# ARE_adaptadores_v101.net
KiCad netlist of a schematic drawn in EAGLE
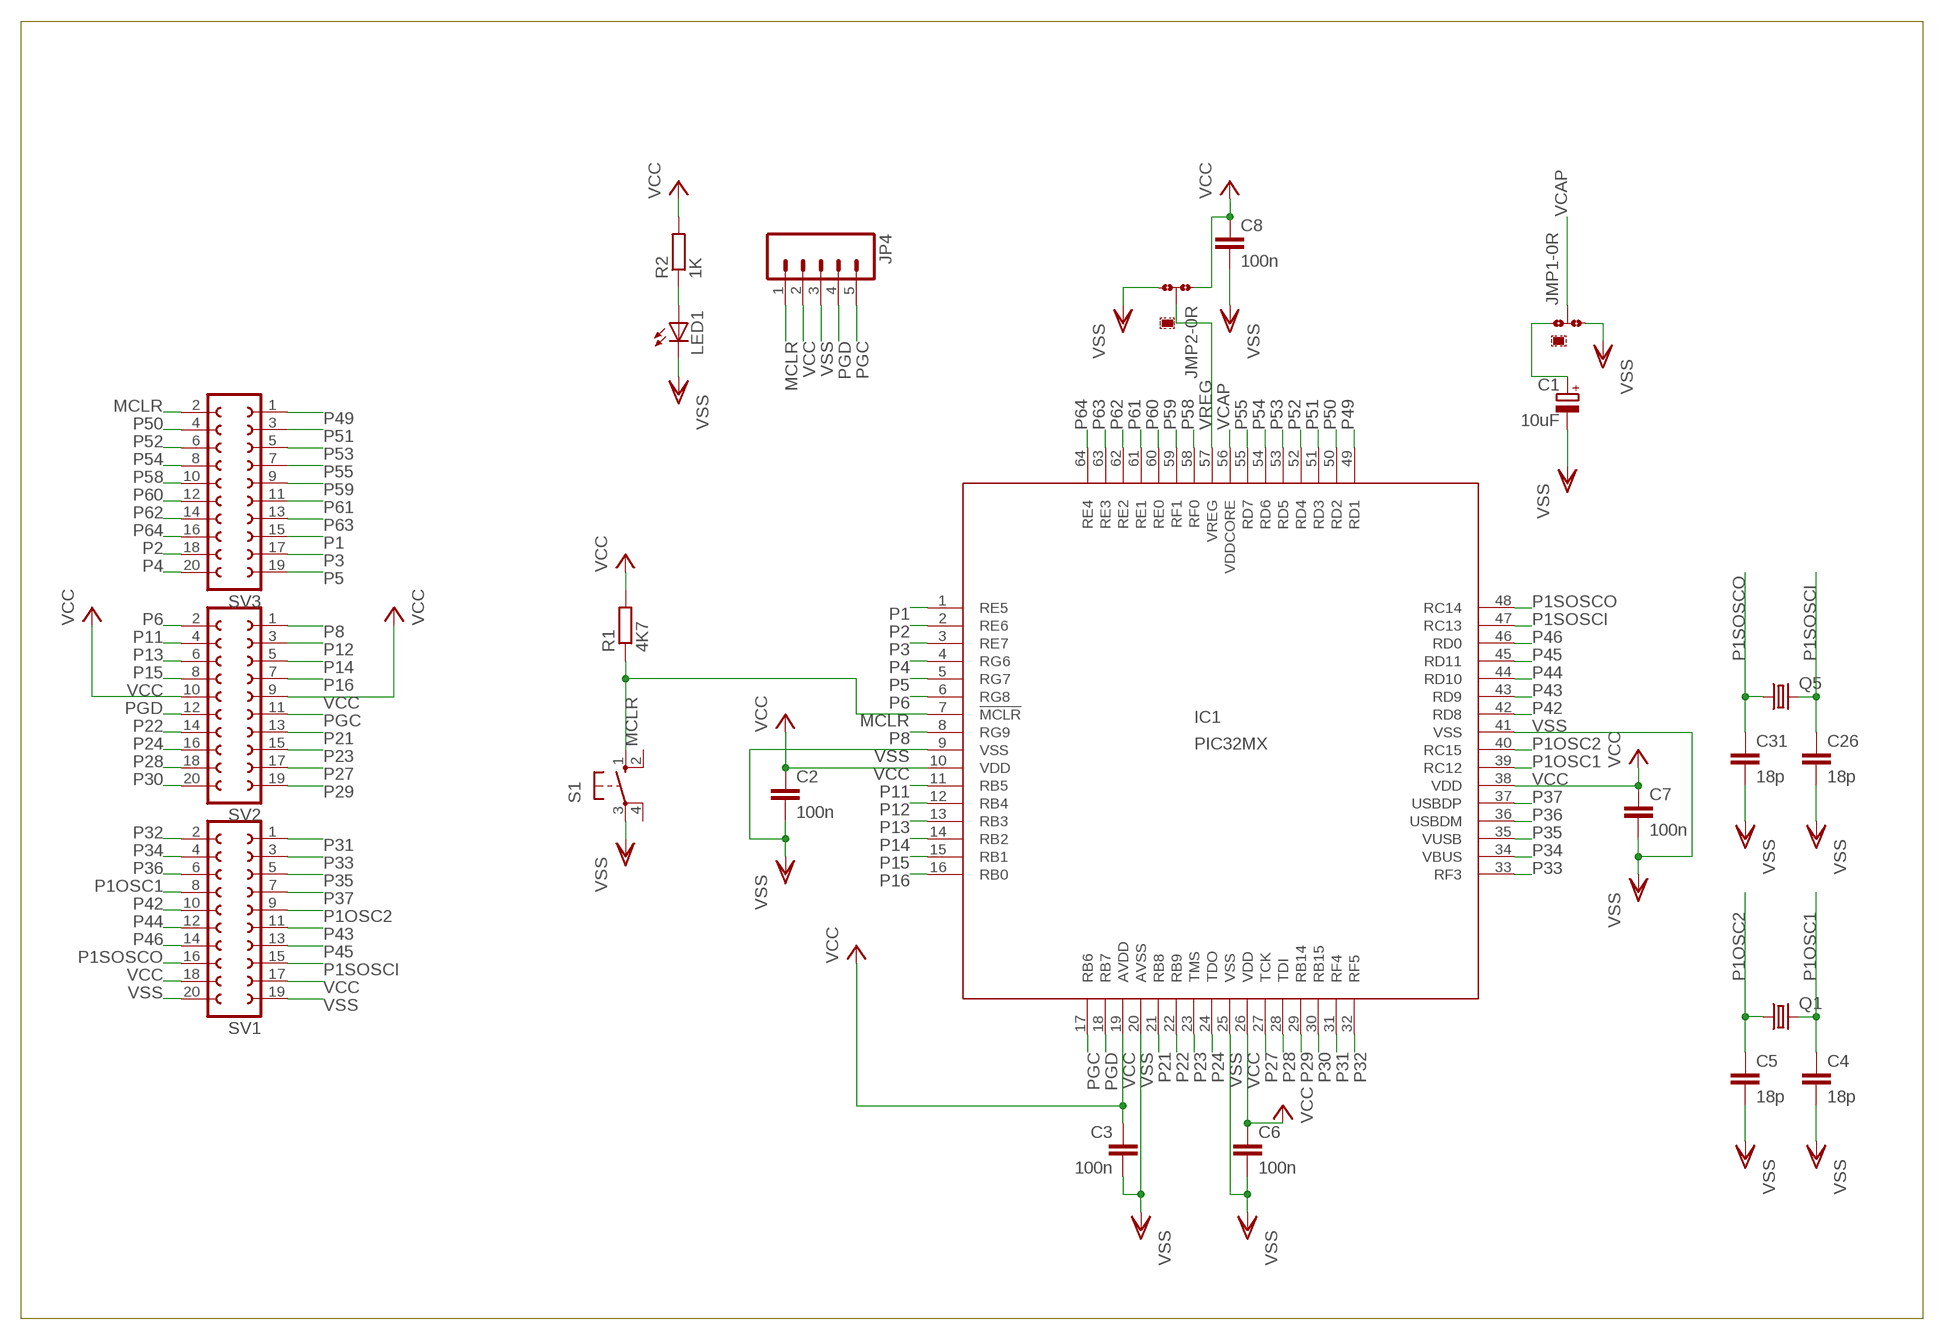
[diagram p0: schematic, sheet 1]
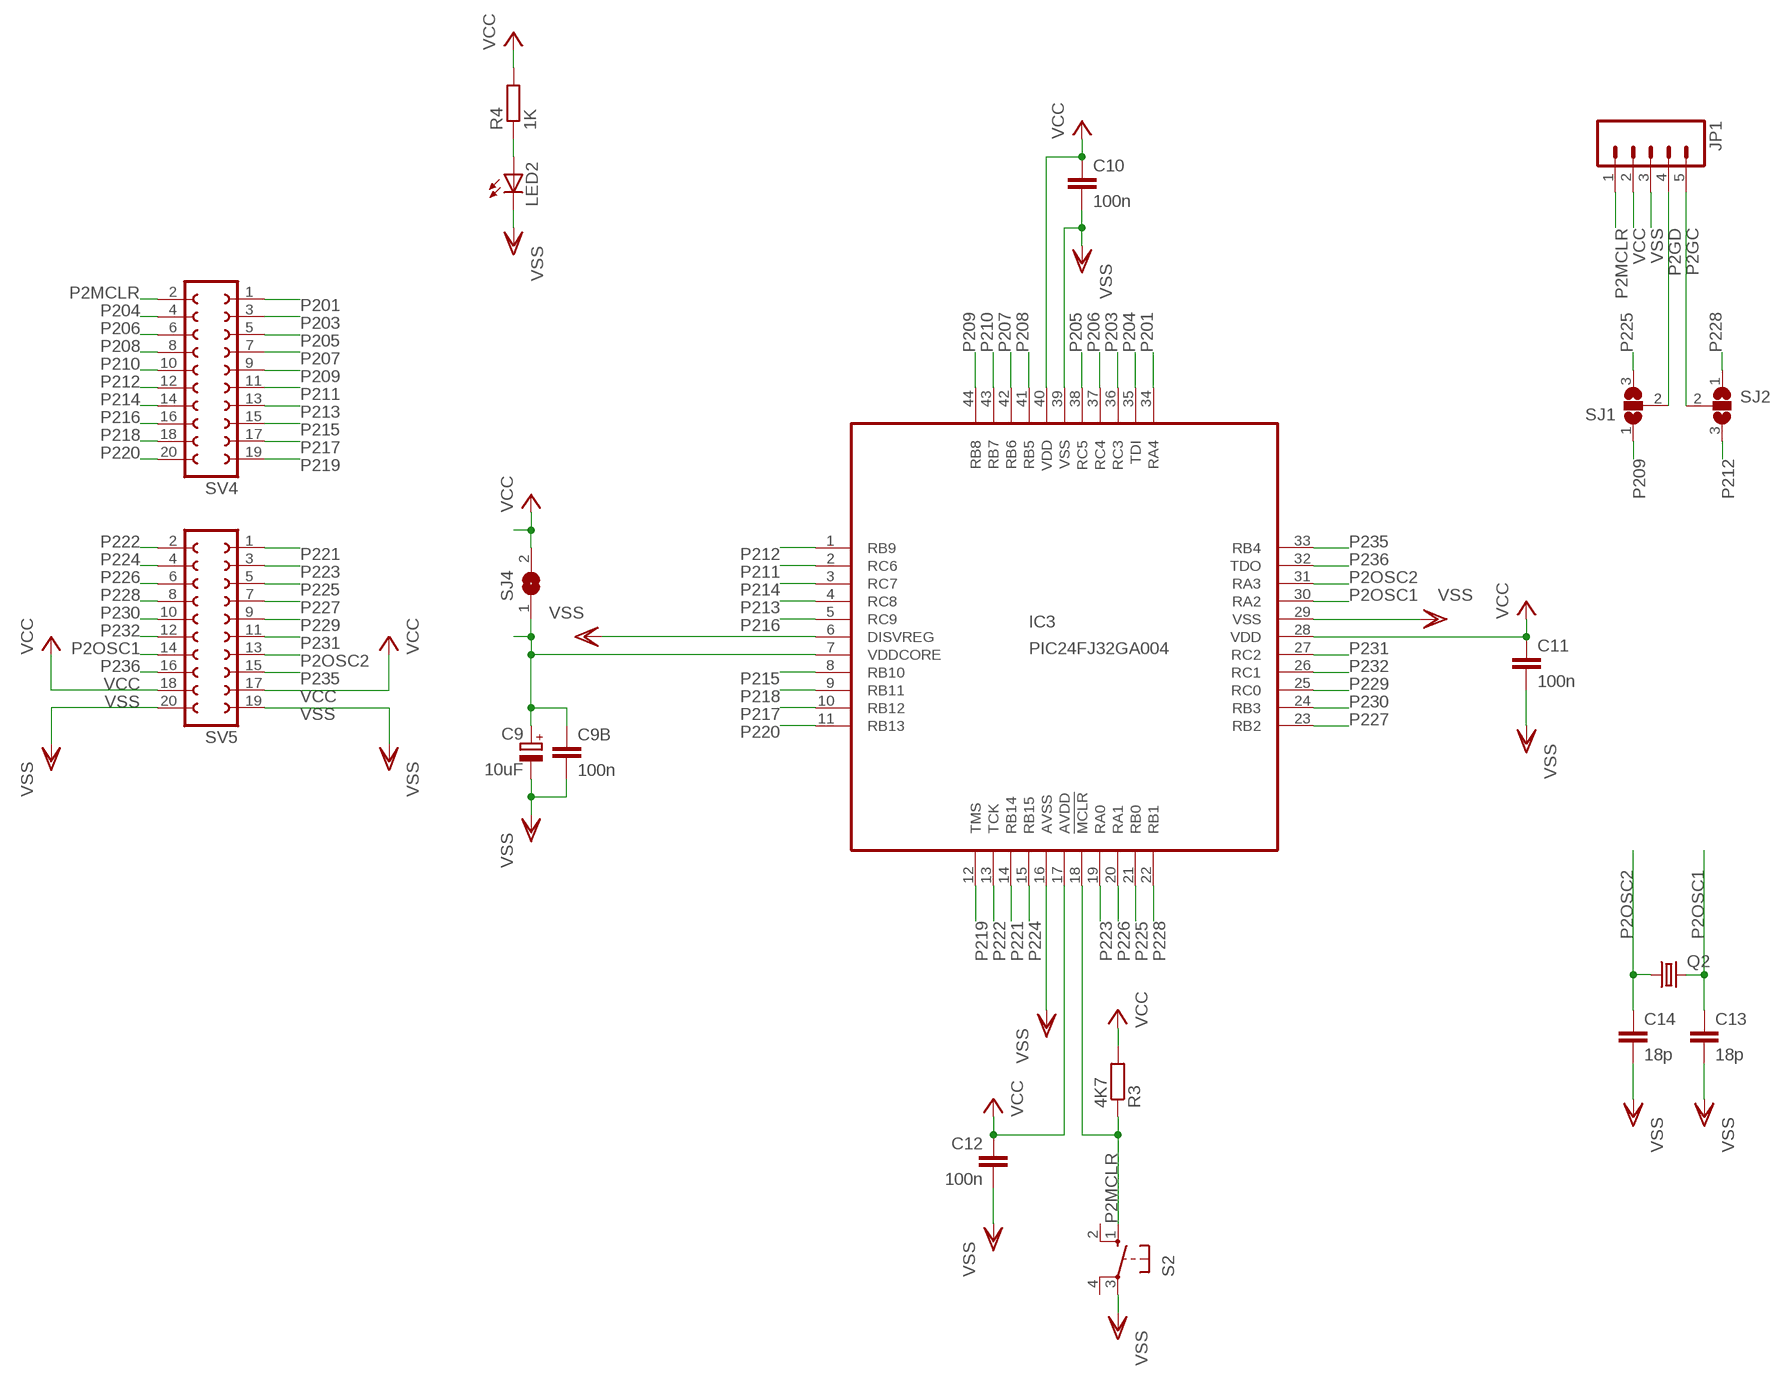
[diagram p1: schematic, sheet 2]
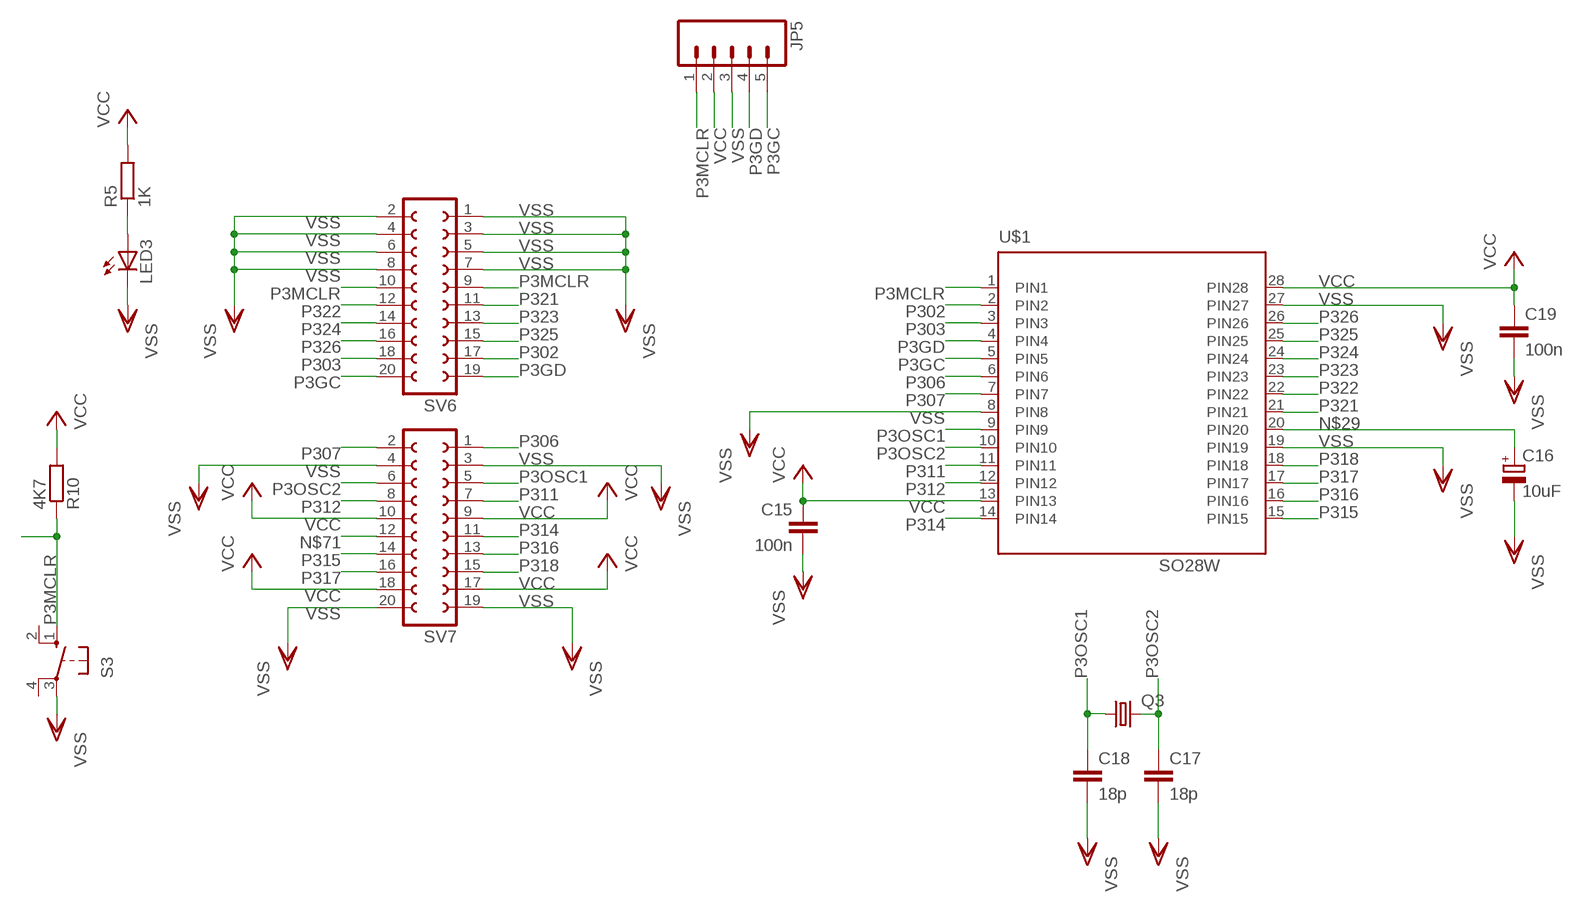
[diagram p2: schematic, sheet 3]
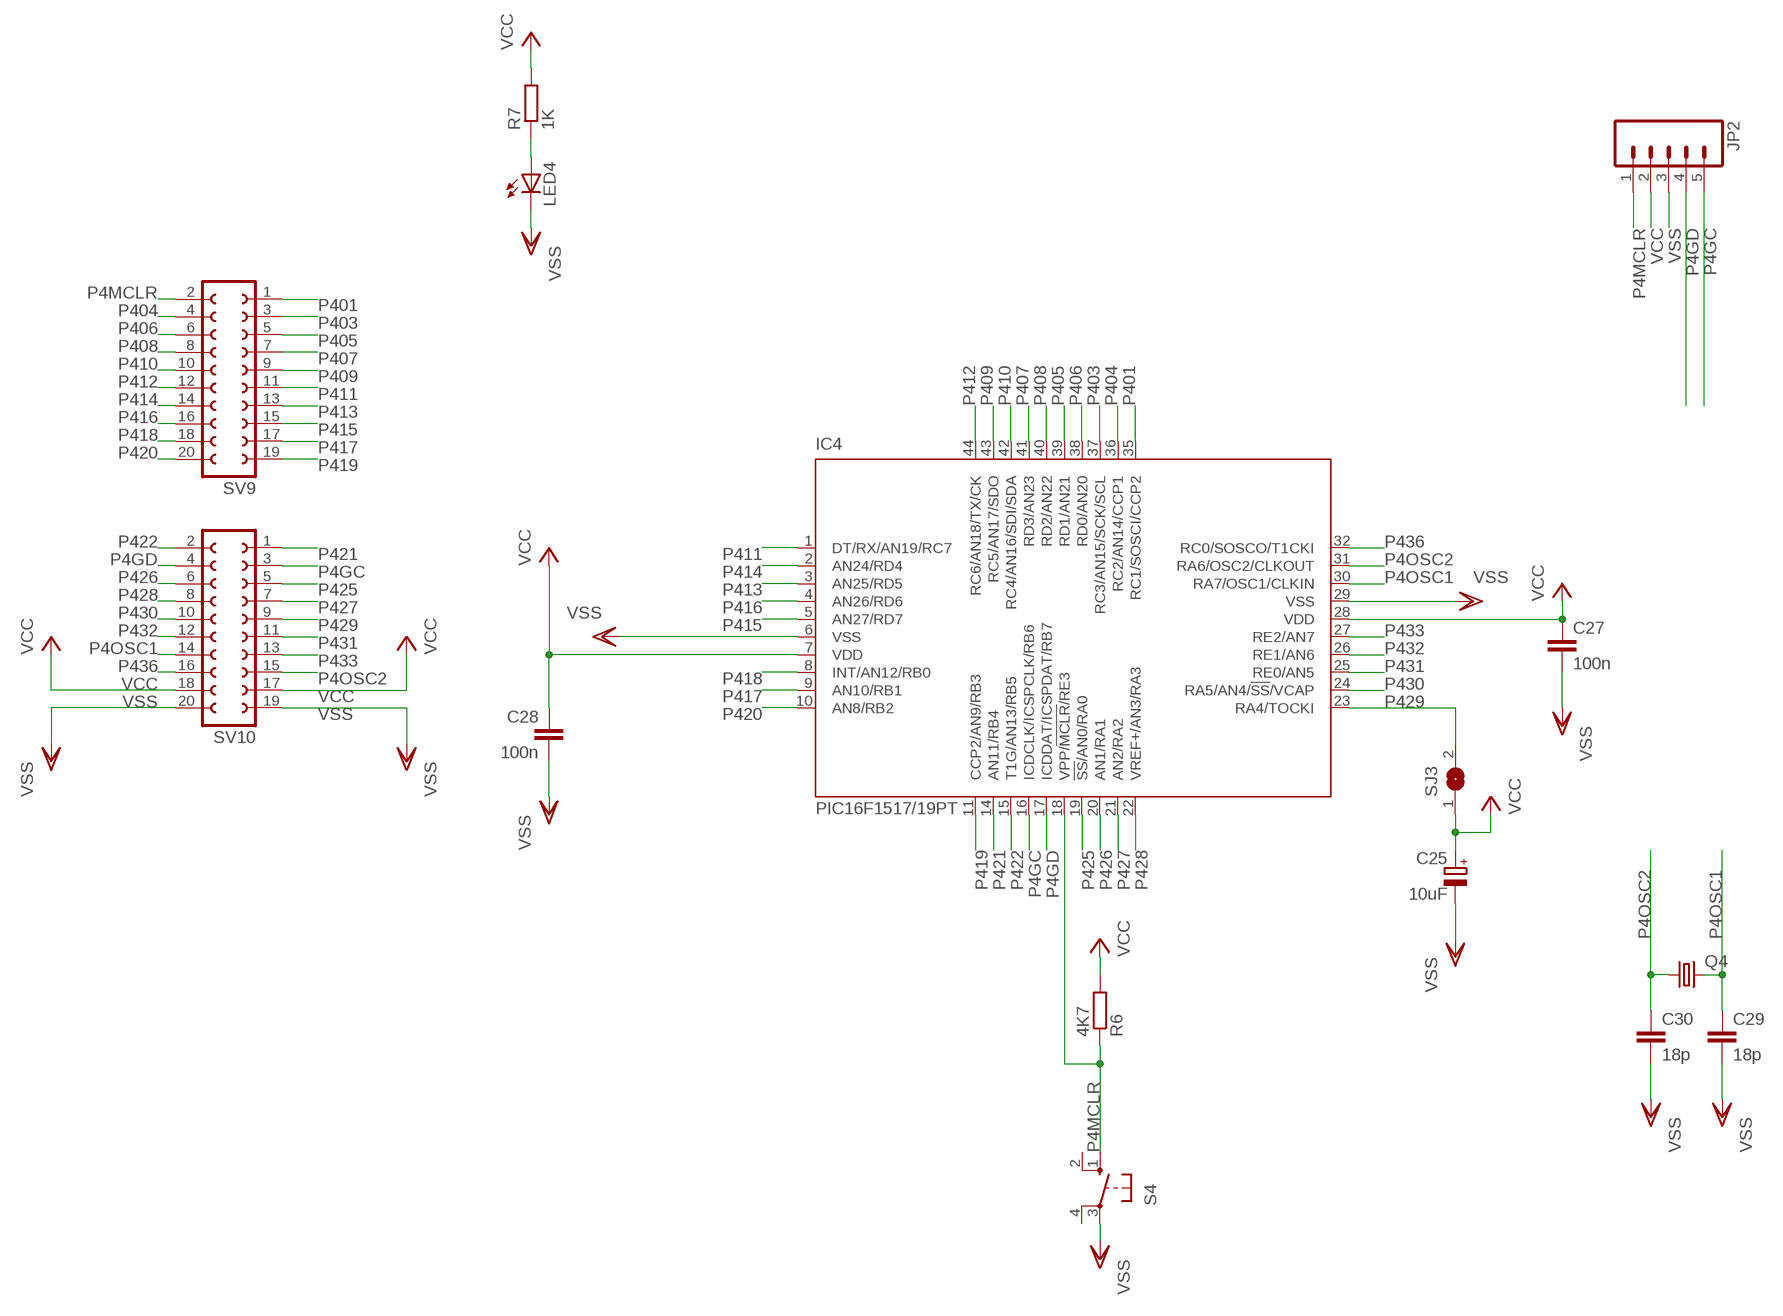
[diagram p3: schematic, sheet 4]
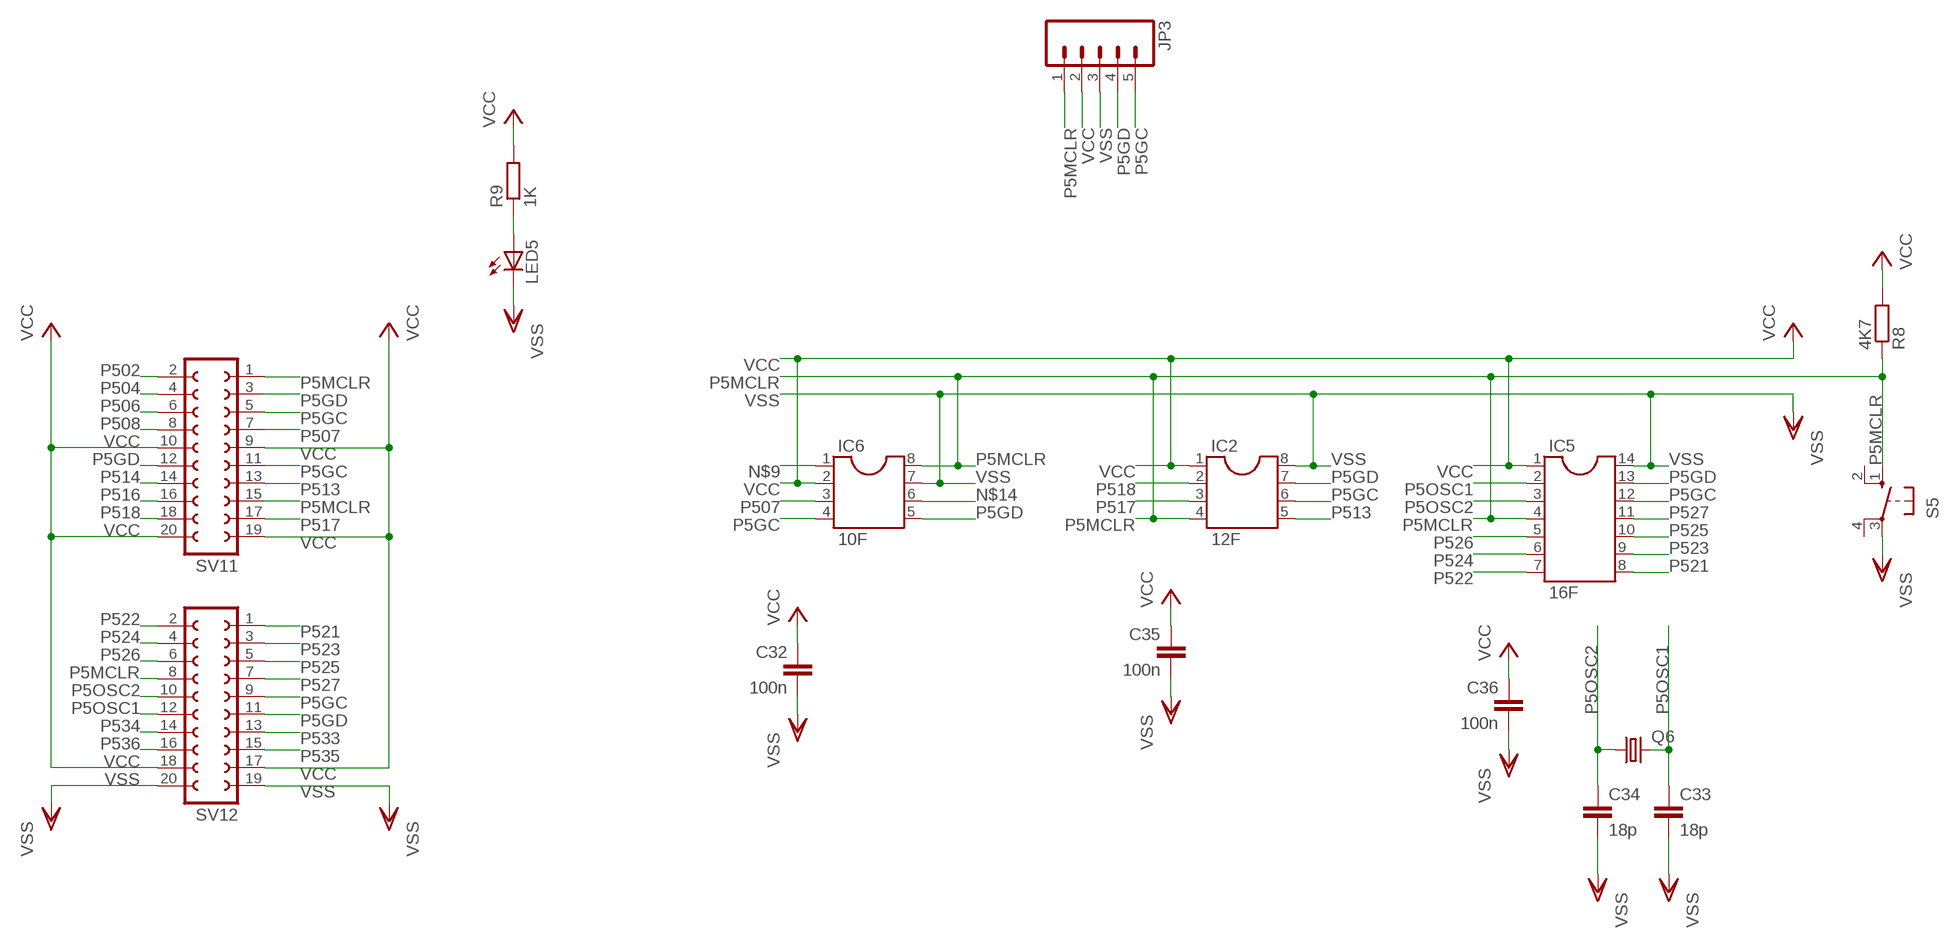
[diagram p4: schematic, sheet 5]
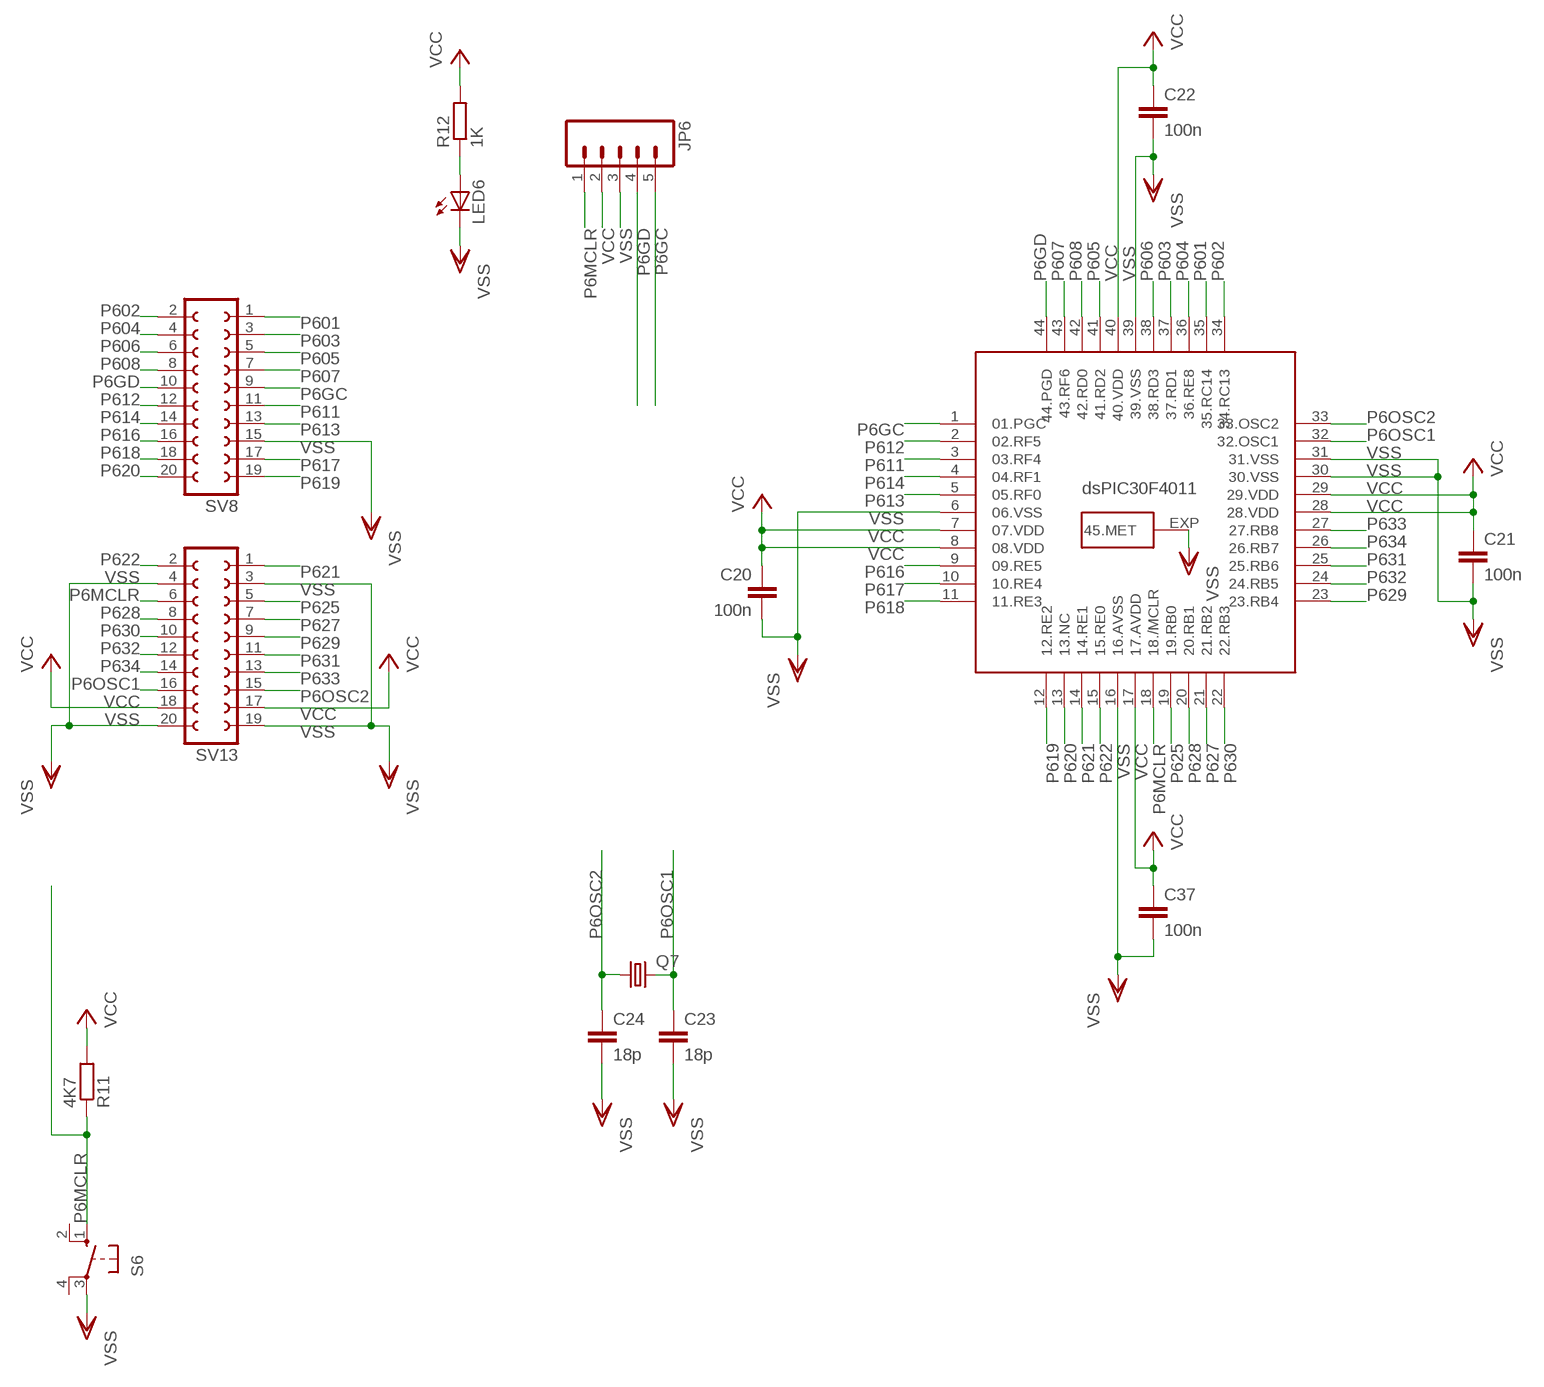
[diagram p5: schematic, sheet 6]
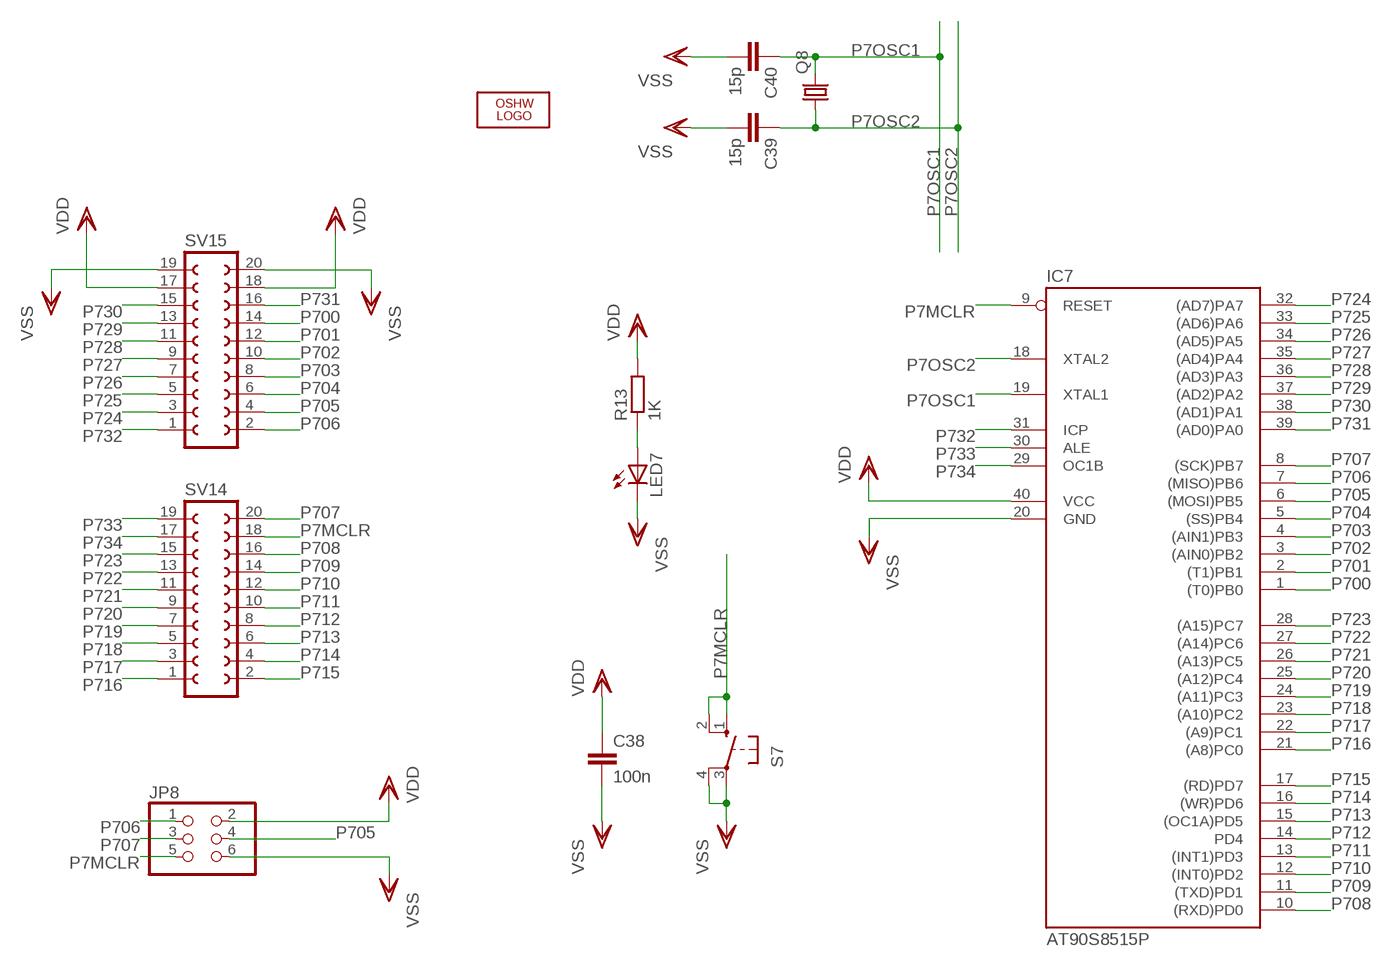
[diagram p6: schematic, sheet 7]
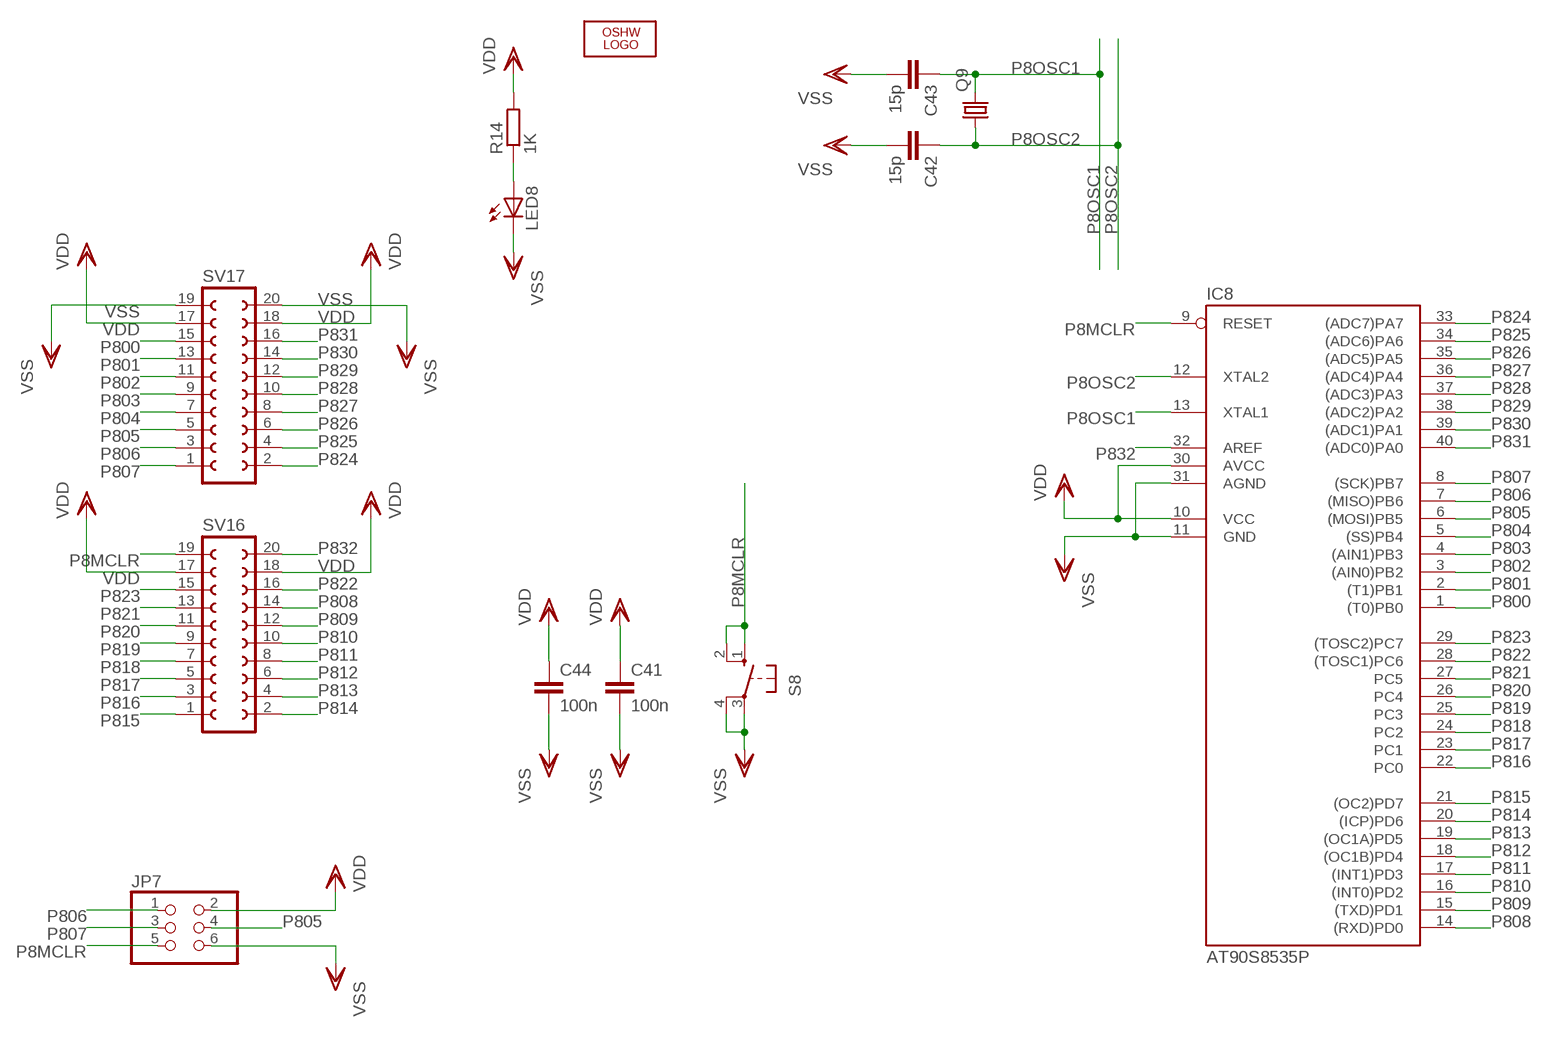
[diagram p7: schematic, sheet 8]
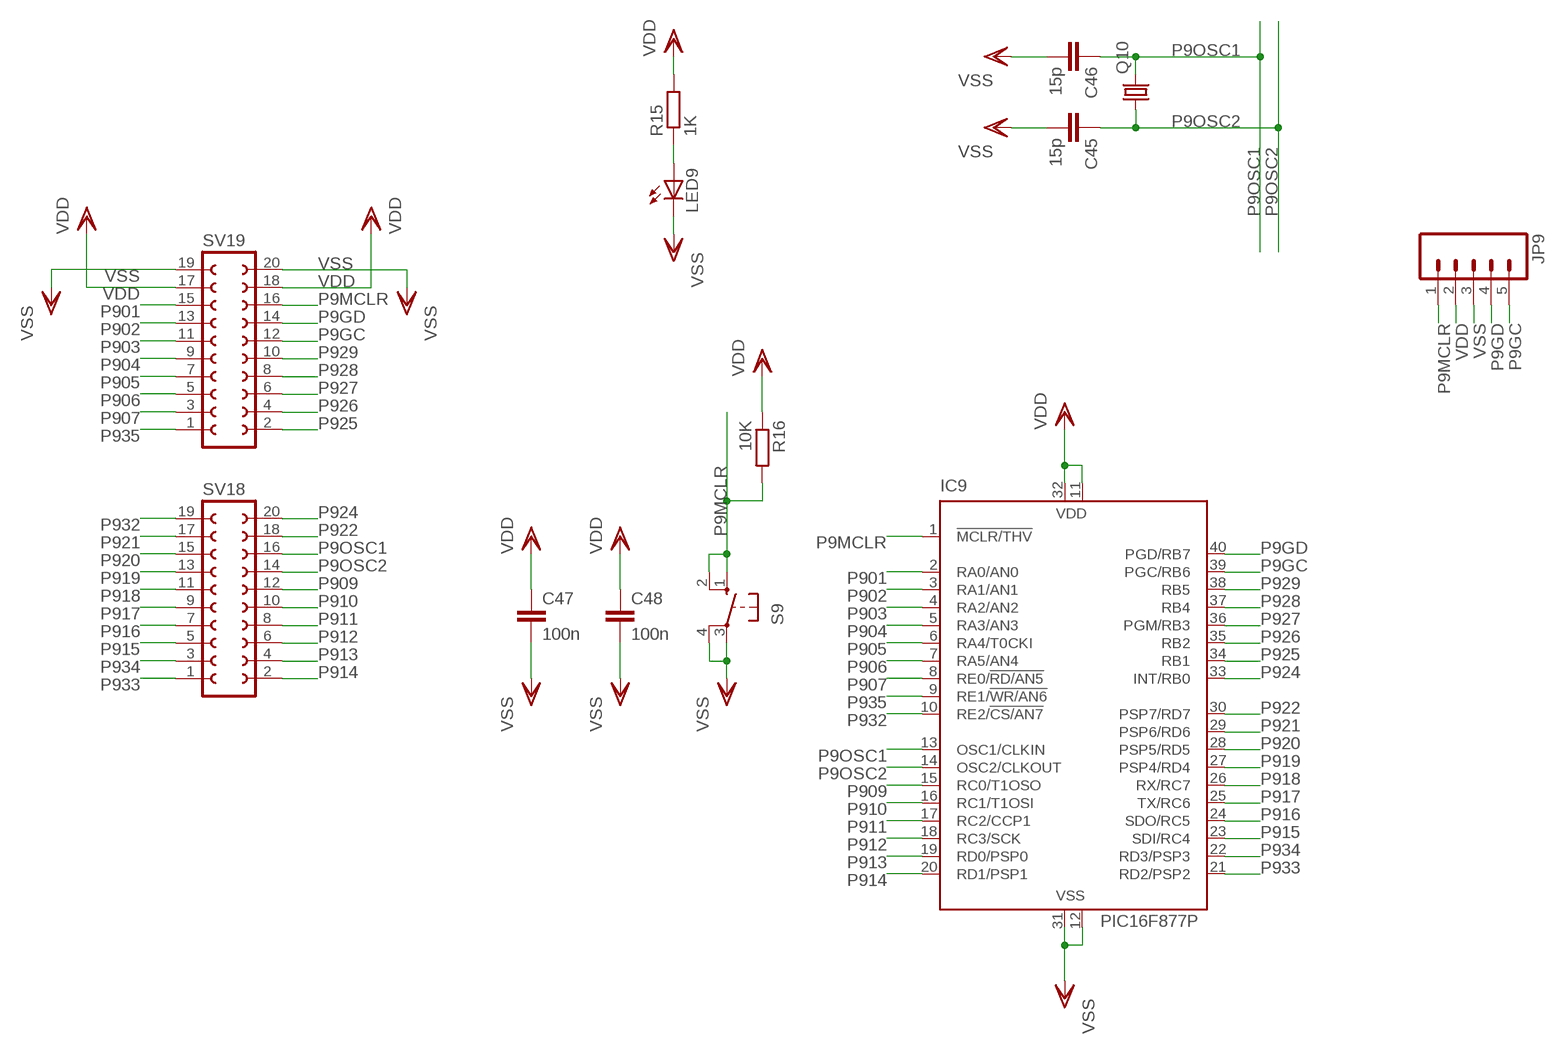
[diagram p8: schematic, sheet 9]
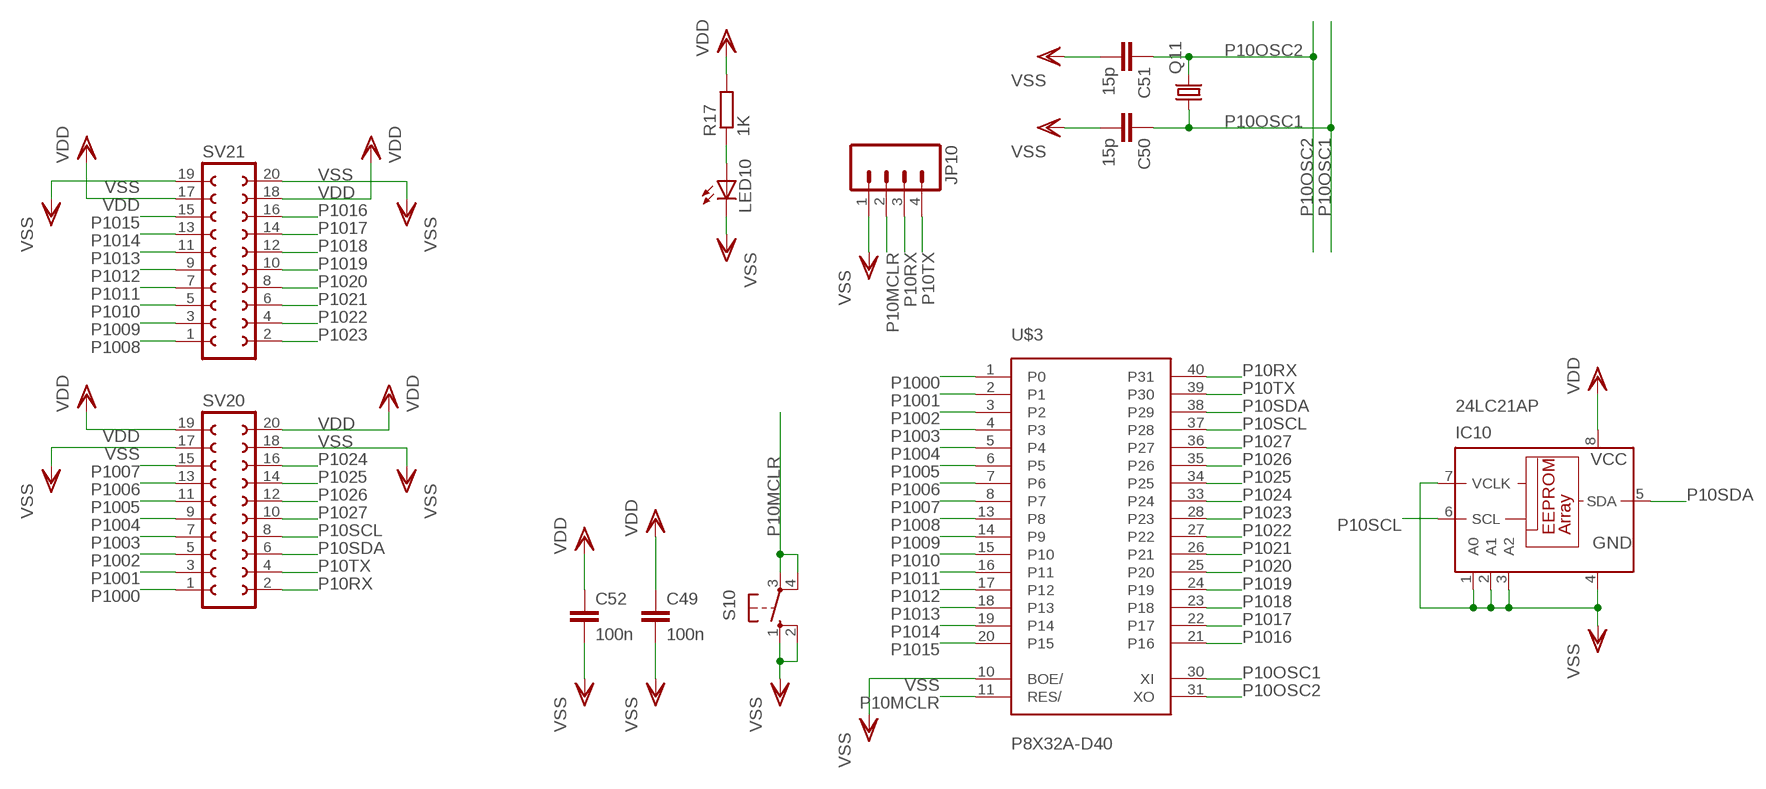
[diagram p9: schematic, sheet 10]
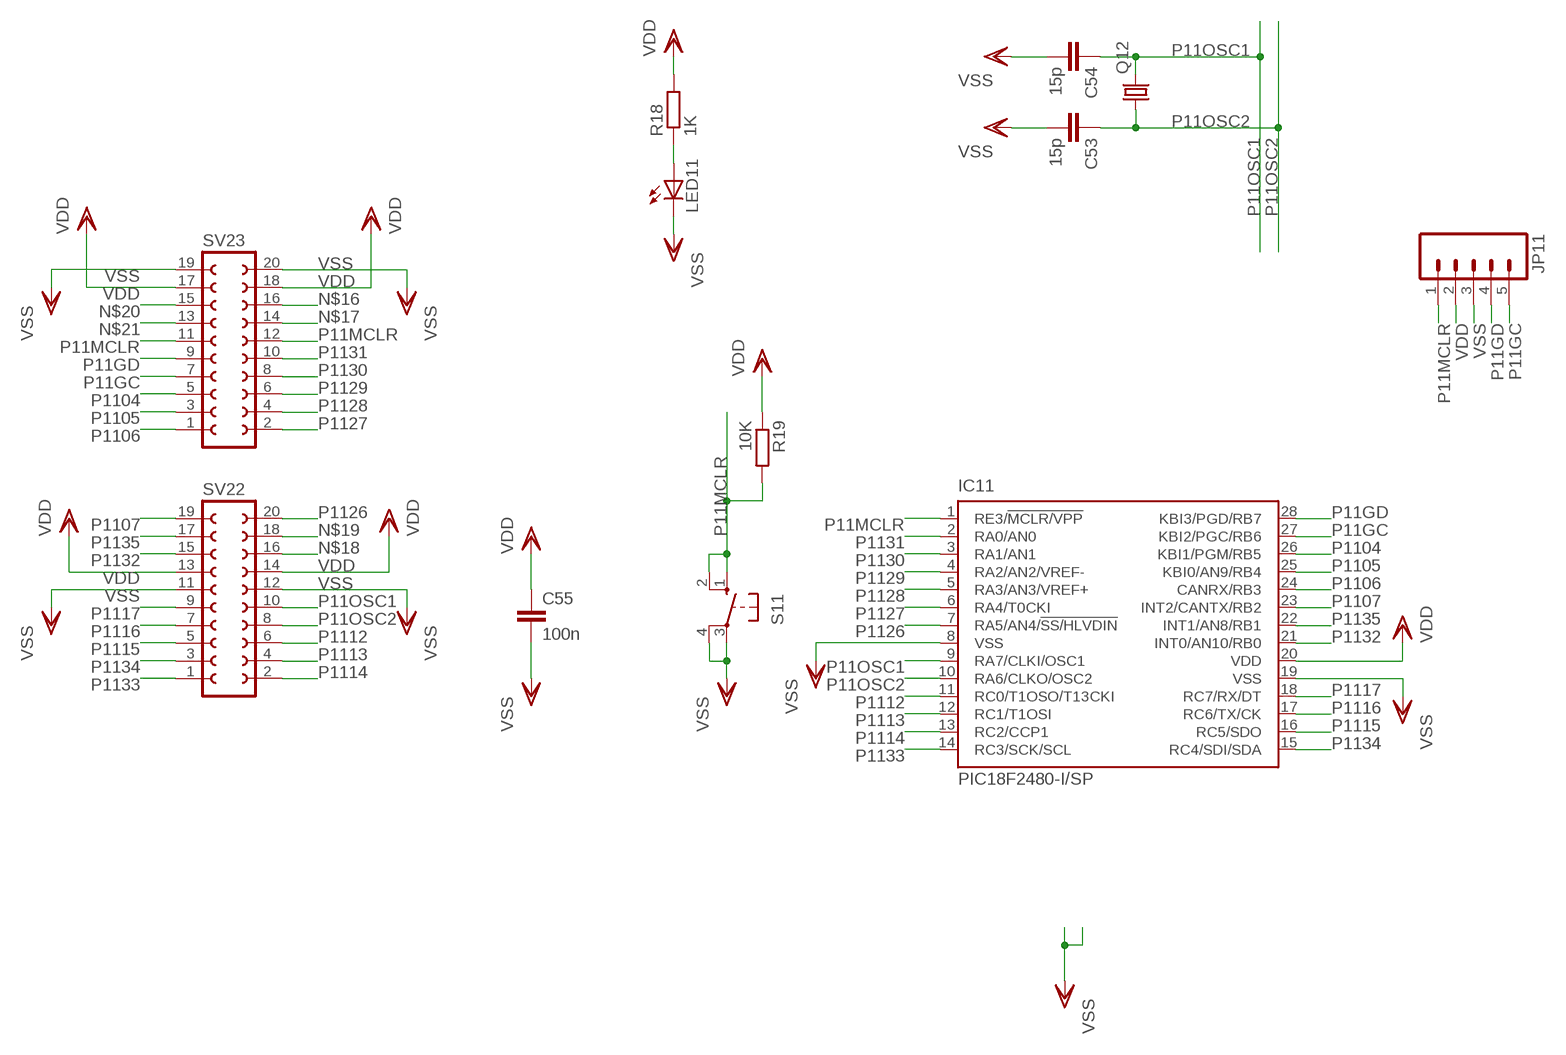
[diagram p10: schematic, sheet 11]

(export (version "E")
  (design (tool "Eeschema 10.0.6"))
  (components
    (comp (ref "C25")
      (value "10uF")
      (footprint "eagle-import:SMC_C")
      (libsource (lib "eagle-import") (part "CPOL-EUSMCC"))
    )
    (comp (ref "C27")
      (value "100n")
      (footprint "eagle-import:C0805")
      (libsource (lib "eagle-import") (part "C-EUC0805"))
    )
    (comp (ref "C28")
      (value "100n")
      (footprint "eagle-import:C0805")
      (libsource (lib "eagle-import") (part "C-EUC0805"))
    )
    (comp (ref "C29")
      (value "18p")
      (footprint "eagle-import:C0805")
      (libsource (lib "eagle-import") (part "C-EUC0805"))
    )
    (comp (ref "C30")
      (value "18p")
      (footprint "eagle-import:C0805")
      (libsource (lib "eagle-import") (part "C-EUC0805"))
    )
    (comp (ref "IC4")
      (value "PIC16F1517/19PT")
      (footprint "eagle-import:TQFP44")
      (libsource (lib "eagle-import") (part "PIC16F1517/19PT"))
    )
    (comp (ref "JP2")
      (value "M05PTH")
      (footprint "eagle-import:1X05")
      (libsource (lib "eagle-import") (part "M05PTH"))
    )
    (comp (ref "LED4")
      (value "LEDCHIPLED_0805")
      (footprint "eagle-import:CHIPLED_0805")
      (libsource (lib "eagle-import") (part "LEDCHIPLED_0805"))
    )
    (comp (ref "Q4")
      (value "CRYSTALHC18U-V")
      (footprint "eagle-import:HC18U-V")
      (libsource (lib "eagle-import") (part "CRYSTALHC18U-V"))
    )
    (comp (ref "R6")
      (value "4K7")
      (footprint "eagle-import:R0805")
      (libsource (lib "eagle-import") (part "R-EU_R0805"))
    )
    (comp (ref "R7")
      (value "1K")
      (footprint "eagle-import:R0805")
      (libsource (lib "eagle-import") (part "R-EU_R0805"))
    )
    (comp (ref "S4")
      (value "10-XX")
      (footprint "eagle-import:B3F-10XX")
      (fields
        (field (name "MPN") "B3F-1000")
        (field (name "MPN_1") "B3F-1000")
        (field (name "OC_FARNELL") "176432")
        (field (name "OC_NEWARK") "36M3542")
      )
      (libsource (lib "eagle-import") (part "10-XX"))
    )
    (comp (ref "SJ3") (value "SJ") (footprint "eagle-import:SJ") (libsource (lib "eagle-import") (part "SJ")))
    (comp (ref "SV9")
      (value "FE10-2W")
      (footprint "eagle-import:FE10-2W")
      (libsource (lib "eagle-import") (part "FE10-2W"))
    )
    (comp (ref "SV10")
      (value "FE10-2W")
      (footprint "eagle-import:FE10-2W")
      (libsource (lib "eagle-import") (part "FE10-2W"))
    )
    (comp (ref "C38")
      (value "100n")
      (footprint "eagle-import:C0805")
      (libsource (lib "eagle-import") (part "C-EUC0805"))
    )
    (comp (ref "C39")
      (value "15p")
      (footprint "eagle-import:C0805")
      (libsource (lib "eagle-import") (part "C-EUC0805"))
    )
    (comp (ref "C40")
      (value "15p")
      (footprint "eagle-import:C0805")
      (libsource (lib "eagle-import") (part "C-EUC0805"))
    )
    (comp (ref "IC7")
      (value "AT90S8515P")
      (footprint "eagle-import:DIL40")
      (libsource (lib "eagle-import") (part "AT90S8515P"))
    )
    (comp (ref "JP8")
      (value "PINHD-2X3")
      (footprint "eagle-import:2X03")
      (libsource (lib "eagle-import") (part "PINHD-2X3"))
    )
    (comp (ref "LED7")
      (value "LED3MM")
      (footprint "eagle-import:LED3MM")
      (libsource (lib "eagle-import") (part "LED3MM"))
    )
    (comp (ref "LOGO2")
      (value "OSHW_LOGO_8MILX0150-NT")
      (footprint "eagle-import:OSHW_8X150_NOTEXT")
      (libsource (lib "eagle-import") (part "OSHW_LOGO_8MILX0150-NT"))
    )
    (comp (ref "Q8")
      (value "CRYSTALHC18U-V")
      (footprint "eagle-import:HC18U-V")
      (libsource (lib "eagle-import") (part "CRYSTALHC18U-V"))
    )
    (comp (ref "R13")
      (value "1K")
      (footprint "eagle-import:R0805")
      (libsource (lib "eagle-import") (part "R-EU_R0805"))
    )
    (comp (ref "S7")
      (value "10-XX")
      (footprint "eagle-import:B3F-10XX")
      (fields
        (field (name "MPN") "B3F-1000")
        (field (name "MPN_1") "B3F-1000")
        (field (name "OC_FARNELL") "176432")
        (field (name "OC_NEWARK") "36M3542")
      )
      (libsource (lib "eagle-import") (part "10-XX"))
    )
    (comp (ref "SV14")
      (value "FE10-2W")
      (footprint "eagle-import:FE10-2W")
      (libsource (lib "eagle-import") (part "FE10-2W"))
    )
    (comp (ref "SV15")
      (value "FE10-2W")
      (footprint "eagle-import:FE10-2W")
      (libsource (lib "eagle-import") (part "FE10-2W"))
    )
    (comp (ref "C15")
      (value "100n")
      (footprint "eagle-import:C0805")
      (libsource (lib "eagle-import") (part "C-EUC0805"))
    )
    (comp (ref "C16")
      (value "10uF")
      (footprint "eagle-import:SMC_C")
      (libsource (lib "eagle-import") (part "CPOL-EUSMCC"))
    )
    (comp (ref "C17")
      (value "18p")
      (footprint "eagle-import:C0805")
      (libsource (lib "eagle-import") (part "C-EUC0805"))
    )
    (comp (ref "C18")
      (value "18p")
      (footprint "eagle-import:C0805")
      (libsource (lib "eagle-import") (part "C-EUC0805"))
    )
    (comp (ref "C19")
      (value "100n")
      (footprint "eagle-import:C0805")
      (libsource (lib "eagle-import") (part "C-EUC0805"))
    )
    (comp (ref "JP5")
      (value "M05PTH")
      (footprint "eagle-import:1X05")
      (libsource (lib "eagle-import") (part "M05PTH"))
    )
    (comp (ref "LED3")
      (value "LEDCHIPLED_0805")
      (footprint "eagle-import:CHIPLED_0805")
      (libsource (lib "eagle-import") (part "LEDCHIPLED_0805"))
    )
    (comp (ref "Q3")
      (value "CRYSTALHC18U-V")
      (footprint "eagle-import:HC18U-V")
      (libsource (lib "eagle-import") (part "CRYSTALHC18U-V"))
    )
    (comp (ref "R5")
      (value "1K")
      (footprint "eagle-import:R0805")
      (libsource (lib "eagle-import") (part "R-EU_R0805"))
    )
    (comp (ref "R10")
      (value "4K7")
      (footprint "eagle-import:R0805")
      (libsource (lib "eagle-import") (part "R-EU_R0805"))
    )
    (comp (ref "S3")
      (value "10-XX")
      (footprint "eagle-import:B3F-10XX")
      (fields
        (field (name "MPN") "B3F-1000")
        (field (name "MPN_1") "B3F-1000")
        (field (name "OC_FARNELL") "176432")
        (field (name "OC_NEWARK") "36M3542")
      )
      (libsource (lib "eagle-import") (part "10-XX"))
    )
    (comp (ref "SV6")
      (value "FE10-2W")
      (footprint "eagle-import:FE10-2W")
      (libsource (lib "eagle-import") (part "FE10-2W"))
    )
    (comp (ref "SV7")
      (value "FE10-2W")
      (footprint "eagle-import:FE10-2W")
      (libsource (lib "eagle-import") (part "FE10-2W"))
    )
    (comp (ref "U$1")
      (value "SO28W")
      (footprint "eagle-import:SO28W")
      (libsource (lib "eagle-import") (part "SO28W"))
    )
    (comp (ref "C32")
      (value "100n")
      (footprint "eagle-import:C0805")
      (libsource (lib "eagle-import") (part "C-EUC0805"))
    )
    (comp (ref "C33")
      (value "18p")
      (footprint "eagle-import:C0805")
      (libsource (lib "eagle-import") (part "C-EUC0805"))
    )
    (comp (ref "C34")
      (value "18p")
      (footprint "eagle-import:C0805")
      (libsource (lib "eagle-import") (part "C-EUC0805"))
    )
    (comp (ref "C35")
      (value "100n")
      (footprint "eagle-import:C0805")
      (libsource (lib "eagle-import") (part "C-EUC0805"))
    )
    (comp (ref "C36")
      (value "100n")
      (footprint "eagle-import:C0805")
      (libsource (lib "eagle-import") (part "C-EUC0805"))
    )
    (comp (ref "IC2")
      (value "12F")
      (footprint "eagle-import:SOCKET-08")
      (libsource (lib "eagle-import") (part "DIL8S"))
    )
    (comp (ref "IC5")
      (value "16F")
      (footprint "eagle-import:SOCKET-14")
      (libsource (lib "eagle-import") (part "DIL14S"))
    )
    (comp (ref "IC6")
      (value "10F")
      (footprint "eagle-import:SOCKET-08")
      (libsource (lib "eagle-import") (part "DIL8S"))
    )
    (comp (ref "JP3")
      (value "M05PTH")
      (footprint "eagle-import:1X05")
      (libsource (lib "eagle-import") (part "M05PTH"))
    )
    (comp (ref "LED5")
      (value "LEDCHIPLED_0805")
      (footprint "eagle-import:CHIPLED_0805")
      (libsource (lib "eagle-import") (part "LEDCHIPLED_0805"))
    )
    (comp (ref "Q6")
      (value "CRYSTALHC18U-V")
      (footprint "eagle-import:HC18U-V")
      (libsource (lib "eagle-import") (part "CRYSTALHC18U-V"))
    )
    (comp (ref "R8")
      (value "4K7")
      (footprint "eagle-import:R0805")
      (libsource (lib "eagle-import") (part "R-EU_R0805"))
    )
    (comp (ref "R9")
      (value "1K")
      (footprint "eagle-import:R0805")
      (libsource (lib "eagle-import") (part "R-EU_R0805"))
    )
    (comp (ref "S5")
      (value "10-XX")
      (footprint "eagle-import:B3F-10XX")
      (fields
        (field (name "MPN") "B3F-1000")
        (field (name "MPN_1") "B3F-1000")
        (field (name "OC_FARNELL") "176432")
        (field (name "OC_NEWARK") "36M3542")
      )
      (libsource (lib "eagle-import") (part "10-XX"))
    )
    (comp (ref "SV11")
      (value "FE10-2W")
      (footprint "eagle-import:FE10-2W")
      (libsource (lib "eagle-import") (part "FE10-2W"))
    )
    (comp (ref "SV12")
      (value "FE10-2W")
      (footprint "eagle-import:FE10-2W")
      (libsource (lib "eagle-import") (part "FE10-2W"))
    )
    (comp (ref "C41")
      (value "100n")
      (footprint "eagle-import:C0805")
      (libsource (lib "eagle-import") (part "C-EUC0805"))
    )
    (comp (ref "C42")
      (value "15p")
      (footprint "eagle-import:C0805")
      (libsource (lib "eagle-import") (part "C-EUC0805"))
    )
    (comp (ref "C43")
      (value "15p")
      (footprint "eagle-import:C0805")
      (libsource (lib "eagle-import") (part "C-EUC0805"))
    )
    (comp (ref "C44")
      (value "100n")
      (footprint "eagle-import:C0805")
      (libsource (lib "eagle-import") (part "C-EUC0805"))
    )
    (comp (ref "IC8")
      (value "AT90S8535P")
      (footprint "eagle-import:DIL40")
      (libsource (lib "eagle-import") (part "AT908535PS"))
    )
    (comp (ref "JP7")
      (value "PINHD-2X3")
      (footprint "eagle-import:2X03")
      (libsource (lib "eagle-import") (part "PINHD-2X3"))
    )
    (comp (ref "LED8")
      (value "LED3MM")
      (footprint "eagle-import:LED3MM")
      (libsource (lib "eagle-import") (part "LED3MM"))
    )
    (comp (ref "LOGO4")
      (value "OSHW_LOGO_8MILX0150-NT")
      (footprint "eagle-import:OSHW_8X150_NOTEXT")
      (libsource (lib "eagle-import") (part "OSHW_LOGO_8MILX0150-NT"))
    )
    (comp (ref "Q9")
      (value "CRYSTALHC18U-V")
      (footprint "eagle-import:HC18U-V")
      (libsource (lib "eagle-import") (part "CRYSTALHC18U-V"))
    )
    (comp (ref "R14")
      (value "1K")
      (footprint "eagle-import:R0805")
      (libsource (lib "eagle-import") (part "R-EU_R0805"))
    )
    (comp (ref "S8")
      (value "10-XX")
      (footprint "eagle-import:B3F-10XX")
      (fields
        (field (name "MPN") "B3F-1000")
        (field (name "MPN_1") "B3F-1000")
        (field (name "OC_FARNELL") "176432")
        (field (name "OC_NEWARK") "36M3542")
      )
      (libsource (lib "eagle-import") (part "10-XX"))
    )
    (comp (ref "SV16")
      (value "FE10-2W")
      (footprint "eagle-import:FE10-2W")
      (libsource (lib "eagle-import") (part "FE10-2W"))
    )
    (comp (ref "SV17")
      (value "FE10-2W")
      (footprint "eagle-import:FE10-2W")
      (libsource (lib "eagle-import") (part "FE10-2W"))
    )
    (comp (ref "C49")
      (value "100n")
      (footprint "eagle-import:C0805")
      (libsource (lib "eagle-import") (part "C-EUC0805"))
    )
    (comp (ref "C50")
      (value "15p")
      (footprint "eagle-import:C0805")
      (libsource (lib "eagle-import") (part "C-EUC0805"))
    )
    (comp (ref "C51")
      (value "15p")
      (footprint "eagle-import:C0805")
      (libsource (lib "eagle-import") (part "C-EUC0805"))
    )
    (comp (ref "C52")
      (value "100n")
      (footprint "eagle-import:C0805")
      (libsource (lib "eagle-import") (part "C-EUC0805"))
    )
    (comp (ref "IC10")
      (value "24LC21AP")
      (footprint "eagle-import:DIL8")
      (libsource (lib "eagle-import") (part "24LPC21A"))
    )
    (comp (ref "JP10")
      (value "M04PTH")
      (footprint "eagle-import:1X04")
      (libsource (lib "eagle-import") (part "M04PTH"))
    )
    (comp (ref "LED10")
      (value "LED3MM")
      (footprint "eagle-import:LED3MM")
      (libsource (lib "eagle-import") (part "LED3MM"))
    )
    (comp (ref "Q11")
      (value "CRYSTALHC18U-V")
      (footprint "eagle-import:HC18U-V")
      (libsource (lib "eagle-import") (part "CRYSTALHC18U-V"))
    )
    (comp (ref "R17")
      (value "1K")
      (footprint "eagle-import:R0805")
      (libsource (lib "eagle-import") (part "R-EU_R0805"))
    )
    (comp (ref "S10")
      (value "10-XX")
      (footprint "eagle-import:B3F-10XX")
      (fields
        (field (name "MPN") "B3F-1000")
        (field (name "MPN_1") "B3F-1000")
        (field (name "OC_FARNELL") "176432")
        (field (name "OC_NEWARK") "36M3542")
      )
      (libsource (lib "eagle-import") (part "10-XX"))
    )
    (comp (ref "SV20")
      (value "FE10-2W")
      (footprint "eagle-import:FE10-2W")
      (libsource (lib "eagle-import") (part "FE10-2W"))
    )
    (comp (ref "SV21")
      (value "FE10-2W")
      (footprint "eagle-import:FE10-2W")
      (fields (field (name "OC_FARNELL") "unknown") (field (name "OC_NEWARK") "unknown"))
      (libsource (lib "eagle-import") (part "FE10-2W"))
    )
    (comp (ref "U$3")
      (value "P8X32A-D40")
      (footprint "eagle-import:P8X32A-D40")
      (libsource (lib "eagle-import") (part "P8X32A-D40"))
    )
    (comp (ref "C9")
      (value "10uF")
      (footprint "eagle-import:SMC_C")
      (libsource (lib "eagle-import") (part "CPOL-EUSMCC"))
    )
    (comp (ref "C9B")
      (value "100n")
      (footprint "eagle-import:C0805")
      (libsource (lib "eagle-import") (part "C-EUC0805"))
    )
    (comp (ref "C10")
      (value "100n")
      (footprint "eagle-import:C0805")
      (libsource (lib "eagle-import") (part "C-EUC0805"))
    )
    (comp (ref "C11")
      (value "100n")
      (footprint "eagle-import:C0805")
      (libsource (lib "eagle-import") (part "C-EUC0805"))
    )
    (comp (ref "C12")
      (value "100n")
      (footprint "eagle-import:C0805")
      (libsource (lib "eagle-import") (part "C-EUC0805"))
    )
    (comp (ref "C13")
      (value "18p")
      (footprint "eagle-import:C0805")
      (libsource (lib "eagle-import") (part "C-EUC0805"))
    )
    (comp (ref "C14")
      (value "18p")
      (footprint "eagle-import:C0805")
      (libsource (lib "eagle-import") (part "C-EUC0805"))
    )
    (comp (ref "IC3")
      (value "PIC24FJ32GA004")
      (footprint "eagle-import:TQFP44")
      (fields (field (name "MPN") "PIC24FJ32GA004-E/PT"))
      (libsource (lib "eagle-import") (part "PIC24FJ32GA004"))
    )
    (comp (ref "JP1")
      (value "M05PTH")
      (footprint "eagle-import:1X05")
      (libsource (lib "eagle-import") (part "M05PTH"))
    )
    (comp (ref "LED2")
      (value "LEDCHIPLED_0805")
      (footprint "eagle-import:CHIPLED_0805")
      (libsource (lib "eagle-import") (part "LEDCHIPLED_0805"))
    )
    (comp (ref "Q2")
      (value "CRYSTALHC18U-V")
      (footprint "eagle-import:HC18U-V")
      (libsource (lib "eagle-import") (part "CRYSTALHC18U-V"))
    )
    (comp (ref "R3")
      (value "4K7")
      (footprint "eagle-import:R0805")
      (libsource (lib "eagle-import") (part "R-EU_R0805"))
    )
    (comp (ref "R4")
      (value "1K")
      (footprint "eagle-import:R0805")
      (libsource (lib "eagle-import") (part "R-EU_R0805"))
    )
    (comp (ref "S2")
      (value "10-XX")
      (footprint "eagle-import:B3F-10XX")
      (fields
        (field (name "MPN") "B3F-1000")
        (field (name "MPN_1") "B3F-1000")
        (field (name "OC_FARNELL") "176432")
        (field (name "OC_NEWARK") "36M3542")
      )
      (libsource (lib "eagle-import") (part "10-XX"))
    )
    (comp (ref "SJ1")
      (value "SJ2W")
      (footprint "eagle-import:SJ_2")
      (libsource (lib "eagle-import") (part "SJ2W"))
    )
    (comp (ref "SJ2")
      (value "SJ2W")
      (footprint "eagle-import:SJ_2")
      (libsource (lib "eagle-import") (part "SJ2W"))
    )
    (comp (ref "SJ4") (value "SJ") (footprint "eagle-import:SJ") (libsource (lib "eagle-import") (part "SJ")))
    (comp (ref "SV4")
      (value "FE10-2W")
      (footprint "eagle-import:FE10-2W")
      (libsource (lib "eagle-import") (part "FE10-2W"))
    )
    (comp (ref "SV5")
      (value "FE10-2W")
      (footprint "eagle-import:FE10-2W")
      (libsource (lib "eagle-import") (part "FE10-2W"))
    )
    (comp (ref "C45")
      (value "15p")
      (footprint "eagle-import:C0805")
      (libsource (lib "eagle-import") (part "C-EUC0805"))
    )
    (comp (ref "C46")
      (value "15p")
      (footprint "eagle-import:C0805")
      (libsource (lib "eagle-import") (part "C-EUC0805"))
    )
    (comp (ref "C47")
      (value "100n")
      (footprint "eagle-import:C0805")
      (libsource (lib "eagle-import") (part "C-EUC0805"))
    )
    (comp (ref "C48")
      (value "100n")
      (footprint "eagle-import:C0805")
      (libsource (lib "eagle-import") (part "C-EUC0805"))
    )
    (comp (ref "IC9")
      (value "PIC16F877P")
      (footprint "eagle-import:DIL40")
      (libsource (lib "eagle-import") (part "PIC16F87P7"))
    )
    (comp (ref "JP9")
      (value "M05PTH")
      (footprint "eagle-import:1X05")
      (libsource (lib "eagle-import") (part "M05PTH"))
    )
    (comp (ref "LED9")
      (value "LED3MM")
      (footprint "eagle-import:LED3MM")
      (libsource (lib "eagle-import") (part "LED3MM"))
    )
    (comp (ref "Q10")
      (value "CRYSTALHC18U-V")
      (footprint "eagle-import:HC18U-V")
      (libsource (lib "eagle-import") (part "CRYSTALHC18U-V"))
    )
    (comp (ref "R15")
      (value "1K")
      (footprint "eagle-import:R0805")
      (libsource (lib "eagle-import") (part "R-EU_R0805"))
    )
    (comp (ref "R16")
      (value "10K")
      (footprint "eagle-import:R0805")
      (libsource (lib "eagle-import") (part "R-EU_R0805"))
    )
    (comp (ref "S9")
      (value "10-XX")
      (footprint "eagle-import:B3F-10XX")
      (fields
        (field (name "MPN") "B3F-1000")
        (field (name "MPN_1") "B3F-1000")
        (field (name "OC_FARNELL") "176432")
        (field (name "OC_NEWARK") "36M3542")
      )
      (libsource (lib "eagle-import") (part "10-XX"))
    )
    (comp (ref "SV18")
      (value "FE10-2W")
      (footprint "eagle-import:FE10-2W")
      (libsource (lib "eagle-import") (part "FE10-2W"))
    )
    (comp (ref "SV19")
      (value "FE10-2W")
      (footprint "eagle-import:FE10-2W")
      (fields (field (name "OC_FARNELL") "unknown") (field (name "OC_NEWARK") "unknown"))
      (libsource (lib "eagle-import") (part "FE10-2W"))
    )
    (comp (ref "C53")
      (value "15p")
      (footprint "eagle-import:C0805")
      (libsource (lib "eagle-import") (part "C-EUC0805"))
    )
    (comp (ref "C54")
      (value "15p")
      (footprint "eagle-import:C0805")
      (libsource (lib "eagle-import") (part "C-EUC0805"))
    )
    (comp (ref "C55")
      (value "100n")
      (footprint "eagle-import:C0805")
      (libsource (lib "eagle-import") (part "C-EUC0805"))
    )
    (comp (ref "IC11")
      (value "PIC18F2480-I/SP")
      (footprint "eagle-import:DIL28-3")
      (fields (field (name "MF") "MICROCHIP"))
      (libsource (lib "eagle-import") (part "PIC18F280-I/SP4"))
    )
    (comp (ref "JP11")
      (value "M05PTH")
      (footprint "eagle-import:1X05")
      (libsource (lib "eagle-import") (part "M05PTH"))
    )
    (comp (ref "LED11")
      (value "LED3MM")
      (footprint "eagle-import:LED3MM")
      (libsource (lib "eagle-import") (part "LED3MM"))
    )
    (comp (ref "Q12")
      (value "CRYSTALHC18U-V")
      (footprint "eagle-import:HC18U-V")
      (libsource (lib "eagle-import") (part "CRYSTALHC18U-V"))
    )
    (comp (ref "R18")
      (value "1K")
      (footprint "eagle-import:R0805")
      (libsource (lib "eagle-import") (part "R-EU_R0805"))
    )
    (comp (ref "R19")
      (value "10K")
      (footprint "eagle-import:R0805")
      (libsource (lib "eagle-import") (part "R-EU_R0805"))
    )
    (comp (ref "S11")
      (value "10-XX")
      (footprint "eagle-import:B3F-10XX")
      (fields
        (field (name "MPN") "B3F-1000")
        (field (name "MPN_1") "B3F-1000")
        (field (name "OC_FARNELL") "176432")
        (field (name "OC_NEWARK") "36M3542")
      )
      (libsource (lib "eagle-import") (part "10-XX"))
    )
    (comp (ref "SV22")
      (value "FE10-2W")
      (footprint "eagle-import:FE10-2W")
      (libsource (lib "eagle-import") (part "FE10-2W"))
    )
    (comp (ref "SV23")
      (value "FE10-2W")
      (footprint "eagle-import:FE10-2W")
      (fields (field (name "OC_FARNELL") "unknown") (field (name "OC_NEWARK") "unknown"))
      (libsource (lib "eagle-import") (part "FE10-2W"))
    )
    (comp (ref "C20")
      (value "100n")
      (footprint "eagle-import:C0805")
      (libsource (lib "eagle-import") (part "C-EUC0805"))
    )
    (comp (ref "C21")
      (value "100n")
      (footprint "eagle-import:C0805")
      (libsource (lib "eagle-import") (part "C-EUC0805"))
    )
    (comp (ref "C22")
      (value "100n")
      (footprint "eagle-import:C0805")
      (libsource (lib "eagle-import") (part "C-EUC0805"))
    )
    (comp (ref "C23")
      (value "18p")
      (footprint "eagle-import:C0805")
      (libsource (lib "eagle-import") (part "C-EUC0805"))
    )
    (comp (ref "C24")
      (value "18p")
      (footprint "eagle-import:C0805")
      (libsource (lib "eagle-import") (part "C-EUC0805"))
    )
    (comp (ref "C37")
      (value "100n")
      (footprint "eagle-import:C0805")
      (libsource (lib "eagle-import") (part "C-EUC0805"))
    )
    (comp (ref "JP6")
      (value "M05PTH")
      (footprint "eagle-import:1X05")
      (libsource (lib "eagle-import") (part "M05PTH"))
    )
    (comp (ref "LED6")
      (value "LEDCHIPLED_0805")
      (footprint "eagle-import:CHIPLED_0805")
      (libsource (lib "eagle-import") (part "LEDCHIPLED_0805"))
    )
    (comp (ref "Q7")
      (value "CRYSTALHC18U-V")
      (footprint "eagle-import:HC18U-V")
      (libsource (lib "eagle-import") (part "CRYSTALHC18U-V"))
    )
    (comp (ref "R11")
      (value "4K7")
      (footprint "eagle-import:R0805")
      (libsource (lib "eagle-import") (part "R-EU_R0805"))
    )
    (comp (ref "R12")
      (value "1K")
      (footprint "eagle-import:R0805")
      (libsource (lib "eagle-import") (part "R-EU_R0805"))
    )
    (comp (ref "S6")
      (value "10-XX")
      (footprint "eagle-import:B3F-10XX")
      (fields
        (field (name "MPN") "B3F-1000")
        (field (name "MPN_1") "B3F-1000")
        (field (name "OC_FARNELL") "176432")
        (field (name "OC_NEWARK") "36M3542")
      )
      (libsource (lib "eagle-import") (part "10-XX"))
    )
    (comp (ref "SV8")
      (value "FE10-2W")
      (footprint "eagle-import:FE10-2W")
      (libsource (lib "eagle-import") (part "FE10-2W"))
    )
    (comp (ref "SV13")
      (value "FE10-2W")
      (footprint "eagle-import:FE10-2W")
      (libsource (lib "eagle-import") (part "FE10-2W"))
    )
    (comp (ref "U$2")
      (value "DSPIC30F4011")
      (footprint "eagle-import:QFN44ML8X8")
      (libsource (lib "eagle-import") (part "DSPIC30F4011"))
    )
    (comp (ref "C1")
      (value "10uF")
      (footprint "eagle-import:SMC_C")
      (libsource (lib "eagle-import") (part "CPOL-EUSMCC"))
    )
    (comp (ref "C2")
      (value "100n")
      (footprint "eagle-import:C0805")
      (libsource (lib "eagle-import") (part "C-EUC0805"))
    )
    (comp (ref "C3")
      (value "100n")
      (footprint "eagle-import:C0805")
      (libsource (lib "eagle-import") (part "C-EUC0805"))
    )
    (comp (ref "C4")
      (value "18p")
      (footprint "eagle-import:C0805")
      (libsource (lib "eagle-import") (part "C-EUC0805"))
    )
    (comp (ref "C5")
      (value "18p")
      (footprint "eagle-import:C0805")
      (libsource (lib "eagle-import") (part "C-EUC0805"))
    )
    (comp (ref "C6")
      (value "100n")
      (footprint "eagle-import:C0805")
      (libsource (lib "eagle-import") (part "C-EUC0805"))
    )
    (comp (ref "C7")
      (value "100n")
      (footprint "eagle-import:C0805")
      (libsource (lib "eagle-import") (part "C-EUC0805"))
    )
    (comp (ref "C8")
      (value "100n")
      (footprint "eagle-import:C0805")
      (libsource (lib "eagle-import") (part "C-EUC0805"))
    )
    (comp (ref "C26")
      (value "18p")
      (footprint "eagle-import:C0805")
      (libsource (lib "eagle-import") (part "C-EUC0805"))
    )
    (comp (ref "C31")
      (value "18p")
      (footprint "eagle-import:C0805")
      (libsource (lib "eagle-import") (part "C-EUC0805"))
    )
    (comp (ref "IC1")
      (value "PIC32MX")
      (footprint "eagle-import:TQFP64-10X10")
      (libsource (lib "eagle-import") (part "PIC32MX440F256H"))
    )
    (comp (ref "JMP1")
      (value "0R-JUMPA")
      (footprint "eagle-import:A0R-JMP")
      (libsource (lib "eagle-import") (part "0R-JUMPA"))
    )
    (comp (ref "JMP2")
      (value "0R-JUMPA")
      (footprint "eagle-import:A0R-JMP")
      (libsource (lib "eagle-import") (part "0R-JUMPA"))
    )
    (comp (ref "JP4")
      (value "M05PTH")
      (footprint "eagle-import:1X05")
      (libsource (lib "eagle-import") (part "M05PTH"))
    )
    (comp (ref "LED1")
      (value "LEDCHIPLED_0805")
      (footprint "eagle-import:CHIPLED_0805")
      (libsource (lib "eagle-import") (part "LEDCHIPLED_0805"))
    )
    (comp (ref "Q1")
      (value "CRYSTALHC18U-V")
      (footprint "eagle-import:HC18U-V")
      (libsource (lib "eagle-import") (part "CRYSTALHC18U-V"))
    )
    (comp (ref "Q5")
      (value "CRYSTALHC18U-V")
      (footprint "eagle-import:HC18U-V")
      (libsource (lib "eagle-import") (part "CRYSTALHC18U-V"))
    )
    (comp (ref "R1")
      (value "4K7")
      (footprint "eagle-import:R0805")
      (libsource (lib "eagle-import") (part "R-EU_R0805"))
    )
    (comp (ref "R2")
      (value "1K")
      (footprint "eagle-import:R0805")
      (libsource (lib "eagle-import") (part "R-EU_R0805"))
    )
    (comp (ref "S1")
      (value "10-XX")
      (footprint "eagle-import:B3F-10XX")
      (fields
        (field (name "MPN") "B3F-1000")
        (field (name "MPN_1") "B3F-1000")
        (field (name "OC_FARNELL") "176432")
        (field (name "OC_NEWARK") "36M3542")
      )
      (libsource (lib "eagle-import") (part "10-XX"))
    )
    (comp (ref "SV1")
      (value "FE10-2W")
      (footprint "eagle-import:FE10-2W")
      (libsource (lib "eagle-import") (part "FE10-2W"))
    )
    (comp (ref "SV2")
      (value "FE10-2W")
      (footprint "eagle-import:FE10-2W")
      (libsource (lib "eagle-import") (part "FE10-2W"))
    )
    (comp (ref "SV3")
      (value "FE10-2W")
      (footprint "eagle-import:FE10-2W")
      (libsource (lib "eagle-import") (part "FE10-2W"))
    )
  )
  (nets
    (net (code "1") (name "MCLR") (class "Default")
      (node (ref "IC1") (pin "7") (pinfunction "~{MCLR}_7") (pintype "input"))
      (node (ref "JP4") (pin "1") (pinfunction "1_1") (pintype "passive"))
      (node (ref "R1") (pin "1") (pinfunction "1_1") (pintype "passive"))
      (node (ref "S1") (pin "1") (pinfunction "S_1") (pintype "passive"))
      (node (ref "SV3") (pin "2") (pinfunction "2_2") (pintype "passive"))
    )
    (net (code "2") (name "N$9") (class "Default")
      (node (ref "IC6") (pin "1") (pinfunction "1_1") (pintype "passive"))
    )
    (net (code "3") (name "N$14") (class "Default")
      (node (ref "IC6") (pin "6") (pinfunction "6_6") (pintype "passive"))
    )
    (net (code "4") (name "N$16") (class "Default")
      (node (ref "SV23") (pin "16") (pinfunction "16_16") (pintype "passive"))
    )
    (net (code "5") (name "N$17") (class "Default")
      (node (ref "SV23") (pin "14") (pinfunction "14_14") (pintype "passive"))
    )
    (net (code "6") (name "N$18") (class "Default")
      (node (ref "SV22") (pin "16") (pinfunction "16_16") (pintype "passive"))
    )
    (net (code "7") (name "N$19") (class "Default")
      (node (ref "SV22") (pin "18") (pinfunction "18_18") (pintype "passive"))
    )
    (net (code "8") (name "N$20") (class "Default")
      (node (ref "SV23") (pin "15") (pinfunction "15_15") (pintype "passive"))
    )
    (net (code "9") (name "N$21") (class "Default")
      (node (ref "SV23") (pin "13") (pinfunction "13_13") (pintype "passive"))
    )
    (net (code "10") (name "N$29") (class "Default")
      (node (ref "C16") (pin "+") (pinfunction "+_+") (pintype "passive"))
      (node (ref "U$1") (pin "20") (pinfunction "PIN20_20") (pintype "input"))
    )
    (net (code "11") (name "N$71") (class "Default")
      (node (ref "SV7") (pin "12") (pinfunction "12_12") (pintype "passive"))
    )
    (net (code "12") (name "Net-(C1-Pad+)") (class "Default")
      (node (ref "C1") (pin "+") (pinfunction "+_+") (pintype "passive"))
      (node (ref "JMP1") (pin "1") (pinfunction "1_1") (pintype "passive"))
    )
    (net (code "13") (name "Net-(IC3-VDDCORE)") (class "Default")
      (node (ref "C9") (pin "+") (pinfunction "+_+") (pintype "passive"))
      (node (ref "C9B") (pin "1") (pinfunction "1_1") (pintype "passive"))
      (node (ref "IC3") (pin "7") (pinfunction "VDDCORE_7") (pintype "power_in"))
      (node (ref "SJ4") (pin "1") (pinfunction "1_1") (pintype "passive"))
    )
    (net (code "14") (name "Net-(LED1-PadA)") (class "Default")
      (node (ref "LED1") (pin "A") (pinfunction "A_A") (pintype "passive"))
      (node (ref "R2") (pin "1") (pinfunction "1_1") (pintype "passive"))
    )
    (net (code "15") (name "Net-(LED2-PadA)") (class "Default")
      (node (ref "LED2") (pin "A") (pinfunction "A_A") (pintype "passive"))
      (node (ref "R4") (pin "1") (pinfunction "1_1") (pintype "passive"))
    )
    (net (code "16") (name "Net-(LED3-PadA)") (class "Default")
      (node (ref "LED3") (pin "A") (pinfunction "A_A") (pintype "passive"))
      (node (ref "R5") (pin "1") (pinfunction "1_1") (pintype "passive"))
    )
    (net (code "17") (name "Net-(LED4-PadA)") (class "Default")
      (node (ref "LED4") (pin "A") (pinfunction "A_A") (pintype "passive"))
      (node (ref "R7") (pin "1") (pinfunction "1_1") (pintype "passive"))
    )
    (net (code "18") (name "Net-(LED5-PadA)") (class "Default")
      (node (ref "LED5") (pin "A") (pinfunction "A_A") (pintype "passive"))
      (node (ref "R9") (pin "1") (pinfunction "1_1") (pintype "passive"))
    )
    (net (code "19") (name "Net-(LED6-PadA)") (class "Default")
      (node (ref "LED6") (pin "A") (pinfunction "A_A") (pintype "passive"))
      (node (ref "R12") (pin "1") (pinfunction "1_1") (pintype "passive"))
    )
    (net (code "20") (name "Net-(LED7-PadA)") (class "Default")
      (node (ref "LED7") (pin "A") (pinfunction "A_A") (pintype "passive"))
      (node (ref "R13") (pin "1") (pinfunction "1_1") (pintype "passive"))
    )
    (net (code "21") (name "Net-(LED8-PadA)") (class "Default")
      (node (ref "LED8") (pin "A") (pinfunction "A_A") (pintype "passive"))
      (node (ref "R14") (pin "1") (pinfunction "1_1") (pintype "passive"))
    )
    (net (code "22") (name "Net-(LED9-PadA)") (class "Default")
      (node (ref "LED9") (pin "A") (pinfunction "A_A") (pintype "passive"))
      (node (ref "R15") (pin "1") (pinfunction "1_1") (pintype "passive"))
    )
    (net (code "23") (name "Net-(LED10-PadA)") (class "Default")
      (node (ref "LED10") (pin "A") (pinfunction "A_A") (pintype "passive"))
      (node (ref "R17") (pin "1") (pinfunction "1_1") (pintype "passive"))
    )
    (net (code "24") (name "Net-(LED11-PadA)") (class "Default")
      (node (ref "LED11") (pin "A") (pinfunction "A_A") (pintype "passive"))
      (node (ref "R18") (pin "1") (pinfunction "1_1") (pintype "passive"))
    )
    (net (code "25") (name "P1") (class "Default")
      (node (ref "IC1") (pin "1") (pinfunction "RE5_1") (pintype "bidirectional"))
      (node (ref "SV3") (pin "15") (pinfunction "15_15") (pintype "passive"))
    )
    (net (code "26") (name "P1OSC1") (class "Default")
      (node (ref "C4") (pin "1") (pinfunction "1_1") (pintype "passive"))
      (node (ref "IC1") (pin "39") (pinfunction "RC12_39") (pintype "bidirectional"))
      (node (ref "Q1") (pin "2") (pinfunction "2_2") (pintype "passive"))
      (node (ref "SV1") (pin "8") (pinfunction "8_8") (pintype "passive"))
    )
    (net (code "27") (name "P1OSC2") (class "Default")
      (node (ref "C5") (pin "1") (pinfunction "1_1") (pintype "passive"))
      (node (ref "IC1") (pin "40") (pinfunction "RC15_40") (pintype "bidirectional"))
      (node (ref "Q1") (pin "1") (pinfunction "1_1") (pintype "passive"))
      (node (ref "SV1") (pin "9") (pinfunction "9_9") (pintype "passive"))
    )
    (net (code "28") (name "P1SOSCI") (class "Default")
      (node (ref "C26") (pin "1") (pinfunction "1_1") (pintype "passive"))
      (node (ref "IC1") (pin "47") (pinfunction "RC13_47") (pintype "bidirectional"))
      (node (ref "Q5") (pin "2") (pinfunction "2_2") (pintype "passive"))
      (node (ref "SV1") (pin "15") (pinfunction "15_15") (pintype "passive"))
    )
    (net (code "29") (name "P1SOSCO") (class "Default")
      (node (ref "C31") (pin "1") (pinfunction "1_1") (pintype "passive"))
      (node (ref "IC1") (pin "48") (pinfunction "RC14_48") (pintype "bidirectional"))
      (node (ref "Q5") (pin "1") (pinfunction "1_1") (pintype "passive"))
      (node (ref "SV1") (pin "16") (pinfunction "16_16") (pintype "passive"))
    )
    (net (code "30") (name "P2") (class "Default")
      (node (ref "IC1") (pin "2") (pinfunction "RE6_2") (pintype "bidirectional"))
      (node (ref "SV3") (pin "18") (pinfunction "18_18") (pintype "passive"))
    )
    (net (code "31") (name "P2GC") (class "Default")
      (node (ref "JP1") (pin "5") (pinfunction "5_5") (pintype "passive"))
      (node (ref "SJ2") (pin "2") (pinfunction "2_2") (pintype "passive"))
    )
    (net (code "32") (name "P2GD") (class "Default")
      (node (ref "JP1") (pin "4") (pinfunction "4_4") (pintype "passive"))
      (node (ref "SJ1") (pin "2") (pinfunction "2_2") (pintype "passive"))
    )
    (net (code "33") (name "P2MCLR") (class "Default")
      (node (ref "IC3") (pin "18") (pinfunction "~{MCLR}_18") (pintype "bidirectional"))
      (node (ref "JP1") (pin "1") (pinfunction "1_1") (pintype "passive"))
      (node (ref "R3") (pin "1") (pinfunction "1_1") (pintype "passive"))
      (node (ref "S2") (pin "1") (pinfunction "S_1") (pintype "passive"))
      (node (ref "SV4") (pin "2") (pinfunction "2_2") (pintype "passive"))
    )
    (net (code "34") (name "P2OSC1") (class "Default")
      (node (ref "C13") (pin "1") (pinfunction "1_1") (pintype "passive"))
      (node (ref "IC3") (pin "30") (pinfunction "RA2_30") (pintype "bidirectional"))
      (node (ref "Q2") (pin "2") (pinfunction "2_2") (pintype "passive"))
      (node (ref "SV5") (pin "14") (pinfunction "14_14") (pintype "passive"))
    )
    (net (code "35") (name "P2OSC2") (class "Default")
      (node (ref "C14") (pin "1") (pinfunction "1_1") (pintype "passive"))
      (node (ref "IC3") (pin "31") (pinfunction "RA3_31") (pintype "bidirectional"))
      (node (ref "Q2") (pin "1") (pinfunction "1_1") (pintype "passive"))
      (node (ref "SV5") (pin "13") (pinfunction "13_13") (pintype "passive"))
    )
    (net (code "36") (name "P3") (class "Default")
      (node (ref "IC1") (pin "3") (pinfunction "RE7_3") (pintype "bidirectional"))
      (node (ref "SV3") (pin "17") (pinfunction "17_17") (pintype "passive"))
    )
    (net (code "37") (name "P3GC") (class "Default")
      (node (ref "JP5") (pin "5") (pinfunction "5_5") (pintype "passive"))
      (node (ref "SV6") (pin "20") (pinfunction "20_20") (pintype "passive"))
      (node (ref "U$1") (pin "5") (pinfunction "PIN5_5") (pintype "input"))
    )
    (net (code "38") (name "P3GD") (class "Default")
      (node (ref "JP5") (pin "4") (pinfunction "4_4") (pintype "passive"))
      (node (ref "SV6") (pin "19") (pinfunction "19_19") (pintype "passive"))
      (node (ref "U$1") (pin "4") (pinfunction "PIN4_4") (pintype "input"))
    )
    (net (code "39") (name "P3MCLR") (class "Default")
      (node (ref "JP5") (pin "1") (pinfunction "1_1") (pintype "passive"))
      (node (ref "R10") (pin "1") (pinfunction "1_1") (pintype "passive"))
      (node (ref "S3") (pin "1") (pinfunction "S_1") (pintype "passive"))
      (node (ref "SV6") (pin "10") (pinfunction "10_10") (pintype "passive"))
      (node (ref "SV6") (pin "9") (pinfunction "9_9") (pintype "passive"))
      (node (ref "U$1") (pin "1") (pinfunction "PIN1_1") (pintype "input"))
    )
    (net (code "40") (name "P3OSC1") (class "Default")
      (node (ref "C18") (pin "1") (pinfunction "1_1") (pintype "passive"))
      (node (ref "Q3") (pin "1") (pinfunction "1_1") (pintype "passive"))
      (node (ref "SV7") (pin "5") (pinfunction "5_5") (pintype "passive"))
      (node (ref "U$1") (pin "9") (pinfunction "PIN9_9") (pintype "input"))
    )
    (net (code "41") (name "P3OSC2") (class "Default")
      (node (ref "C17") (pin "1") (pinfunction "1_1") (pintype "passive"))
      (node (ref "Q3") (pin "2") (pinfunction "2_2") (pintype "passive"))
      (node (ref "SV7") (pin "6") (pinfunction "6_6") (pintype "passive"))
      (node (ref "U$1") (pin "10") (pinfunction "PIN10_10") (pintype "input"))
    )
    (net (code "42") (name "P4") (class "Default")
      (node (ref "IC1") (pin "4") (pinfunction "RG6_4") (pintype "bidirectional"))
      (node (ref "SV3") (pin "20") (pinfunction "20_20") (pintype "passive"))
    )
    (net (code "43") (name "P4GC") (class "Default")
      (node (ref "IC4") (pin "16") (pinfunction "ICDCLK/ICSPCLK/RB6_16") (pintype "bidirectional"))
      (node (ref "JP2") (pin "5") (pinfunction "5_5") (pintype "passive"))
      (node (ref "SV10") (pin "3") (pinfunction "3_3") (pintype "passive"))
    )
    (net (code "44") (name "P4GD") (class "Default")
      (node (ref "IC4") (pin "17") (pinfunction "ICDDAT/ICSPDAT/RB7_17") (pintype "bidirectional"))
      (node (ref "JP2") (pin "4") (pinfunction "4_4") (pintype "passive"))
      (node (ref "SV10") (pin "4") (pinfunction "4_4") (pintype "passive"))
    )
    (net (code "45") (name "P4MCLR") (class "Default")
      (node (ref "IC4") (pin "18") (pinfunction "VPP/~{MCLR}/RE3_18") (pintype "input"))
      (node (ref "JP2") (pin "1") (pinfunction "1_1") (pintype "passive"))
      (node (ref "R6") (pin "1") (pinfunction "1_1") (pintype "passive"))
      (node (ref "S4") (pin "1") (pinfunction "S_1") (pintype "passive"))
      (node (ref "SV9") (pin "2") (pinfunction "2_2") (pintype "passive"))
    )
    (net (code "46") (name "P4OSC1") (class "Default")
      (node (ref "C29") (pin "1") (pinfunction "1_1") (pintype "passive"))
      (node (ref "IC4") (pin "30") (pinfunction "RA7/OSC1/CLKIN_30") (pintype "bidirectional"))
      (node (ref "Q4") (pin "2") (pinfunction "2_2") (pintype "passive"))
      (node (ref "SV10") (pin "14") (pinfunction "14_14") (pintype "passive"))
    )
    (net (code "47") (name "P4OSC2") (class "Default")
      (node (ref "C30") (pin "1") (pinfunction "1_1") (pintype "passive"))
      (node (ref "IC4") (pin "31") (pinfunction "RA6/OSC2/CLKOUT_31") (pintype "bidirectional"))
      (node (ref "Q4") (pin "1") (pinfunction "1_1") (pintype "passive"))
      (node (ref "SV10") (pin "15") (pinfunction "15_15") (pintype "passive"))
    )
    (net (code "48") (name "P5") (class "Default")
      (node (ref "IC1") (pin "5") (pinfunction "RG7_5") (pintype "bidirectional"))
      (node (ref "SV3") (pin "19") (pinfunction "19_19") (pintype "passive"))
    )
    (net (code "49") (name "P5GC") (class "Default")
      (node (ref "IC2") (pin "6") (pinfunction "6_6") (pintype "passive"))
      (node (ref "IC5") (pin "12") (pinfunction "12_12") (pintype "passive"))
      (node (ref "IC6") (pin "4") (pinfunction "4_4") (pintype "passive"))
      (node (ref "JP3") (pin "5") (pinfunction "5_5") (pintype "passive"))
      (node (ref "SV11") (pin "11") (pinfunction "11_11") (pintype "passive"))
      (node (ref "SV11") (pin "5") (pinfunction "5_5") (pintype "passive"))
      (node (ref "SV12") (pin "9") (pinfunction "9_9") (pintype "passive"))
    )
    (net (code "50") (name "P5GD") (class "Default")
      (node (ref "IC2") (pin "7") (pinfunction "7_7") (pintype "passive"))
      (node (ref "IC5") (pin "13") (pinfunction "13_13") (pintype "passive"))
      (node (ref "IC6") (pin "5") (pinfunction "5_5") (pintype "passive"))
      (node (ref "JP3") (pin "4") (pinfunction "4_4") (pintype "passive"))
      (node (ref "SV11") (pin "12") (pinfunction "12_12") (pintype "passive"))
      (node (ref "SV11") (pin "3") (pinfunction "3_3") (pintype "passive"))
      (node (ref "SV12") (pin "11") (pinfunction "11_11") (pintype "passive"))
    )
    (net (code "51") (name "P5MCLR") (class "Default")
      (node (ref "IC2") (pin "4") (pinfunction "4_4") (pintype "passive"))
      (node (ref "IC5") (pin "4") (pinfunction "4_4") (pintype "passive"))
      (node (ref "IC6") (pin "8") (pinfunction "8_8") (pintype "passive"))
      (node (ref "JP3") (pin "1") (pinfunction "1_1") (pintype "passive"))
      (node (ref "R8") (pin "1") (pinfunction "1_1") (pintype "passive"))
      (node (ref "S5") (pin "1") (pinfunction "S_1") (pintype "passive"))
      (node (ref "SV11") (pin "1") (pinfunction "1_1") (pintype "passive"))
      (node (ref "SV11") (pin "15") (pinfunction "15_15") (pintype "passive"))
      (node (ref "SV12") (pin "8") (pinfunction "8_8") (pintype "passive"))
    )
    (net (code "52") (name "P5OSC1") (class "Default")
      (node (ref "C33") (pin "1") (pinfunction "1_1") (pintype "passive"))
      (node (ref "IC5") (pin "2") (pinfunction "2_2") (pintype "passive"))
      (node (ref "Q6") (pin "2") (pinfunction "2_2") (pintype "passive"))
      (node (ref "SV12") (pin "12") (pinfunction "12_12") (pintype "passive"))
    )
    (net (code "53") (name "P5OSC2") (class "Default")
      (node (ref "C34") (pin "1") (pinfunction "1_1") (pintype "passive"))
      (node (ref "IC5") (pin "3") (pinfunction "3_3") (pintype "passive"))
      (node (ref "Q6") (pin "1") (pinfunction "1_1") (pintype "passive"))
      (node (ref "SV12") (pin "10") (pinfunction "10_10") (pintype "passive"))
    )
    (net (code "54") (name "P6") (class "Default")
      (node (ref "IC1") (pin "6") (pinfunction "RG8_6") (pintype "bidirectional"))
      (node (ref "SV2") (pin "2") (pinfunction "2_2") (pintype "passive"))
    )
    (net (code "55") (name "P6GC") (class "Default")
      (node (ref "JP6") (pin "5") (pinfunction "5_5") (pintype "passive"))
      (node (ref "SV8") (pin "9") (pinfunction "9_9") (pintype "passive"))
      (node (ref "U$2") (pin "1") (pinfunction "01.PGC_1") (pintype "bidirectional"))
    )
    (net (code "56") (name "P6GD") (class "Default")
      (node (ref "JP6") (pin "4") (pinfunction "4_4") (pintype "passive"))
      (node (ref "SV8") (pin "10") (pinfunction "10_10") (pintype "passive"))
      (node (ref "U$2") (pin "44") (pinfunction "44.PGD_44") (pintype "bidirectional"))
    )
    (net (code "57") (name "P6MCLR") (class "Default")
      (node (ref "JP6") (pin "1") (pinfunction "1_1") (pintype "passive"))
      (node (ref "R11") (pin "1") (pinfunction "1_1") (pintype "passive"))
      (node (ref "S6") (pin "1") (pinfunction "S_1") (pintype "passive"))
      (node (ref "SV13") (pin "6") (pinfunction "6_6") (pintype "passive"))
      (node (ref "U$2") (pin "18") (pinfunction "18./MCLR_18") (pintype "bidirectional"))
    )
    (net (code "58") (name "P6OSC1") (class "Default")
      (node (ref "C23") (pin "1") (pinfunction "1_1") (pintype "passive"))
      (node (ref "Q7") (pin "2") (pinfunction "2_2") (pintype "passive"))
      (node (ref "SV13") (pin "16") (pinfunction "16_16") (pintype "passive"))
      (node (ref "U$2") (pin "32") (pinfunction "32.OSC1_32") (pintype "bidirectional"))
    )
    (net (code "59") (name "P6OSC2") (class "Default")
      (node (ref "C24") (pin "1") (pinfunction "1_1") (pintype "passive"))
      (node (ref "Q7") (pin "1") (pinfunction "1_1") (pintype "passive"))
      (node (ref "SV13") (pin "15") (pinfunction "15_15") (pintype "passive"))
      (node (ref "U$2") (pin "33") (pinfunction "33.OSC2_33") (pintype "bidirectional"))
    )
    (net (code "60") (name "P7MCLR") (class "Default")
      (node (ref "IC7") (pin "9") (pinfunction "RESET_9") (pintype "input"))
      (node (ref "JP8") (pin "5") (pinfunction "5_5") (pintype "passive"))
      (node (ref "S7") (pin "1") (pinfunction "S_1") (pintype "passive"))
      (node (ref "S7") (pin "2") (pinfunction "S1_2") (pintype "passive"))
      (node (ref "SV14") (pin "18") (pinfunction "18_18") (pintype "passive"))
    )
    (net (code "61") (name "P7OSC1") (class "Default")
      (node (ref "C40") (pin "1") (pinfunction "1_1") (pintype "passive"))
      (node (ref "IC7") (pin "19") (pinfunction "XTAL1_19") (pintype "bidirectional"))
      (node (ref "Q8") (pin "2") (pinfunction "2_2") (pintype "passive"))
    )
    (net (code "62") (name "P7OSC2") (class "Default")
      (node (ref "C39") (pin "1") (pinfunction "1_1") (pintype "passive"))
      (node (ref "IC7") (pin "18") (pinfunction "XTAL2_18") (pintype "bidirectional"))
      (node (ref "Q8") (pin "1") (pinfunction "1_1") (pintype "passive"))
    )
    (net (code "63") (name "P8") (class "Default")
      (node (ref "IC1") (pin "8") (pinfunction "RG9_8") (pintype "bidirectional"))
      (node (ref "SV2") (pin "1") (pinfunction "1_1") (pintype "passive"))
    )
    (net (code "64") (name "P8MCLR") (class "Default")
      (node (ref "IC8") (pin "9") (pinfunction "RESET_9") (pintype "input"))
      (node (ref "JP7") (pin "5") (pinfunction "5_5") (pintype "passive"))
      (node (ref "S8") (pin "1") (pinfunction "S_1") (pintype "passive"))
      (node (ref "S8") (pin "2") (pinfunction "S1_2") (pintype "passive"))
      (node (ref "SV16") (pin "19") (pinfunction "19_19") (pintype "passive"))
    )
    (net (code "65") (name "P8OSC1") (class "Default")
      (node (ref "C43") (pin "1") (pinfunction "1_1") (pintype "passive"))
      (node (ref "IC8") (pin "13") (pinfunction "XTAL1_13") (pintype "bidirectional"))
      (node (ref "Q9") (pin "2") (pinfunction "2_2") (pintype "passive"))
    )
    (net (code "66") (name "P8OSC2") (class "Default")
      (node (ref "C42") (pin "1") (pinfunction "1_1") (pintype "passive"))
      (node (ref "IC8") (pin "12") (pinfunction "XTAL2_12") (pintype "bidirectional"))
      (node (ref "Q9") (pin "1") (pinfunction "1_1") (pintype "passive"))
    )
    (net (code "67") (name "P9GC") (class "Default")
      (node (ref "IC9") (pin "39") (pinfunction "PGC/RB6_39") (pintype "bidirectional"))
      (node (ref "JP9") (pin "5") (pinfunction "5_5") (pintype "passive"))
      (node (ref "SV19") (pin "12") (pinfunction "12_12") (pintype "passive"))
    )
    (net (code "68") (name "P9GD") (class "Default")
      (node (ref "IC9") (pin "40") (pinfunction "PGD/RB7_40") (pintype "bidirectional"))
      (node (ref "JP9") (pin "4") (pinfunction "4_4") (pintype "passive"))
      (node (ref "SV19") (pin "14") (pinfunction "14_14") (pintype "passive"))
    )
    (net (code "69") (name "P9MCLR") (class "Default")
      (node (ref "IC9") (pin "1") (pinfunction "~{MCLR/THV}_1") (pintype "input"))
      (node (ref "JP9") (pin "1") (pinfunction "1_1") (pintype "passive"))
      (node (ref "R16") (pin "2") (pinfunction "2_2") (pintype "passive"))
      (node (ref "S9") (pin "1") (pinfunction "S_1") (pintype "passive"))
      (node (ref "S9") (pin "2") (pinfunction "S1_2") (pintype "passive"))
      (node (ref "SV19") (pin "16") (pinfunction "16_16") (pintype "passive"))
    )
    (net (code "70") (name "P9OSC1") (class "Default")
      (node (ref "C46") (pin "1") (pinfunction "1_1") (pintype "passive"))
      (node (ref "IC9") (pin "13") (pinfunction "OSC1/CLKIN_13") (pintype "input"))
      (node (ref "Q10") (pin "2") (pinfunction "2_2") (pintype "passive"))
      (node (ref "SV18") (pin "16") (pinfunction "16_16") (pintype "passive"))
    )
    (net (code "71") (name "P9OSC2") (class "Default")
      (node (ref "C45") (pin "1") (pinfunction "1_1") (pintype "passive"))
      (node (ref "IC9") (pin "14") (pinfunction "OSC2/CLKOUT_14") (pintype "output"))
      (node (ref "Q10") (pin "1") (pinfunction "1_1") (pintype "passive"))
      (node (ref "SV18") (pin "14") (pinfunction "14_14") (pintype "passive"))
    )
    (net (code "72") (name "P10MCLR") (class "Default")
      (node (ref "JP10") (pin "2") (pinfunction "2_2") (pintype "passive"))
      (node (ref "S10") (pin "3") (pinfunction "P_3") (pintype "passive"))
      (node (ref "S10") (pin "4") (pinfunction "P1_4") (pintype "passive"))
      (node (ref "U$3") (pin "11") (pinfunction "RES/_11") (pintype "bidirectional"))
    )
    (net (code "73") (name "P10OSC1") (class "Default")
      (node (ref "C50") (pin "1") (pinfunction "1_1") (pintype "passive"))
      (node (ref "Q11") (pin "1") (pinfunction "1_1") (pintype "passive"))
      (node (ref "U$3") (pin "30") (pinfunction "XI_30") (pintype "input"))
    )
    (net (code "74") (name "P10OSC2") (class "Default")
      (node (ref "C51") (pin "1") (pinfunction "1_1") (pintype "passive"))
      (node (ref "Q11") (pin "2") (pinfunction "2_2") (pintype "passive"))
      (node (ref "U$3") (pin "31") (pinfunction "XO_31") (pintype "output"))
    )
    (net (code "75") (name "P10RX") (class "Default")
      (node (ref "JP10") (pin "3") (pinfunction "3_3") (pintype "passive"))
      (node (ref "SV20") (pin "2") (pinfunction "2_2") (pintype "passive"))
      (node (ref "U$3") (pin "40") (pinfunction "P31_40") (pintype "bidirectional"))
    )
    (net (code "76") (name "P10SCL") (class "Default")
      (node (ref "IC10") (pin "6") (pinfunction "SCL_6") (pintype "input"))
      (node (ref "SV20") (pin "8") (pinfunction "8_8") (pintype "passive"))
      (node (ref "U$3") (pin "37") (pinfunction "P28_37") (pintype "bidirectional"))
    )
    (net (code "77") (name "P10SDA") (class "Default")
      (node (ref "IC10") (pin "5") (pinfunction "SDA_5") (pintype "bidirectional"))
      (node (ref "SV20") (pin "6") (pinfunction "6_6") (pintype "passive"))
      (node (ref "U$3") (pin "38") (pinfunction "P29_38") (pintype "bidirectional"))
    )
    (net (code "78") (name "P10TX") (class "Default")
      (node (ref "JP10") (pin "4") (pinfunction "4_4") (pintype "passive"))
      (node (ref "SV20") (pin "4") (pinfunction "4_4") (pintype "passive"))
      (node (ref "U$3") (pin "39") (pinfunction "P30_39") (pintype "bidirectional"))
    )
    (net (code "79") (name "P11") (class "Default")
      (node (ref "IC1") (pin "11") (pinfunction "RB5_11") (pintype "bidirectional"))
      (node (ref "SV2") (pin "4") (pinfunction "4_4") (pintype "passive"))
    )
    (net (code "80") (name "P11GC") (class "Default")
      (node (ref "IC11") (pin "27") (pinfunction "KBI2/PGC/RB6_27") (pintype "bidirectional"))
      (node (ref "JP11") (pin "5") (pinfunction "5_5") (pintype "passive"))
      (node (ref "SV23") (pin "7") (pinfunction "7_7") (pintype "passive"))
    )
    (net (code "81") (name "P11GD") (class "Default")
      (node (ref "IC11") (pin "28") (pinfunction "KBI3/PGD/RB7_28") (pintype "bidirectional"))
      (node (ref "JP11") (pin "4") (pinfunction "4_4") (pintype "passive"))
      (node (ref "SV23") (pin "9") (pinfunction "9_9") (pintype "passive"))
    )
    (net (code "82") (name "P11MCLR") (class "Default")
      (node (ref "IC11") (pin "1") (pinfunction "RE3/~{MCLR/VPP}_1") (pintype "input"))
      (node (ref "JP11") (pin "1") (pinfunction "1_1") (pintype "passive"))
      (node (ref "R19") (pin "2") (pinfunction "2_2") (pintype "passive"))
      (node (ref "S11") (pin "1") (pinfunction "S_1") (pintype "passive"))
      (node (ref "S11") (pin "2") (pinfunction "S1_2") (pintype "passive"))
      (node (ref "SV23") (pin "11") (pinfunction "11_11") (pintype "passive"))
      (node (ref "SV23") (pin "12") (pinfunction "12_12") (pintype "passive"))
    )
    (net (code "83") (name "P11OSC1") (class "Default")
      (node (ref "C54") (pin "1") (pinfunction "1_1") (pintype "passive"))
      (node (ref "IC11") (pin "9") (pinfunction "RA7/CLKI/OSC1_9") (pintype "input"))
      (node (ref "Q12") (pin "2") (pinfunction "2_2") (pintype "passive"))
      (node (ref "SV22") (pin "10") (pinfunction "10_10") (pintype "passive"))
    )
    (net (code "84") (name "P11OSC2") (class "Default")
      (node (ref "C53") (pin "1") (pinfunction "1_1") (pintype "passive"))
      (node (ref "IC11") (pin "10") (pinfunction "RA6/CLKO/OSC2_10") (pintype "output"))
      (node (ref "Q12") (pin "1") (pinfunction "1_1") (pintype "passive"))
      (node (ref "SV22") (pin "8") (pinfunction "8_8") (pintype "passive"))
    )
    (net (code "85") (name "P12") (class "Default")
      (node (ref "IC1") (pin "12") (pinfunction "RB4_12") (pintype "bidirectional"))
      (node (ref "SV2") (pin "3") (pinfunction "3_3") (pintype "passive"))
    )
    (net (code "86") (name "P13") (class "Default")
      (node (ref "IC1") (pin "13") (pinfunction "RB3_13") (pintype "bidirectional"))
      (node (ref "SV2") (pin "6") (pinfunction "6_6") (pintype "passive"))
    )
    (net (code "87") (name "P14") (class "Default")
      (node (ref "IC1") (pin "14") (pinfunction "RB2_14") (pintype "bidirectional"))
      (node (ref "SV2") (pin "5") (pinfunction "5_5") (pintype "passive"))
    )
    (net (code "88") (name "P15") (class "Default")
      (node (ref "IC1") (pin "15") (pinfunction "RB1_15") (pintype "bidirectional"))
      (node (ref "SV2") (pin "8") (pinfunction "8_8") (pintype "passive"))
    )
    (net (code "89") (name "P16") (class "Default")
      (node (ref "IC1") (pin "16") (pinfunction "RB0_16") (pintype "bidirectional"))
      (node (ref "SV2") (pin "7") (pinfunction "7_7") (pintype "passive"))
    )
    (net (code "90") (name "P21") (class "Default")
      (node (ref "IC1") (pin "21") (pinfunction "RB8_21") (pintype "bidirectional"))
      (node (ref "SV2") (pin "13") (pinfunction "13_13") (pintype "passive"))
    )
    (net (code "91") (name "P22") (class "Default")
      (node (ref "IC1") (pin "22") (pinfunction "RB9_22") (pintype "bidirectional"))
      (node (ref "SV2") (pin "14") (pinfunction "14_14") (pintype "passive"))
    )
    (net (code "92") (name "P23") (class "Default")
      (node (ref "IC1") (pin "23") (pinfunction "TMS_23") (pintype "input"))
      (node (ref "SV2") (pin "15") (pinfunction "15_15") (pintype "passive"))
    )
    (net (code "93") (name "P24") (class "Default")
      (node (ref "IC1") (pin "24") (pinfunction "TDO_24") (pintype "output"))
      (node (ref "SV2") (pin "16") (pinfunction "16_16") (pintype "passive"))
    )
    (net (code "94") (name "P27") (class "Default")
      (node (ref "IC1") (pin "27") (pinfunction "TCK_27") (pintype "input"))
      (node (ref "SV2") (pin "17") (pinfunction "17_17") (pintype "passive"))
    )
    (net (code "95") (name "P28") (class "Default")
      (node (ref "IC1") (pin "28") (pinfunction "TDI_28") (pintype "input"))
      (node (ref "SV2") (pin "18") (pinfunction "18_18") (pintype "passive"))
    )
    (net (code "96") (name "P29") (class "Default")
      (node (ref "IC1") (pin "29") (pinfunction "RB14_29") (pintype "bidirectional"))
      (node (ref "SV2") (pin "19") (pinfunction "19_19") (pintype "passive"))
    )
    (net (code "97") (name "P30") (class "Default")
      (node (ref "IC1") (pin "30") (pinfunction "RB15_30") (pintype "bidirectional"))
      (node (ref "SV2") (pin "20") (pinfunction "20_20") (pintype "passive"))
    )
    (net (code "98") (name "P31") (class "Default")
      (node (ref "IC1") (pin "31") (pinfunction "RF4_31") (pintype "bidirectional"))
      (node (ref "SV1") (pin "1") (pinfunction "1_1") (pintype "passive"))
    )
    (net (code "99") (name "P32") (class "Default")
      (node (ref "IC1") (pin "32") (pinfunction "RF5_32") (pintype "bidirectional"))
      (node (ref "SV1") (pin "2") (pinfunction "2_2") (pintype "passive"))
    )
    (net (code "100") (name "P33") (class "Default")
      (node (ref "IC1") (pin "33") (pinfunction "RF3_33") (pintype "bidirectional"))
      (node (ref "SV1") (pin "3") (pinfunction "3_3") (pintype "passive"))
    )
    (net (code "101") (name "P34") (class "Default")
      (node (ref "IC1") (pin "34") (pinfunction "VBUS_34") (pintype "bidirectional"))
      (node (ref "SV1") (pin "4") (pinfunction "4_4") (pintype "passive"))
    )
    (net (code "102") (name "P35") (class "Default")
      (node (ref "IC1") (pin "35") (pinfunction "VUSB_35") (pintype "passive"))
      (node (ref "SV1") (pin "5") (pinfunction "5_5") (pintype "passive"))
    )
    (net (code "103") (name "P36") (class "Default")
      (node (ref "IC1") (pin "36") (pinfunction "USBDM_36") (pintype "bidirectional"))
      (node (ref "SV1") (pin "6") (pinfunction "6_6") (pintype "passive"))
    )
    (net (code "104") (name "P37") (class "Default")
      (node (ref "IC1") (pin "37") (pinfunction "USBDP_37") (pintype "bidirectional"))
      (node (ref "SV1") (pin "7") (pinfunction "7_7") (pintype "passive"))
    )
    (net (code "105") (name "P42") (class "Default")
      (node (ref "IC1") (pin "42") (pinfunction "RD8_42") (pintype "bidirectional"))
      (node (ref "SV1") (pin "10") (pinfunction "10_10") (pintype "passive"))
    )
    (net (code "106") (name "P43") (class "Default")
      (node (ref "IC1") (pin "43") (pinfunction "RD9_43") (pintype "bidirectional"))
      (node (ref "SV1") (pin "11") (pinfunction "11_11") (pintype "passive"))
    )
    (net (code "107") (name "P44") (class "Default")
      (node (ref "IC1") (pin "44") (pinfunction "RD10_44") (pintype "bidirectional"))
      (node (ref "SV1") (pin "12") (pinfunction "12_12") (pintype "passive"))
    )
    (net (code "108") (name "P45") (class "Default")
      (node (ref "IC1") (pin "45") (pinfunction "RD11_45") (pintype "bidirectional"))
      (node (ref "SV1") (pin "13") (pinfunction "13_13") (pintype "passive"))
    )
    (net (code "109") (name "P46") (class "Default")
      (node (ref "IC1") (pin "46") (pinfunction "RD0_46") (pintype "bidirectional"))
      (node (ref "SV1") (pin "14") (pinfunction "14_14") (pintype "passive"))
    )
    (net (code "110") (name "P49") (class "Default")
      (node (ref "IC1") (pin "49") (pinfunction "RD1_49") (pintype "bidirectional"))
      (node (ref "SV3") (pin "1") (pinfunction "1_1") (pintype "passive"))
    )
    (net (code "111") (name "P50") (class "Default")
      (node (ref "IC1") (pin "50") (pinfunction "RD2_50") (pintype "bidirectional"))
      (node (ref "SV3") (pin "4") (pinfunction "4_4") (pintype "passive"))
    )
    (net (code "112") (name "P51") (class "Default")
      (node (ref "IC1") (pin "51") (pinfunction "RD3_51") (pintype "bidirectional"))
      (node (ref "SV3") (pin "3") (pinfunction "3_3") (pintype "passive"))
    )
    (net (code "113") (name "P52") (class "Default")
      (node (ref "IC1") (pin "52") (pinfunction "RD4_52") (pintype "bidirectional"))
      (node (ref "SV3") (pin "6") (pinfunction "6_6") (pintype "passive"))
    )
    (net (code "114") (name "P53") (class "Default")
      (node (ref "IC1") (pin "53") (pinfunction "RD5_53") (pintype "bidirectional"))
      (node (ref "SV3") (pin "5") (pinfunction "5_5") (pintype "passive"))
    )
    (net (code "115") (name "P54") (class "Default")
      (node (ref "IC1") (pin "54") (pinfunction "RD6_54") (pintype "bidirectional"))
      (node (ref "SV3") (pin "8") (pinfunction "8_8") (pintype "passive"))
    )
    (net (code "116") (name "P55") (class "Default")
      (node (ref "IC1") (pin "55") (pinfunction "RD7_55") (pintype "bidirectional"))
      (node (ref "SV3") (pin "7") (pinfunction "7_7") (pintype "passive"))
    )
    (net (code "117") (name "P58") (class "Default")
      (node (ref "IC1") (pin "58") (pinfunction "RF0_58") (pintype "bidirectional"))
      (node (ref "SV3") (pin "10") (pinfunction "10_10") (pintype "passive"))
    )
    (net (code "118") (name "P59") (class "Default")
      (node (ref "IC1") (pin "59") (pinfunction "RF1_59") (pintype "bidirectional"))
      (node (ref "SV3") (pin "9") (pinfunction "9_9") (pintype "passive"))
    )
    (net (code "119") (name "P60") (class "Default")
      (node (ref "IC1") (pin "60") (pinfunction "RE0_60") (pintype "bidirectional"))
      (node (ref "SV3") (pin "12") (pinfunction "12_12") (pintype "passive"))
    )
    (net (code "120") (name "P61") (class "Default")
      (node (ref "IC1") (pin "61") (pinfunction "RE1_61") (pintype "bidirectional"))
      (node (ref "SV3") (pin "11") (pinfunction "11_11") (pintype "passive"))
    )
    (net (code "121") (name "P62") (class "Default")
      (node (ref "IC1") (pin "62") (pinfunction "RE2_62") (pintype "bidirectional"))
      (node (ref "SV3") (pin "14") (pinfunction "14_14") (pintype "passive"))
    )
    (net (code "122") (name "P63") (class "Default")
      (node (ref "IC1") (pin "63") (pinfunction "RE3_63") (pintype "bidirectional"))
      (node (ref "SV3") (pin "13") (pinfunction "13_13") (pintype "passive"))
    )
    (net (code "123") (name "P64") (class "Default")
      (node (ref "IC1") (pin "64") (pinfunction "RE4_64") (pintype "bidirectional"))
      (node (ref "SV3") (pin "16") (pinfunction "16_16") (pintype "passive"))
    )
    (net (code "124") (name "P201") (class "Default")
      (node (ref "IC3") (pin "34") (pinfunction "RA4_34") (pintype "bidirectional"))
      (node (ref "SV4") (pin "1") (pinfunction "1_1") (pintype "passive"))
    )
    (net (code "125") (name "P203") (class "Default")
      (node (ref "IC3") (pin "36") (pinfunction "RC3_36") (pintype "bidirectional"))
      (node (ref "SV4") (pin "3") (pinfunction "3_3") (pintype "passive"))
    )
    (net (code "126") (name "P204") (class "Default")
      (node (ref "IC3") (pin "35") (pinfunction "TDI_35") (pintype "input"))
      (node (ref "SV4") (pin "4") (pinfunction "4_4") (pintype "passive"))
    )
    (net (code "127") (name "P205") (class "Default")
      (node (ref "IC3") (pin "38") (pinfunction "RC5_38") (pintype "bidirectional"))
      (node (ref "SV4") (pin "5") (pinfunction "5_5") (pintype "passive"))
    )
    (net (code "128") (name "P206") (class "Default")
      (node (ref "IC3") (pin "37") (pinfunction "RC4_37") (pintype "bidirectional"))
      (node (ref "SV4") (pin "6") (pinfunction "6_6") (pintype "passive"))
    )
    (net (code "129") (name "P207") (class "Default")
      (node (ref "IC3") (pin "42") (pinfunction "RB6_42") (pintype "bidirectional"))
      (node (ref "SV4") (pin "7") (pinfunction "7_7") (pintype "passive"))
    )
    (net (code "130") (name "P208") (class "Default")
      (node (ref "IC3") (pin "41") (pinfunction "RB5_41") (pintype "bidirectional"))
      (node (ref "SV4") (pin "8") (pinfunction "8_8") (pintype "passive"))
    )
    (net (code "131") (name "P209") (class "Default")
      (node (ref "IC3") (pin "44") (pinfunction "RB8_44") (pintype "bidirectional"))
      (node (ref "SJ1") (pin "1") (pinfunction "1_1") (pintype "passive"))
      (node (ref "SV4") (pin "9") (pinfunction "9_9") (pintype "passive"))
    )
    (net (code "132") (name "P210") (class "Default")
      (node (ref "IC3") (pin "43") (pinfunction "RB7_43") (pintype "bidirectional"))
      (node (ref "SV4") (pin "10") (pinfunction "10_10") (pintype "passive"))
    )
    (net (code "133") (name "P211") (class "Default")
      (node (ref "IC3") (pin "2") (pinfunction "RC6_2") (pintype "bidirectional"))
      (node (ref "SV4") (pin "11") (pinfunction "11_11") (pintype "passive"))
    )
    (net (code "134") (name "P212") (class "Default")
      (node (ref "IC3") (pin "1") (pinfunction "RB9_1") (pintype "bidirectional"))
      (node (ref "SJ2") (pin "3") (pinfunction "3_3") (pintype "passive"))
      (node (ref "SV4") (pin "12") (pinfunction "12_12") (pintype "passive"))
    )
    (net (code "135") (name "P213") (class "Default")
      (node (ref "IC3") (pin "4") (pinfunction "RC8_4") (pintype "bidirectional"))
      (node (ref "SV4") (pin "13") (pinfunction "13_13") (pintype "passive"))
    )
    (net (code "136") (name "P214") (class "Default")
      (node (ref "IC3") (pin "3") (pinfunction "RC7_3") (pintype "bidirectional"))
      (node (ref "SV4") (pin "14") (pinfunction "14_14") (pintype "passive"))
    )
    (net (code "137") (name "P215") (class "Default")
      (node (ref "IC3") (pin "8") (pinfunction "RB10_8") (pintype "bidirectional"))
      (node (ref "SV4") (pin "15") (pinfunction "15_15") (pintype "passive"))
    )
    (net (code "138") (name "P216") (class "Default")
      (node (ref "IC3") (pin "5") (pinfunction "RC9_5") (pintype "bidirectional"))
      (node (ref "SV4") (pin "16") (pinfunction "16_16") (pintype "passive"))
    )
    (net (code "139") (name "P217") (class "Default")
      (node (ref "IC3") (pin "10") (pinfunction "RB12_10") (pintype "bidirectional"))
      (node (ref "SV4") (pin "17") (pinfunction "17_17") (pintype "passive"))
    )
    (net (code "140") (name "P218") (class "Default")
      (node (ref "IC3") (pin "9") (pinfunction "RB11_9") (pintype "bidirectional"))
      (node (ref "SV4") (pin "18") (pinfunction "18_18") (pintype "passive"))
    )
    (net (code "141") (name "P219") (class "Default")
      (node (ref "IC3") (pin "12") (pinfunction "TMS_12") (pintype "input"))
      (node (ref "SV4") (pin "19") (pinfunction "19_19") (pintype "passive"))
    )
    (net (code "142") (name "P220") (class "Default")
      (node (ref "IC3") (pin "11") (pinfunction "RB13_11") (pintype "bidirectional"))
      (node (ref "SV4") (pin "20") (pinfunction "20_20") (pintype "passive"))
    )
    (net (code "143") (name "P221") (class "Default")
      (node (ref "IC3") (pin "14") (pinfunction "RB14_14") (pintype "bidirectional"))
      (node (ref "SV5") (pin "1") (pinfunction "1_1") (pintype "passive"))
    )
    (net (code "144") (name "P222") (class "Default")
      (node (ref "IC3") (pin "13") (pinfunction "TCK_13") (pintype "input"))
      (node (ref "SV5") (pin "2") (pinfunction "2_2") (pintype "passive"))
    )
    (net (code "145") (name "P223") (class "Default")
      (node (ref "IC3") (pin "19") (pinfunction "RA0_19") (pintype "bidirectional"))
      (node (ref "SV5") (pin "3") (pinfunction "3_3") (pintype "passive"))
    )
    (net (code "146") (name "P224") (class "Default")
      (node (ref "IC3") (pin "15") (pinfunction "RB15_15") (pintype "bidirectional"))
      (node (ref "SV5") (pin "4") (pinfunction "4_4") (pintype "passive"))
    )
    (net (code "147") (name "P225") (class "Default")
      (node (ref "IC3") (pin "21") (pinfunction "RB0_21") (pintype "bidirectional"))
      (node (ref "SJ1") (pin "3") (pinfunction "3_3") (pintype "passive"))
      (node (ref "SV5") (pin "5") (pinfunction "5_5") (pintype "passive"))
    )
    (net (code "148") (name "P226") (class "Default")
      (node (ref "IC3") (pin "20") (pinfunction "RA1_20") (pintype "bidirectional"))
      (node (ref "SV5") (pin "6") (pinfunction "6_6") (pintype "passive"))
    )
    (net (code "149") (name "P227") (class "Default")
      (node (ref "IC3") (pin "23") (pinfunction "RB2_23") (pintype "bidirectional"))
      (node (ref "SV5") (pin "7") (pinfunction "7_7") (pintype "passive"))
    )
    (net (code "150") (name "P228") (class "Default")
      (node (ref "IC3") (pin "22") (pinfunction "RB1_22") (pintype "bidirectional"))
      (node (ref "SJ2") (pin "1") (pinfunction "1_1") (pintype "passive"))
      (node (ref "SV5") (pin "8") (pinfunction "8_8") (pintype "passive"))
    )
    (net (code "151") (name "P229") (class "Default")
      (node (ref "IC3") (pin "25") (pinfunction "RC0_25") (pintype "bidirectional"))
      (node (ref "SV5") (pin "9") (pinfunction "9_9") (pintype "passive"))
    )
    (net (code "152") (name "P230") (class "Default")
      (node (ref "IC3") (pin "24") (pinfunction "RB3_24") (pintype "bidirectional"))
      (node (ref "SV5") (pin "10") (pinfunction "10_10") (pintype "passive"))
    )
    (net (code "153") (name "P231") (class "Default")
      (node (ref "IC3") (pin "27") (pinfunction "RC2_27") (pintype "bidirectional"))
      (node (ref "SV5") (pin "11") (pinfunction "11_11") (pintype "passive"))
    )
    (net (code "154") (name "P232") (class "Default")
      (node (ref "IC3") (pin "26") (pinfunction "RC1_26") (pintype "bidirectional"))
      (node (ref "SV5") (pin "12") (pinfunction "12_12") (pintype "passive"))
    )
    (net (code "155") (name "P235") (class "Default")
      (node (ref "IC3") (pin "33") (pinfunction "RB4_33") (pintype "bidirectional"))
      (node (ref "SV5") (pin "15") (pinfunction "15_15") (pintype "passive"))
    )
    (net (code "156") (name "P236") (class "Default")
      (node (ref "IC3") (pin "32") (pinfunction "TDO_32") (pintype "output"))
      (node (ref "SV5") (pin "16") (pinfunction "16_16") (pintype "passive"))
    )
    (net (code "157") (name "P302") (class "Default")
      (node (ref "SV6") (pin "17") (pinfunction "17_17") (pintype "passive"))
      (node (ref "U$1") (pin "2") (pinfunction "PIN2_2") (pintype "input"))
    )
    (net (code "158") (name "P303") (class "Default")
      (node (ref "SV6") (pin "18") (pinfunction "18_18") (pintype "passive"))
      (node (ref "U$1") (pin "3") (pinfunction "PIN3_3") (pintype "input"))
    )
    (net (code "159") (name "P306") (class "Default")
      (node (ref "SV7") (pin "1") (pinfunction "1_1") (pintype "passive"))
      (node (ref "U$1") (pin "6") (pinfunction "PIN6_6") (pintype "input"))
    )
    (net (code "160") (name "P307") (class "Default")
      (node (ref "SV7") (pin "2") (pinfunction "2_2") (pintype "passive"))
      (node (ref "U$1") (pin "7") (pinfunction "PIN7_7") (pintype "input"))
    )
    (net (code "161") (name "P311") (class "Default")
      (node (ref "SV7") (pin "7") (pinfunction "7_7") (pintype "passive"))
      (node (ref "U$1") (pin "11") (pinfunction "PIN11_11") (pintype "input"))
    )
    (net (code "162") (name "P312") (class "Default")
      (node (ref "SV7") (pin "8") (pinfunction "8_8") (pintype "passive"))
      (node (ref "U$1") (pin "12") (pinfunction "PIN12_12") (pintype "input"))
    )
    (net (code "163") (name "P314") (class "Default")
      (node (ref "SV7") (pin "11") (pinfunction "11_11") (pintype "passive"))
      (node (ref "U$1") (pin "14") (pinfunction "PIN14_14") (pintype "input"))
    )
    (net (code "164") (name "P315") (class "Default")
      (node (ref "SV7") (pin "14") (pinfunction "14_14") (pintype "passive"))
      (node (ref "U$1") (pin "15") (pinfunction "PIN15_15") (pintype "input"))
    )
    (net (code "165") (name "P316") (class "Default")
      (node (ref "SV7") (pin "13") (pinfunction "13_13") (pintype "passive"))
      (node (ref "U$1") (pin "16") (pinfunction "PIN16_16") (pintype "input"))
    )
    (net (code "166") (name "P317") (class "Default")
      (node (ref "SV7") (pin "16") (pinfunction "16_16") (pintype "passive"))
      (node (ref "U$1") (pin "17") (pinfunction "PIN17_17") (pintype "input"))
    )
    (net (code "167") (name "P318") (class "Default")
      (node (ref "SV7") (pin "15") (pinfunction "15_15") (pintype "passive"))
      (node (ref "U$1") (pin "18") (pinfunction "PIN18_18") (pintype "input"))
    )
    (net (code "168") (name "P321") (class "Default")
      (node (ref "SV6") (pin "11") (pinfunction "11_11") (pintype "passive"))
      (node (ref "U$1") (pin "21") (pinfunction "PIN21_21") (pintype "input"))
    )
    (net (code "169") (name "P322") (class "Default")
      (node (ref "SV6") (pin "12") (pinfunction "12_12") (pintype "passive"))
      (node (ref "U$1") (pin "22") (pinfunction "PIN22_22") (pintype "input"))
    )
    (net (code "170") (name "P323") (class "Default")
      (node (ref "SV6") (pin "13") (pinfunction "13_13") (pintype "passive"))
      (node (ref "U$1") (pin "23") (pinfunction "PIN23_23") (pintype "input"))
    )
    (net (code "171") (name "P324") (class "Default")
      (node (ref "SV6") (pin "14") (pinfunction "14_14") (pintype "passive"))
      (node (ref "U$1") (pin "24") (pinfunction "PIN24_24") (pintype "input"))
    )
    (net (code "172") (name "P325") (class "Default")
      (node (ref "SV6") (pin "15") (pinfunction "15_15") (pintype "passive"))
      (node (ref "U$1") (pin "25") (pinfunction "PIN25_25") (pintype "input"))
    )
    (net (code "173") (name "P326") (class "Default")
      (node (ref "SV6") (pin "16") (pinfunction "16_16") (pintype "passive"))
      (node (ref "U$1") (pin "26") (pinfunction "PIN26_26") (pintype "input"))
    )
    (net (code "174") (name "P401") (class "Default")
      (node (ref "IC4") (pin "35") (pinfunction "RC1/SOSCI/CCP2_35") (pintype "bidirectional"))
      (node (ref "SV9") (pin "1") (pinfunction "1_1") (pintype "passive"))
    )
    (net (code "175") (name "P403") (class "Default")
      (node (ref "IC4") (pin "37") (pinfunction "RC3/AN15/SCK/SCL_37") (pintype "bidirectional"))
      (node (ref "SV9") (pin "3") (pinfunction "3_3") (pintype "passive"))
    )
    (net (code "176") (name "P404") (class "Default")
      (node (ref "IC4") (pin "36") (pinfunction "RC2/AN14/CCP1_36") (pintype "bidirectional"))
      (node (ref "SV9") (pin "4") (pinfunction "4_4") (pintype "passive"))
    )
    (net (code "177") (name "P405") (class "Default")
      (node (ref "IC4") (pin "39") (pinfunction "RD1/AN21_39") (pintype "bidirectional"))
      (node (ref "SV9") (pin "5") (pinfunction "5_5") (pintype "passive"))
    )
    (net (code "178") (name "P406") (class "Default")
      (node (ref "IC4") (pin "38") (pinfunction "RD0/AN20_38") (pintype "bidirectional"))
      (node (ref "SV9") (pin "6") (pinfunction "6_6") (pintype "passive"))
    )
    (net (code "179") (name "P407") (class "Default")
      (node (ref "IC4") (pin "41") (pinfunction "RD3/AN23_41") (pintype "bidirectional"))
      (node (ref "SV9") (pin "7") (pinfunction "7_7") (pintype "passive"))
    )
    (net (code "180") (name "P408") (class "Default")
      (node (ref "IC4") (pin "40") (pinfunction "RD2/AN22_40") (pintype "bidirectional"))
      (node (ref "SV9") (pin "8") (pinfunction "8_8") (pintype "passive"))
    )
    (net (code "181") (name "P409") (class "Default")
      (node (ref "IC4") (pin "43") (pinfunction "RC5/AN17/SDO_43") (pintype "bidirectional"))
      (node (ref "SV9") (pin "9") (pinfunction "9_9") (pintype "passive"))
    )
    (net (code "182") (name "P410") (class "Default")
      (node (ref "IC4") (pin "42") (pinfunction "RC4/AN16/SDI/SDA_42") (pintype "bidirectional"))
      (node (ref "SV9") (pin "10") (pinfunction "10_10") (pintype "passive"))
    )
    (net (code "183") (name "P411") (class "Default")
      (node (ref "IC4") (pin "1") (pinfunction "DT/RX/AN19/RC7_1") (pintype "bidirectional"))
      (node (ref "SV9") (pin "11") (pinfunction "11_11") (pintype "passive"))
    )
    (net (code "184") (name "P412") (class "Default")
      (node (ref "IC4") (pin "44") (pinfunction "RC6/AN18/TX/CK_44") (pintype "bidirectional"))
      (node (ref "SV9") (pin "12") (pinfunction "12_12") (pintype "passive"))
    )
    (net (code "185") (name "P413") (class "Default")
      (node (ref "IC4") (pin "3") (pinfunction "AN25/RD5_3") (pintype "bidirectional"))
      (node (ref "SV9") (pin "13") (pinfunction "13_13") (pintype "passive"))
    )
    (net (code "186") (name "P414") (class "Default")
      (node (ref "IC4") (pin "2") (pinfunction "AN24/RD4_2") (pintype "bidirectional"))
      (node (ref "SV9") (pin "14") (pinfunction "14_14") (pintype "passive"))
    )
    (net (code "187") (name "P415") (class "Default")
      (node (ref "IC4") (pin "5") (pinfunction "AN27/RD7_5") (pintype "bidirectional"))
      (node (ref "SV9") (pin "15") (pinfunction "15_15") (pintype "passive"))
    )
    (net (code "188") (name "P416") (class "Default")
      (node (ref "IC4") (pin "4") (pinfunction "AN26/RD6_4") (pintype "bidirectional"))
      (node (ref "SV9") (pin "16") (pinfunction "16_16") (pintype "passive"))
    )
    (net (code "189") (name "P417") (class "Default")
      (node (ref "IC4") (pin "9") (pinfunction "AN10/RB1_9") (pintype "bidirectional"))
      (node (ref "SV9") (pin "17") (pinfunction "17_17") (pintype "passive"))
    )
    (net (code "190") (name "P418") (class "Default")
      (node (ref "IC4") (pin "8") (pinfunction "INT/AN12/RB0_8") (pintype "bidirectional"))
      (node (ref "SV9") (pin "18") (pinfunction "18_18") (pintype "passive"))
    )
    (net (code "191") (name "P419") (class "Default")
      (node (ref "IC4") (pin "11") (pinfunction "CCP2/AN9/RB3_11") (pintype "bidirectional"))
      (node (ref "SV9") (pin "19") (pinfunction "19_19") (pintype "passive"))
    )
    (net (code "192") (name "P420") (class "Default")
      (node (ref "IC4") (pin "10") (pinfunction "AN8/RB2_10") (pintype "bidirectional"))
      (node (ref "SV9") (pin "20") (pinfunction "20_20") (pintype "passive"))
    )
    (net (code "193") (name "P421") (class "Default")
      (node (ref "IC4") (pin "14") (pinfunction "AN11/RB4_14") (pintype "bidirectional"))
      (node (ref "SV10") (pin "1") (pinfunction "1_1") (pintype "passive"))
    )
    (net (code "194") (name "P422") (class "Default")
      (node (ref "IC4") (pin "15") (pinfunction "T1G/AN13/RB5_15") (pintype "bidirectional"))
      (node (ref "SV10") (pin "2") (pinfunction "2_2") (pintype "passive"))
    )
    (net (code "195") (name "P425") (class "Default")
      (node (ref "IC4") (pin "19") (pinfunction "~{SS}/AN0/RA0_19") (pintype "bidirectional"))
      (node (ref "SV10") (pin "5") (pinfunction "5_5") (pintype "passive"))
    )
    (net (code "196") (name "P426") (class "Default")
      (node (ref "IC4") (pin "20") (pinfunction "AN1/RA1_20") (pintype "bidirectional"))
      (node (ref "SV10") (pin "6") (pinfunction "6_6") (pintype "passive"))
    )
    (net (code "197") (name "P427") (class "Default")
      (node (ref "IC4") (pin "21") (pinfunction "AN2/RA2_21") (pintype "bidirectional"))
      (node (ref "SV10") (pin "7") (pinfunction "7_7") (pintype "passive"))
    )
    (net (code "198") (name "P428") (class "Default")
      (node (ref "IC4") (pin "22") (pinfunction "VREF+/AN3/RA3_22") (pintype "bidirectional"))
      (node (ref "SV10") (pin "8") (pinfunction "8_8") (pintype "passive"))
    )
    (net (code "199") (name "P429") (class "Default")
      (node (ref "IC4") (pin "23") (pinfunction "RA4/TOCKI_23") (pintype "bidirectional"))
      (node (ref "SJ3") (pin "2") (pinfunction "2_2") (pintype "passive"))
      (node (ref "SV10") (pin "9") (pinfunction "9_9") (pintype "passive"))
    )
    (net (code "200") (name "P430") (class "Default")
      (node (ref "IC4") (pin "24") (pinfunction "RA5/AN4/~{SS}/VCAP_24") (pintype "bidirectional"))
      (node (ref "SV10") (pin "10") (pinfunction "10_10") (pintype "passive"))
    )
    (net (code "201") (name "P431") (class "Default")
      (node (ref "IC4") (pin "25") (pinfunction "RE0/AN5_25") (pintype "bidirectional"))
      (node (ref "SV10") (pin "11") (pinfunction "11_11") (pintype "passive"))
    )
    (net (code "202") (name "P432") (class "Default")
      (node (ref "IC4") (pin "26") (pinfunction "RE1/AN6_26") (pintype "bidirectional"))
      (node (ref "SV10") (pin "12") (pinfunction "12_12") (pintype "passive"))
    )
    (net (code "203") (name "P433") (class "Default")
      (node (ref "IC4") (pin "27") (pinfunction "RE2/AN7_27") (pintype "bidirectional"))
      (node (ref "SV10") (pin "13") (pinfunction "13_13") (pintype "passive"))
    )
    (net (code "204") (name "P436") (class "Default")
      (node (ref "IC4") (pin "32") (pinfunction "RC0/SOSCO/T1CKI_32") (pintype "bidirectional"))
      (node (ref "SV10") (pin "16") (pinfunction "16_16") (pintype "passive"))
    )
    (net (code "205") (name "P502") (class "Default")
      (node (ref "SV11") (pin "2") (pinfunction "2_2") (pintype "passive"))
    )
    (net (code "206") (name "P504") (class "Default")
      (node (ref "SV11") (pin "4") (pinfunction "4_4") (pintype "passive"))
    )
    (net (code "207") (name "P506") (class "Default")
      (node (ref "SV11") (pin "6") (pinfunction "6_6") (pintype "passive"))
    )
    (net (code "208") (name "P507") (class "Default")
      (node (ref "IC6") (pin "3") (pinfunction "3_3") (pintype "passive"))
      (node (ref "SV11") (pin "7") (pinfunction "7_7") (pintype "passive"))
    )
    (net (code "209") (name "P508") (class "Default")
      (node (ref "SV11") (pin "8") (pinfunction "8_8") (pintype "passive"))
    )
    (net (code "210") (name "P513") (class "Default")
      (node (ref "IC2") (pin "5") (pinfunction "5_5") (pintype "passive"))
      (node (ref "SV11") (pin "13") (pinfunction "13_13") (pintype "passive"))
    )
    (net (code "211") (name "P514") (class "Default")
      (node (ref "SV11") (pin "14") (pinfunction "14_14") (pintype "passive"))
    )
    (net (code "212") (name "P516") (class "Default")
      (node (ref "SV11") (pin "16") (pinfunction "16_16") (pintype "passive"))
    )
    (net (code "213") (name "P517") (class "Default")
      (node (ref "IC2") (pin "3") (pinfunction "3_3") (pintype "passive"))
      (node (ref "SV11") (pin "17") (pinfunction "17_17") (pintype "passive"))
    )
    (net (code "214") (name "P518") (class "Default")
      (node (ref "IC2") (pin "2") (pinfunction "2_2") (pintype "passive"))
      (node (ref "SV11") (pin "18") (pinfunction "18_18") (pintype "passive"))
    )
    (net (code "215") (name "P521") (class "Default")
      (node (ref "IC5") (pin "8") (pinfunction "8_8") (pintype "passive"))
      (node (ref "SV12") (pin "1") (pinfunction "1_1") (pintype "passive"))
    )
    (net (code "216") (name "P522") (class "Default")
      (node (ref "IC5") (pin "7") (pinfunction "7_7") (pintype "passive"))
      (node (ref "SV12") (pin "2") (pinfunction "2_2") (pintype "passive"))
    )
    (net (code "217") (name "P523") (class "Default")
      (node (ref "IC5") (pin "9") (pinfunction "9_9") (pintype "passive"))
      (node (ref "SV12") (pin "3") (pinfunction "3_3") (pintype "passive"))
    )
    (net (code "218") (name "P524") (class "Default")
      (node (ref "IC5") (pin "6") (pinfunction "6_6") (pintype "passive"))
      (node (ref "SV12") (pin "4") (pinfunction "4_4") (pintype "passive"))
    )
    (net (code "219") (name "P525") (class "Default")
      (node (ref "IC5") (pin "10") (pinfunction "10_10") (pintype "passive"))
      (node (ref "SV12") (pin "5") (pinfunction "5_5") (pintype "passive"))
    )
    (net (code "220") (name "P526") (class "Default")
      (node (ref "IC5") (pin "5") (pinfunction "5_5") (pintype "passive"))
      (node (ref "SV12") (pin "6") (pinfunction "6_6") (pintype "passive"))
    )
    (net (code "221") (name "P527") (class "Default")
      (node (ref "IC5") (pin "11") (pinfunction "11_11") (pintype "passive"))
      (node (ref "SV12") (pin "7") (pinfunction "7_7") (pintype "passive"))
    )
    (net (code "222") (name "P533") (class "Default")
      (node (ref "SV12") (pin "13") (pinfunction "13_13") (pintype "passive"))
    )
    (net (code "223") (name "P534") (class "Default")
      (node (ref "SV12") (pin "14") (pinfunction "14_14") (pintype "passive"))
    )
    (net (code "224") (name "P535") (class "Default")
      (node (ref "SV12") (pin "15") (pinfunction "15_15") (pintype "passive"))
    )
    (net (code "225") (name "P536") (class "Default")
      (node (ref "SV12") (pin "16") (pinfunction "16_16") (pintype "passive"))
    )
    (net (code "226") (name "P601") (class "Default")
      (node (ref "SV8") (pin "1") (pinfunction "1_1") (pintype "passive"))
      (node (ref "U$2") (pin "35") (pinfunction "35.RC14_35") (pintype "bidirectional"))
    )
    (net (code "227") (name "P602") (class "Default")
      (node (ref "SV8") (pin "2") (pinfunction "2_2") (pintype "passive"))
      (node (ref "U$2") (pin "34") (pinfunction "34.RC13_34") (pintype "bidirectional"))
    )
    (net (code "228") (name "P603") (class "Default")
      (node (ref "SV8") (pin "3") (pinfunction "3_3") (pintype "passive"))
      (node (ref "U$2") (pin "37") (pinfunction "37.RD1_37") (pintype "bidirectional"))
    )
    (net (code "229") (name "P604") (class "Default")
      (node (ref "SV8") (pin "4") (pinfunction "4_4") (pintype "passive"))
      (node (ref "U$2") (pin "36") (pinfunction "36.RE8_36") (pintype "bidirectional"))
    )
    (net (code "230") (name "P605") (class "Default")
      (node (ref "SV8") (pin "5") (pinfunction "5_5") (pintype "passive"))
      (node (ref "U$2") (pin "41") (pinfunction "41.RD2_41") (pintype "bidirectional"))
    )
    (net (code "231") (name "P606") (class "Default")
      (node (ref "SV8") (pin "6") (pinfunction "6_6") (pintype "passive"))
      (node (ref "U$2") (pin "38") (pinfunction "38.RD3_38") (pintype "bidirectional"))
    )
    (net (code "232") (name "P607") (class "Default")
      (node (ref "SV8") (pin "7") (pinfunction "7_7") (pintype "passive"))
      (node (ref "U$2") (pin "43") (pinfunction "43.RF6_43") (pintype "bidirectional"))
    )
    (net (code "233") (name "P608") (class "Default")
      (node (ref "SV8") (pin "8") (pinfunction "8_8") (pintype "passive"))
      (node (ref "U$2") (pin "42") (pinfunction "42.RD0_42") (pintype "bidirectional"))
    )
    (net (code "234") (name "P611") (class "Default")
      (node (ref "SV8") (pin "11") (pinfunction "11_11") (pintype "passive"))
      (node (ref "U$2") (pin "3") (pinfunction "03.RF4_3") (pintype "bidirectional"))
    )
    (net (code "235") (name "P612") (class "Default")
      (node (ref "SV8") (pin "12") (pinfunction "12_12") (pintype "passive"))
      (node (ref "U$2") (pin "2") (pinfunction "02.RF5_2") (pintype "bidirectional"))
    )
    (net (code "236") (name "P613") (class "Default")
      (node (ref "SV8") (pin "13") (pinfunction "13_13") (pintype "passive"))
      (node (ref "U$2") (pin "5") (pinfunction "05.RF0_5") (pintype "bidirectional"))
    )
    (net (code "237") (name "P614") (class "Default")
      (node (ref "SV8") (pin "14") (pinfunction "14_14") (pintype "passive"))
      (node (ref "U$2") (pin "4") (pinfunction "04.RF1_4") (pintype "bidirectional"))
    )
    (net (code "238") (name "P616") (class "Default")
      (node (ref "SV8") (pin "16") (pinfunction "16_16") (pintype "passive"))
      (node (ref "U$2") (pin "9") (pinfunction "09.RE5_9") (pintype "bidirectional"))
    )
    (net (code "239") (name "P617") (class "Default")
      (node (ref "SV8") (pin "17") (pinfunction "17_17") (pintype "passive"))
      (node (ref "U$2") (pin "10") (pinfunction "10.RE4_10") (pintype "bidirectional"))
    )
    (net (code "240") (name "P618") (class "Default")
      (node (ref "SV8") (pin "18") (pinfunction "18_18") (pintype "passive"))
      (node (ref "U$2") (pin "11") (pinfunction "11.RE3_11") (pintype "bidirectional"))
    )
    (net (code "241") (name "P619") (class "Default")
      (node (ref "SV8") (pin "19") (pinfunction "19_19") (pintype "passive"))
      (node (ref "U$2") (pin "12") (pinfunction "12.RE2_12") (pintype "bidirectional"))
    )
    (net (code "242") (name "P620") (class "Default")
      (node (ref "SV8") (pin "20") (pinfunction "20_20") (pintype "passive"))
      (node (ref "U$2") (pin "13") (pinfunction "13.NC_13") (pintype "bidirectional"))
    )
    (net (code "243") (name "P621") (class "Default")
      (node (ref "SV13") (pin "1") (pinfunction "1_1") (pintype "passive"))
      (node (ref "U$2") (pin "14") (pinfunction "14.RE1_14") (pintype "bidirectional"))
    )
    (net (code "244") (name "P622") (class "Default")
      (node (ref "SV13") (pin "2") (pinfunction "2_2") (pintype "passive"))
      (node (ref "U$2") (pin "15") (pinfunction "15.RE0_15") (pintype "bidirectional"))
    )
    (net (code "245") (name "P625") (class "Default")
      (node (ref "SV13") (pin "5") (pinfunction "5_5") (pintype "passive"))
      (node (ref "U$2") (pin "19") (pinfunction "19.RB0_19") (pintype "bidirectional"))
    )
    (net (code "246") (name "P627") (class "Default")
      (node (ref "SV13") (pin "7") (pinfunction "7_7") (pintype "passive"))
      (node (ref "U$2") (pin "21") (pinfunction "21.RB2_21") (pintype "bidirectional"))
    )
    (net (code "247") (name "P628") (class "Default")
      (node (ref "SV13") (pin "8") (pinfunction "8_8") (pintype "passive"))
      (node (ref "U$2") (pin "20") (pinfunction "20.RB1_20") (pintype "bidirectional"))
    )
    (net (code "248") (name "P629") (class "Default")
      (node (ref "SV13") (pin "9") (pinfunction "9_9") (pintype "passive"))
      (node (ref "U$2") (pin "23") (pinfunction "23.RB4_23") (pintype "bidirectional"))
    )
    (net (code "249") (name "P630") (class "Default")
      (node (ref "SV13") (pin "10") (pinfunction "10_10") (pintype "passive"))
      (node (ref "U$2") (pin "22") (pinfunction "22.RB3_22") (pintype "bidirectional"))
    )
    (net (code "250") (name "P631") (class "Default")
      (node (ref "SV13") (pin "11") (pinfunction "11_11") (pintype "passive"))
      (node (ref "U$2") (pin "25") (pinfunction "25.RB6_25") (pintype "bidirectional"))
    )
    (net (code "251") (name "P632") (class "Default")
      (node (ref "SV13") (pin "12") (pinfunction "12_12") (pintype "passive"))
      (node (ref "U$2") (pin "24") (pinfunction "24.RB5_24") (pintype "bidirectional"))
    )
    (net (code "252") (name "P633") (class "Default")
      (node (ref "SV13") (pin "13") (pinfunction "13_13") (pintype "passive"))
      (node (ref "U$2") (pin "27") (pinfunction "27.RB8_27") (pintype "bidirectional"))
    )
    (net (code "253") (name "P634") (class "Default")
      (node (ref "SV13") (pin "14") (pinfunction "14_14") (pintype "passive"))
      (node (ref "U$2") (pin "26") (pinfunction "26.RB7_26") (pintype "bidirectional"))
    )
    (net (code "254") (name "P700") (class "Default")
      (node (ref "IC7") (pin "1") (pinfunction "(T0)PB0_1") (pintype "bidirectional"))
      (node (ref "SV15") (pin "14") (pinfunction "14_14") (pintype "passive"))
    )
    (net (code "255") (name "P701") (class "Default")
      (node (ref "IC7") (pin "2") (pinfunction "(T1)PB1_2") (pintype "bidirectional"))
      (node (ref "SV15") (pin "12") (pinfunction "12_12") (pintype "passive"))
    )
    (net (code "256") (name "P702") (class "Default")
      (node (ref "IC7") (pin "3") (pinfunction "(AIN0)PB2_3") (pintype "bidirectional"))
      (node (ref "SV15") (pin "10") (pinfunction "10_10") (pintype "passive"))
    )
    (net (code "257") (name "P703") (class "Default")
      (node (ref "IC7") (pin "4") (pinfunction "(AIN1)PB3_4") (pintype "bidirectional"))
      (node (ref "SV15") (pin "8") (pinfunction "8_8") (pintype "passive"))
    )
    (net (code "258") (name "P704") (class "Default")
      (node (ref "IC7") (pin "5") (pinfunction "(SS)PB4_5") (pintype "bidirectional"))
      (node (ref "SV15") (pin "6") (pinfunction "6_6") (pintype "passive"))
    )
    (net (code "259") (name "P705") (class "Default")
      (node (ref "IC7") (pin "6") (pinfunction "(MOSI)PB5_6") (pintype "bidirectional"))
      (node (ref "JP8") (pin "4") (pinfunction "4_4") (pintype "passive"))
      (node (ref "SV15") (pin "4") (pinfunction "4_4") (pintype "passive"))
    )
    (net (code "260") (name "P706") (class "Default")
      (node (ref "IC7") (pin "7") (pinfunction "(MISO)PB6_7") (pintype "bidirectional"))
      (node (ref "JP8") (pin "1") (pinfunction "1_1") (pintype "passive"))
      (node (ref "SV15") (pin "2") (pinfunction "2_2") (pintype "passive"))
    )
    (net (code "261") (name "P707") (class "Default")
      (node (ref "IC7") (pin "8") (pinfunction "(SCK)PB7_8") (pintype "bidirectional"))
      (node (ref "JP8") (pin "3") (pinfunction "3_3") (pintype "passive"))
      (node (ref "SV14") (pin "20") (pinfunction "20_20") (pintype "passive"))
    )
    (net (code "262") (name "P708") (class "Default")
      (node (ref "IC7") (pin "10") (pinfunction "(RXD)PD0_10") (pintype "bidirectional"))
      (node (ref "SV14") (pin "16") (pinfunction "16_16") (pintype "passive"))
    )
    (net (code "263") (name "P709") (class "Default")
      (node (ref "IC7") (pin "11") (pinfunction "(TXD)PD1_11") (pintype "bidirectional"))
      (node (ref "SV14") (pin "14") (pinfunction "14_14") (pintype "passive"))
    )
    (net (code "264") (name "P710") (class "Default")
      (node (ref "IC7") (pin "12") (pinfunction "(INT0)PD2_12") (pintype "bidirectional"))
      (node (ref "SV14") (pin "12") (pinfunction "12_12") (pintype "passive"))
    )
    (net (code "265") (name "P711") (class "Default")
      (node (ref "IC7") (pin "13") (pinfunction "(INT1)PD3_13") (pintype "bidirectional"))
      (node (ref "SV14") (pin "10") (pinfunction "10_10") (pintype "passive"))
    )
    (net (code "266") (name "P712") (class "Default")
      (node (ref "IC7") (pin "14") (pinfunction "PD4_14") (pintype "bidirectional"))
      (node (ref "SV14") (pin "8") (pinfunction "8_8") (pintype "passive"))
    )
    (net (code "267") (name "P713") (class "Default")
      (node (ref "IC7") (pin "15") (pinfunction "(OC1A)PD5_15") (pintype "bidirectional"))
      (node (ref "SV14") (pin "6") (pinfunction "6_6") (pintype "passive"))
    )
    (net (code "268") (name "P714") (class "Default")
      (node (ref "IC7") (pin "16") (pinfunction "(WR)PD6_16") (pintype "bidirectional"))
      (node (ref "SV14") (pin "4") (pinfunction "4_4") (pintype "passive"))
    )
    (net (code "269") (name "P715") (class "Default")
      (node (ref "IC7") (pin "17") (pinfunction "(RD)PD7_17") (pintype "bidirectional"))
      (node (ref "SV14") (pin "2") (pinfunction "2_2") (pintype "passive"))
    )
    (net (code "270") (name "P716") (class "Default")
      (node (ref "IC7") (pin "21") (pinfunction "(A8)PC0_21") (pintype "bidirectional"))
      (node (ref "SV14") (pin "1") (pinfunction "1_1") (pintype "passive"))
    )
    (net (code "271") (name "P717") (class "Default")
      (node (ref "IC7") (pin "22") (pinfunction "(A9)PC1_22") (pintype "bidirectional"))
      (node (ref "SV14") (pin "3") (pinfunction "3_3") (pintype "passive"))
    )
    (net (code "272") (name "P718") (class "Default")
      (node (ref "IC7") (pin "23") (pinfunction "(A10)PC2_23") (pintype "bidirectional"))
      (node (ref "SV14") (pin "5") (pinfunction "5_5") (pintype "passive"))
    )
    (net (code "273") (name "P719") (class "Default")
      (node (ref "IC7") (pin "24") (pinfunction "(A11)PC3_24") (pintype "bidirectional"))
      (node (ref "SV14") (pin "7") (pinfunction "7_7") (pintype "passive"))
    )
    (net (code "274") (name "P720") (class "Default")
      (node (ref "IC7") (pin "25") (pinfunction "(A12)PC4_25") (pintype "bidirectional"))
      (node (ref "SV14") (pin "9") (pinfunction "9_9") (pintype "passive"))
    )
    (net (code "275") (name "P721") (class "Default")
      (node (ref "IC7") (pin "26") (pinfunction "(A13)PC5_26") (pintype "bidirectional"))
      (node (ref "SV14") (pin "11") (pinfunction "11_11") (pintype "passive"))
    )
    (net (code "276") (name "P722") (class "Default")
      (node (ref "IC7") (pin "27") (pinfunction "(A14)PC6_27") (pintype "bidirectional"))
      (node (ref "SV14") (pin "13") (pinfunction "13_13") (pintype "passive"))
    )
    (net (code "277") (name "P723") (class "Default")
      (node (ref "IC7") (pin "28") (pinfunction "(A15)PC7_28") (pintype "bidirectional"))
      (node (ref "SV14") (pin "15") (pinfunction "15_15") (pintype "passive"))
    )
    (net (code "278") (name "P724") (class "Default")
      (node (ref "IC7") (pin "32") (pinfunction "(AD7)PA7_32") (pintype "bidirectional"))
      (node (ref "SV15") (pin "3") (pinfunction "3_3") (pintype "passive"))
    )
    (net (code "279") (name "P725") (class "Default")
      (node (ref "IC7") (pin "33") (pinfunction "(AD6)PA6_33") (pintype "bidirectional"))
      (node (ref "SV15") (pin "5") (pinfunction "5_5") (pintype "passive"))
    )
    (net (code "280") (name "P726") (class "Default")
      (node (ref "IC7") (pin "34") (pinfunction "(AD5)PA5_34") (pintype "bidirectional"))
      (node (ref "SV15") (pin "7") (pinfunction "7_7") (pintype "passive"))
    )
    (net (code "281") (name "P727") (class "Default")
      (node (ref "IC7") (pin "35") (pinfunction "(AD4)PA4_35") (pintype "bidirectional"))
      (node (ref "SV15") (pin "9") (pinfunction "9_9") (pintype "passive"))
    )
    (net (code "282") (name "P728") (class "Default")
      (node (ref "IC7") (pin "36") (pinfunction "(AD3)PA3_36") (pintype "bidirectional"))
      (node (ref "SV15") (pin "11") (pinfunction "11_11") (pintype "passive"))
    )
    (net (code "283") (name "P729") (class "Default")
      (node (ref "IC7") (pin "37") (pinfunction "(AD2)PA2_37") (pintype "bidirectional"))
      (node (ref "SV15") (pin "13") (pinfunction "13_13") (pintype "passive"))
    )
    (net (code "284") (name "P730") (class "Default")
      (node (ref "IC7") (pin "38") (pinfunction "(AD1)PA1_38") (pintype "bidirectional"))
      (node (ref "SV15") (pin "15") (pinfunction "15_15") (pintype "passive"))
    )
    (net (code "285") (name "P731") (class "Default")
      (node (ref "IC7") (pin "39") (pinfunction "(AD0)PA0_39") (pintype "bidirectional"))
      (node (ref "SV15") (pin "16") (pinfunction "16_16") (pintype "passive"))
    )
    (net (code "286") (name "P732") (class "Default")
      (node (ref "IC7") (pin "31") (pinfunction "ICP_31") (pintype "bidirectional"))
      (node (ref "SV15") (pin "1") (pinfunction "1_1") (pintype "passive"))
    )
    (net (code "287") (name "P733") (class "Default")
      (node (ref "IC7") (pin "30") (pinfunction "ALE_30") (pintype "bidirectional"))
      (node (ref "SV14") (pin "19") (pinfunction "19_19") (pintype "passive"))
    )
    (net (code "288") (name "P734") (class "Default")
      (node (ref "IC7") (pin "29") (pinfunction "OC1B_29") (pintype "bidirectional"))
      (node (ref "SV14") (pin "17") (pinfunction "17_17") (pintype "passive"))
    )
    (net (code "289") (name "P800") (class "Default")
      (node (ref "IC8") (pin "1") (pinfunction "(T0)PB0_1") (pintype "bidirectional"))
      (node (ref "SV17") (pin "15") (pinfunction "15_15") (pintype "passive"))
    )
    (net (code "290") (name "P801") (class "Default")
      (node (ref "IC8") (pin "2") (pinfunction "(T1)PB1_2") (pintype "bidirectional"))
      (node (ref "SV17") (pin "13") (pinfunction "13_13") (pintype "passive"))
    )
    (net (code "291") (name "P802") (class "Default")
      (node (ref "IC8") (pin "3") (pinfunction "(AIN0)PB2_3") (pintype "bidirectional"))
      (node (ref "SV17") (pin "11") (pinfunction "11_11") (pintype "passive"))
    )
    (net (code "292") (name "P803") (class "Default")
      (node (ref "IC8") (pin "4") (pinfunction "(AIN1)PB3_4") (pintype "bidirectional"))
      (node (ref "SV17") (pin "9") (pinfunction "9_9") (pintype "passive"))
    )
    (net (code "293") (name "P804") (class "Default")
      (node (ref "IC8") (pin "5") (pinfunction "(SS)PB4_5") (pintype "bidirectional"))
      (node (ref "SV17") (pin "7") (pinfunction "7_7") (pintype "passive"))
    )
    (net (code "294") (name "P805") (class "Default")
      (node (ref "IC8") (pin "6") (pinfunction "(MOSI)PB5_6") (pintype "bidirectional"))
      (node (ref "JP7") (pin "4") (pinfunction "4_4") (pintype "passive"))
      (node (ref "SV17") (pin "5") (pinfunction "5_5") (pintype "passive"))
    )
    (net (code "295") (name "P806") (class "Default")
      (node (ref "IC8") (pin "7") (pinfunction "(MISO)PB6_7") (pintype "bidirectional"))
      (node (ref "JP7") (pin "1") (pinfunction "1_1") (pintype "passive"))
      (node (ref "SV17") (pin "3") (pinfunction "3_3") (pintype "passive"))
    )
    (net (code "296") (name "P807") (class "Default")
      (node (ref "IC8") (pin "8") (pinfunction "(SCK)PB7_8") (pintype "bidirectional"))
      (node (ref "JP7") (pin "3") (pinfunction "3_3") (pintype "passive"))
      (node (ref "SV17") (pin "1") (pinfunction "1_1") (pintype "passive"))
    )
    (net (code "297") (name "P808") (class "Default")
      (node (ref "IC8") (pin "14") (pinfunction "(RXD)PD0_14") (pintype "bidirectional"))
      (node (ref "SV16") (pin "14") (pinfunction "14_14") (pintype "passive"))
    )
    (net (code "298") (name "P809") (class "Default")
      (node (ref "IC8") (pin "15") (pinfunction "(TXD)PD1_15") (pintype "bidirectional"))
      (node (ref "SV16") (pin "12") (pinfunction "12_12") (pintype "passive"))
    )
    (net (code "299") (name "P810") (class "Default")
      (node (ref "IC8") (pin "16") (pinfunction "(INT0)PD2_16") (pintype "bidirectional"))
      (node (ref "SV16") (pin "10") (pinfunction "10_10") (pintype "passive"))
    )
    (net (code "300") (name "P811") (class "Default")
      (node (ref "IC8") (pin "17") (pinfunction "(INT1)PD3_17") (pintype "bidirectional"))
      (node (ref "SV16") (pin "8") (pinfunction "8_8") (pintype "passive"))
    )
    (net (code "301") (name "P812") (class "Default")
      (node (ref "IC8") (pin "18") (pinfunction "(OC1B)PD4_18") (pintype "bidirectional"))
      (node (ref "SV16") (pin "6") (pinfunction "6_6") (pintype "passive"))
    )
    (net (code "302") (name "P813") (class "Default")
      (node (ref "IC8") (pin "19") (pinfunction "(OC1A)PD5_19") (pintype "bidirectional"))
      (node (ref "SV16") (pin "4") (pinfunction "4_4") (pintype "passive"))
    )
    (net (code "303") (name "P814") (class "Default")
      (node (ref "IC8") (pin "20") (pinfunction "(ICP)PD6_20") (pintype "bidirectional"))
      (node (ref "SV16") (pin "2") (pinfunction "2_2") (pintype "passive"))
    )
    (net (code "304") (name "P815") (class "Default")
      (node (ref "IC8") (pin "21") (pinfunction "(OC2)PD7_21") (pintype "bidirectional"))
      (node (ref "SV16") (pin "1") (pinfunction "1_1") (pintype "passive"))
    )
    (net (code "305") (name "P816") (class "Default")
      (node (ref "IC8") (pin "22") (pinfunction "PC0_22") (pintype "bidirectional"))
      (node (ref "SV16") (pin "3") (pinfunction "3_3") (pintype "passive"))
    )
    (net (code "306") (name "P817") (class "Default")
      (node (ref "IC8") (pin "23") (pinfunction "PC1_23") (pintype "bidirectional"))
      (node (ref "SV16") (pin "5") (pinfunction "5_5") (pintype "passive"))
    )
    (net (code "307") (name "P818") (class "Default")
      (node (ref "IC8") (pin "24") (pinfunction "PC2_24") (pintype "bidirectional"))
      (node (ref "SV16") (pin "7") (pinfunction "7_7") (pintype "passive"))
    )
    (net (code "308") (name "P819") (class "Default")
      (node (ref "IC8") (pin "25") (pinfunction "PC3_25") (pintype "bidirectional"))
      (node (ref "SV16") (pin "9") (pinfunction "9_9") (pintype "passive"))
    )
    (net (code "309") (name "P820") (class "Default")
      (node (ref "IC8") (pin "26") (pinfunction "PC4_26") (pintype "bidirectional"))
      (node (ref "SV16") (pin "11") (pinfunction "11_11") (pintype "passive"))
    )
    (net (code "310") (name "P821") (class "Default")
      (node (ref "IC8") (pin "27") (pinfunction "PC5_27") (pintype "bidirectional"))
      (node (ref "SV16") (pin "13") (pinfunction "13_13") (pintype "passive"))
    )
    (net (code "311") (name "P822") (class "Default")
      (node (ref "IC8") (pin "28") (pinfunction "(TOSC1)PC6_28") (pintype "bidirectional"))
      (node (ref "SV16") (pin "16") (pinfunction "16_16") (pintype "passive"))
    )
    (net (code "312") (name "P823") (class "Default")
      (node (ref "IC8") (pin "29") (pinfunction "(TOSC2)PC7_29") (pintype "bidirectional"))
      (node (ref "SV16") (pin "15") (pinfunction "15_15") (pintype "passive"))
    )
    (net (code "313") (name "P824") (class "Default")
      (node (ref "IC8") (pin "33") (pinfunction "(ADC7)PA7_33") (pintype "bidirectional"))
      (node (ref "SV17") (pin "2") (pinfunction "2_2") (pintype "passive"))
    )
    (net (code "314") (name "P825") (class "Default")
      (node (ref "IC8") (pin "34") (pinfunction "(ADC6)PA6_34") (pintype "bidirectional"))
      (node (ref "SV17") (pin "4") (pinfunction "4_4") (pintype "passive"))
    )
    (net (code "315") (name "P826") (class "Default")
      (node (ref "IC8") (pin "35") (pinfunction "(ADC5)PA5_35") (pintype "bidirectional"))
      (node (ref "SV17") (pin "6") (pinfunction "6_6") (pintype "passive"))
    )
    (net (code "316") (name "P827") (class "Default")
      (node (ref "IC8") (pin "36") (pinfunction "(ADC4)PA4_36") (pintype "bidirectional"))
      (node (ref "SV17") (pin "8") (pinfunction "8_8") (pintype "passive"))
    )
    (net (code "317") (name "P828") (class "Default")
      (node (ref "IC8") (pin "37") (pinfunction "(ADC3)PA3_37") (pintype "bidirectional"))
      (node (ref "SV17") (pin "10") (pinfunction "10_10") (pintype "passive"))
    )
    (net (code "318") (name "P829") (class "Default")
      (node (ref "IC8") (pin "38") (pinfunction "(ADC2)PA2_38") (pintype "bidirectional"))
      (node (ref "SV17") (pin "12") (pinfunction "12_12") (pintype "passive"))
    )
    (net (code "319") (name "P830") (class "Default")
      (node (ref "IC8") (pin "39") (pinfunction "(ADC1)PA1_39") (pintype "bidirectional"))
      (node (ref "SV17") (pin "14") (pinfunction "14_14") (pintype "passive"))
    )
    (net (code "320") (name "P831") (class "Default")
      (node (ref "IC8") (pin "40") (pinfunction "(ADC0)PA0_40") (pintype "bidirectional"))
      (node (ref "SV17") (pin "16") (pinfunction "16_16") (pintype "passive"))
    )
    (net (code "321") (name "P832") (class "Default")
      (node (ref "IC8") (pin "32") (pinfunction "AREF_32") (pintype "passive"))
      (node (ref "SV16") (pin "20") (pinfunction "20_20") (pintype "passive"))
    )
    (net (code "322") (name "P901") (class "Default")
      (node (ref "IC9") (pin "2") (pinfunction "RA0/AN0_2") (pintype "bidirectional"))
      (node (ref "SV19") (pin "15") (pinfunction "15_15") (pintype "passive"))
    )
    (net (code "323") (name "P902") (class "Default")
      (node (ref "IC9") (pin "3") (pinfunction "RA1/AN1_3") (pintype "bidirectional"))
      (node (ref "SV19") (pin "13") (pinfunction "13_13") (pintype "passive"))
    )
    (net (code "324") (name "P903") (class "Default")
      (node (ref "IC9") (pin "4") (pinfunction "RA2/AN2_4") (pintype "bidirectional"))
      (node (ref "SV19") (pin "11") (pinfunction "11_11") (pintype "passive"))
    )
    (net (code "325") (name "P904") (class "Default")
      (node (ref "IC9") (pin "5") (pinfunction "RA3/AN3_5") (pintype "bidirectional"))
      (node (ref "SV19") (pin "9") (pinfunction "9_9") (pintype "passive"))
    )
    (net (code "326") (name "P905") (class "Default")
      (node (ref "IC9") (pin "6") (pinfunction "RA4/T0CKI_6") (pintype "bidirectional"))
      (node (ref "SV19") (pin "7") (pinfunction "7_7") (pintype "passive"))
    )
    (net (code "327") (name "P906") (class "Default")
      (node (ref "IC9") (pin "7") (pinfunction "RA5/AN4_7") (pintype "bidirectional"))
      (node (ref "SV19") (pin "5") (pinfunction "5_5") (pintype "passive"))
    )
    (net (code "328") (name "P907") (class "Default")
      (node (ref "IC9") (pin "8") (pinfunction "RE0/~{RD/AN5}_8") (pintype "bidirectional"))
      (node (ref "SV19") (pin "3") (pinfunction "3_3") (pintype "passive"))
    )
    (net (code "329") (name "P909") (class "Default")
      (node (ref "IC9") (pin "15") (pinfunction "RC0/T1OSO_15") (pintype "bidirectional"))
      (node (ref "SV18") (pin "12") (pinfunction "12_12") (pintype "passive"))
    )
    (net (code "330") (name "P910") (class "Default")
      (node (ref "IC9") (pin "16") (pinfunction "RC1/T1OSI_16") (pintype "bidirectional"))
      (node (ref "SV18") (pin "10") (pinfunction "10_10") (pintype "passive"))
    )
    (net (code "331") (name "P911") (class "Default")
      (node (ref "IC9") (pin "17") (pinfunction "RC2/CCP1_17") (pintype "bidirectional"))
      (node (ref "SV18") (pin "8") (pinfunction "8_8") (pintype "passive"))
    )
    (net (code "332") (name "P912") (class "Default")
      (node (ref "IC9") (pin "18") (pinfunction "RC3/SCK_18") (pintype "bidirectional"))
      (node (ref "SV18") (pin "6") (pinfunction "6_6") (pintype "passive"))
    )
    (net (code "333") (name "P913") (class "Default")
      (node (ref "IC9") (pin "19") (pinfunction "RD0/PSP0_19") (pintype "bidirectional"))
      (node (ref "SV18") (pin "4") (pinfunction "4_4") (pintype "passive"))
    )
    (net (code "334") (name "P914") (class "Default")
      (node (ref "IC9") (pin "20") (pinfunction "RD1/PSP1_20") (pintype "bidirectional"))
      (node (ref "SV18") (pin "2") (pinfunction "2_2") (pintype "passive"))
    )
    (net (code "335") (name "P915") (class "Default")
      (node (ref "IC9") (pin "23") (pinfunction "SDI/RC4_23") (pintype "bidirectional"))
      (node (ref "SV18") (pin "5") (pinfunction "5_5") (pintype "passive"))
    )
    (net (code "336") (name "P916") (class "Default")
      (node (ref "IC9") (pin "24") (pinfunction "SDO/RC5_24") (pintype "bidirectional"))
      (node (ref "SV18") (pin "7") (pinfunction "7_7") (pintype "passive"))
    )
    (net (code "337") (name "P917") (class "Default")
      (node (ref "IC9") (pin "25") (pinfunction "TX/RC6_25") (pintype "bidirectional"))
      (node (ref "SV18") (pin "9") (pinfunction "9_9") (pintype "passive"))
    )
    (net (code "338") (name "P918") (class "Default")
      (node (ref "IC9") (pin "26") (pinfunction "RX/RC7_26") (pintype "bidirectional"))
      (node (ref "SV18") (pin "11") (pinfunction "11_11") (pintype "passive"))
    )
    (net (code "339") (name "P919") (class "Default")
      (node (ref "IC9") (pin "27") (pinfunction "PSP4/RD4_27") (pintype "bidirectional"))
      (node (ref "SV18") (pin "13") (pinfunction "13_13") (pintype "passive"))
    )
    (net (code "340") (name "P920") (class "Default")
      (node (ref "IC9") (pin "28") (pinfunction "PSP5/RD5_28") (pintype "bidirectional"))
      (node (ref "SV18") (pin "15") (pinfunction "15_15") (pintype "passive"))
    )
    (net (code "341") (name "P921") (class "Default")
      (node (ref "IC9") (pin "29") (pinfunction "PSP6/RD6_29") (pintype "bidirectional"))
      (node (ref "SV18") (pin "17") (pinfunction "17_17") (pintype "passive"))
    )
    (net (code "342") (name "P922") (class "Default")
      (node (ref "IC9") (pin "30") (pinfunction "PSP7/RD7_30") (pintype "bidirectional"))
      (node (ref "SV18") (pin "18") (pinfunction "18_18") (pintype "passive"))
    )
    (net (code "343") (name "P924") (class "Default")
      (node (ref "IC9") (pin "33") (pinfunction "INT/RB0_33") (pintype "bidirectional"))
      (node (ref "SV18") (pin "20") (pinfunction "20_20") (pintype "passive"))
    )
    (net (code "344") (name "P925") (class "Default")
      (node (ref "IC9") (pin "34") (pinfunction "RB1_34") (pintype "bidirectional"))
      (node (ref "SV19") (pin "2") (pinfunction "2_2") (pintype "passive"))
    )
    (net (code "345") (name "P926") (class "Default")
      (node (ref "IC9") (pin "35") (pinfunction "RB2_35") (pintype "bidirectional"))
      (node (ref "SV19") (pin "4") (pinfunction "4_4") (pintype "passive"))
    )
    (net (code "346") (name "P927") (class "Default")
      (node (ref "IC9") (pin "36") (pinfunction "PGM/RB3_36") (pintype "bidirectional"))
      (node (ref "SV19") (pin "6") (pinfunction "6_6") (pintype "passive"))
    )
    (net (code "347") (name "P928") (class "Default")
      (node (ref "IC9") (pin "37") (pinfunction "RB4_37") (pintype "bidirectional"))
      (node (ref "SV19") (pin "8") (pinfunction "8_8") (pintype "passive"))
    )
    (net (code "348") (name "P929") (class "Default")
      (node (ref "IC9") (pin "38") (pinfunction "RB5_38") (pintype "bidirectional"))
      (node (ref "SV19") (pin "10") (pinfunction "10_10") (pintype "passive"))
    )
    (net (code "349") (name "P932") (class "Default")
      (node (ref "IC9") (pin "10") (pinfunction "RE2/~{CS/AN7}_10") (pintype "bidirectional"))
      (node (ref "SV18") (pin "19") (pinfunction "19_19") (pintype "passive"))
    )
    (net (code "350") (name "P933") (class "Default")
      (node (ref "IC9") (pin "21") (pinfunction "RD2/PSP2_21") (pintype "bidirectional"))
      (node (ref "SV18") (pin "1") (pinfunction "1_1") (pintype "passive"))
    )
    (net (code "351") (name "P934") (class "Default")
      (node (ref "IC9") (pin "22") (pinfunction "RD3/PSP3_22") (pintype "bidirectional"))
      (node (ref "SV18") (pin "3") (pinfunction "3_3") (pintype "passive"))
    )
    (net (code "352") (name "P935") (class "Default")
      (node (ref "IC9") (pin "9") (pinfunction "RE1/~{WR/AN6}_9") (pintype "bidirectional"))
      (node (ref "SV19") (pin "1") (pinfunction "1_1") (pintype "passive"))
    )
    (net (code "353") (name "P1000") (class "Default")
      (node (ref "SV20") (pin "1") (pinfunction "1_1") (pintype "passive"))
      (node (ref "U$3") (pin "1") (pinfunction "P0_1") (pintype "bidirectional"))
    )
    (net (code "354") (name "P1001") (class "Default")
      (node (ref "SV20") (pin "3") (pinfunction "3_3") (pintype "passive"))
      (node (ref "U$3") (pin "2") (pinfunction "P1_2") (pintype "bidirectional"))
    )
    (net (code "355") (name "P1002") (class "Default")
      (node (ref "SV20") (pin "5") (pinfunction "5_5") (pintype "passive"))
      (node (ref "U$3") (pin "3") (pinfunction "P2_3") (pintype "bidirectional"))
    )
    (net (code "356") (name "P1003") (class "Default")
      (node (ref "SV20") (pin "7") (pinfunction "7_7") (pintype "passive"))
      (node (ref "U$3") (pin "4") (pinfunction "P3_4") (pintype "bidirectional"))
    )
    (net (code "357") (name "P1004") (class "Default")
      (node (ref "SV20") (pin "9") (pinfunction "9_9") (pintype "passive"))
      (node (ref "U$3") (pin "5") (pinfunction "P4_5") (pintype "bidirectional"))
    )
    (net (code "358") (name "P1005") (class "Default")
      (node (ref "SV20") (pin "11") (pinfunction "11_11") (pintype "passive"))
      (node (ref "U$3") (pin "6") (pinfunction "P5_6") (pintype "bidirectional"))
    )
    (net (code "359") (name "P1006") (class "Default")
      (node (ref "SV20") (pin "13") (pinfunction "13_13") (pintype "passive"))
      (node (ref "U$3") (pin "7") (pinfunction "P6_7") (pintype "bidirectional"))
    )
    (net (code "360") (name "P1007") (class "Default")
      (node (ref "SV20") (pin "15") (pinfunction "15_15") (pintype "passive"))
      (node (ref "U$3") (pin "8") (pinfunction "P7_8") (pintype "bidirectional"))
    )
    (net (code "361") (name "P1008") (class "Default")
      (node (ref "SV21") (pin "1") (pinfunction "1_1") (pintype "passive"))
      (node (ref "U$3") (pin "13") (pinfunction "P8_13") (pintype "bidirectional"))
    )
    (net (code "362") (name "P1009") (class "Default")
      (node (ref "SV21") (pin "3") (pinfunction "3_3") (pintype "passive"))
      (node (ref "U$3") (pin "14") (pinfunction "P9_14") (pintype "bidirectional"))
    )
    (net (code "363") (name "P1010") (class "Default")
      (node (ref "SV21") (pin "5") (pinfunction "5_5") (pintype "passive"))
      (node (ref "U$3") (pin "15") (pinfunction "P10_15") (pintype "bidirectional"))
    )
    (net (code "364") (name "P1011") (class "Default")
      (node (ref "SV21") (pin "7") (pinfunction "7_7") (pintype "passive"))
      (node (ref "U$3") (pin "16") (pinfunction "P11_16") (pintype "bidirectional"))
    )
    (net (code "365") (name "P1012") (class "Default")
      (node (ref "SV21") (pin "9") (pinfunction "9_9") (pintype "passive"))
      (node (ref "U$3") (pin "17") (pinfunction "P12_17") (pintype "bidirectional"))
    )
    (net (code "366") (name "P1013") (class "Default")
      (node (ref "SV21") (pin "11") (pinfunction "11_11") (pintype "passive"))
      (node (ref "U$3") (pin "18") (pinfunction "P13_18") (pintype "bidirectional"))
    )
    (net (code "367") (name "P1014") (class "Default")
      (node (ref "SV21") (pin "13") (pinfunction "13_13") (pintype "passive"))
      (node (ref "U$3") (pin "19") (pinfunction "P14_19") (pintype "bidirectional"))
    )
    (net (code "368") (name "P1015") (class "Default")
      (node (ref "SV21") (pin "15") (pinfunction "15_15") (pintype "passive"))
      (node (ref "U$3") (pin "20") (pinfunction "P15_20") (pintype "bidirectional"))
    )
    (net (code "369") (name "P1016") (class "Default")
      (node (ref "SV21") (pin "16") (pinfunction "16_16") (pintype "passive"))
      (node (ref "U$3") (pin "21") (pinfunction "P16_21") (pintype "bidirectional"))
    )
    (net (code "370") (name "P1017") (class "Default")
      (node (ref "SV21") (pin "14") (pinfunction "14_14") (pintype "passive"))
      (node (ref "U$3") (pin "22") (pinfunction "P17_22") (pintype "bidirectional"))
    )
    (net (code "371") (name "P1018") (class "Default")
      (node (ref "SV21") (pin "12") (pinfunction "12_12") (pintype "passive"))
      (node (ref "U$3") (pin "23") (pinfunction "P18_23") (pintype "bidirectional"))
    )
    (net (code "372") (name "P1019") (class "Default")
      (node (ref "SV21") (pin "10") (pinfunction "10_10") (pintype "passive"))
      (node (ref "U$3") (pin "24") (pinfunction "P19_24") (pintype "bidirectional"))
    )
    (net (code "373") (name "P1020") (class "Default")
      (node (ref "SV21") (pin "8") (pinfunction "8_8") (pintype "passive"))
      (node (ref "U$3") (pin "25") (pinfunction "P20_25") (pintype "bidirectional"))
    )
    (net (code "374") (name "P1021") (class "Default")
      (node (ref "SV21") (pin "6") (pinfunction "6_6") (pintype "passive"))
      (node (ref "U$3") (pin "26") (pinfunction "P21_26") (pintype "bidirectional"))
    )
    (net (code "375") (name "P1022") (class "Default")
      (node (ref "SV21") (pin "4") (pinfunction "4_4") (pintype "passive"))
      (node (ref "U$3") (pin "27") (pinfunction "P22_27") (pintype "bidirectional"))
    )
    (net (code "376") (name "P1023") (class "Default")
      (node (ref "SV21") (pin "2") (pinfunction "2_2") (pintype "passive"))
      (node (ref "U$3") (pin "28") (pinfunction "P23_28") (pintype "bidirectional"))
    )
    (net (code "377") (name "P1024") (class "Default")
      (node (ref "SV20") (pin "16") (pinfunction "16_16") (pintype "passive"))
      (node (ref "U$3") (pin "33") (pinfunction "P24_33") (pintype "bidirectional"))
    )
    (net (code "378") (name "P1025") (class "Default")
      (node (ref "SV20") (pin "14") (pinfunction "14_14") (pintype "passive"))
      (node (ref "U$3") (pin "34") (pinfunction "P25_34") (pintype "bidirectional"))
    )
    (net (code "379") (name "P1026") (class "Default")
      (node (ref "SV20") (pin "12") (pinfunction "12_12") (pintype "passive"))
      (node (ref "U$3") (pin "35") (pinfunction "P26_35") (pintype "bidirectional"))
    )
    (net (code "380") (name "P1027") (class "Default")
      (node (ref "SV20") (pin "10") (pinfunction "10_10") (pintype "passive"))
      (node (ref "U$3") (pin "36") (pinfunction "P27_36") (pintype "bidirectional"))
    )
    (net (code "381") (name "P1104") (class "Default")
      (node (ref "IC11") (pin "26") (pinfunction "KBI1/PGM/RB5_26") (pintype "bidirectional"))
      (node (ref "SV23") (pin "5") (pinfunction "5_5") (pintype "passive"))
    )
    (net (code "382") (name "P1105") (class "Default")
      (node (ref "IC11") (pin "25") (pinfunction "KBI0/AN9/RB4_25") (pintype "bidirectional"))
      (node (ref "SV23") (pin "3") (pinfunction "3_3") (pintype "passive"))
    )
    (net (code "383") (name "P1106") (class "Default")
      (node (ref "IC11") (pin "24") (pinfunction "CANRX/RB3_24") (pintype "bidirectional"))
      (node (ref "SV23") (pin "1") (pinfunction "1_1") (pintype "passive"))
    )
    (net (code "384") (name "P1107") (class "Default")
      (node (ref "IC11") (pin "23") (pinfunction "INT2/CANTX/RB2_23") (pintype "bidirectional"))
      (node (ref "SV22") (pin "19") (pinfunction "19_19") (pintype "passive"))
    )
    (net (code "385") (name "P1112") (class "Default")
      (node (ref "IC11") (pin "11") (pinfunction "RC0/T1OSO/T13CKI_11") (pintype "bidirectional"))
      (node (ref "SV22") (pin "6") (pinfunction "6_6") (pintype "passive"))
    )
    (net (code "386") (name "P1113") (class "Default")
      (node (ref "IC11") (pin "12") (pinfunction "RC1/T1OSI_12") (pintype "bidirectional"))
      (node (ref "SV22") (pin "4") (pinfunction "4_4") (pintype "passive"))
    )
    (net (code "387") (name "P1114") (class "Default")
      (node (ref "IC11") (pin "13") (pinfunction "RC2/CCP1_13") (pintype "bidirectional"))
      (node (ref "SV22") (pin "2") (pinfunction "2_2") (pintype "passive"))
    )
    (net (code "388") (name "P1115") (class "Default")
      (node (ref "IC11") (pin "16") (pinfunction "RC5/SDO_16") (pintype "bidirectional"))
      (node (ref "SV22") (pin "5") (pinfunction "5_5") (pintype "passive"))
    )
    (net (code "389") (name "P1116") (class "Default")
      (node (ref "IC11") (pin "17") (pinfunction "RC6/TX/CK_17") (pintype "bidirectional"))
      (node (ref "SV22") (pin "7") (pinfunction "7_7") (pintype "passive"))
    )
    (net (code "390") (name "P1117") (class "Default")
      (node (ref "IC11") (pin "18") (pinfunction "RC7/RX/DT_18") (pintype "bidirectional"))
      (node (ref "SV22") (pin "9") (pinfunction "9_9") (pintype "passive"))
    )
    (net (code "391") (name "P1126") (class "Default")
      (node (ref "IC11") (pin "7") (pinfunction "RA5/AN4/~{SS/HLVDIN}_7") (pintype "bidirectional"))
      (node (ref "SV22") (pin "20") (pinfunction "20_20") (pintype "passive"))
    )
    (net (code "392") (name "P1127") (class "Default")
      (node (ref "IC11") (pin "6") (pinfunction "RA4/T0CKI_6") (pintype "bidirectional"))
      (node (ref "SV23") (pin "2") (pinfunction "2_2") (pintype "passive"))
    )
    (net (code "393") (name "P1128") (class "Default")
      (node (ref "IC11") (pin "5") (pinfunction "RA3/AN3/VREF+_5") (pintype "bidirectional"))
      (node (ref "SV23") (pin "4") (pinfunction "4_4") (pintype "passive"))
    )
    (net (code "394") (name "P1129") (class "Default")
      (node (ref "IC11") (pin "4") (pinfunction "RA2/AN2/VREF-_4") (pintype "bidirectional"))
      (node (ref "SV23") (pin "6") (pinfunction "6_6") (pintype "passive"))
    )
    (net (code "395") (name "P1130") (class "Default")
      (node (ref "IC11") (pin "3") (pinfunction "RA1/AN1_3") (pintype "bidirectional"))
      (node (ref "SV23") (pin "8") (pinfunction "8_8") (pintype "passive"))
    )
    (net (code "396") (name "P1131") (class "Default")
      (node (ref "IC11") (pin "2") (pinfunction "RA0/AN0_2") (pintype "bidirectional"))
      (node (ref "SV23") (pin "10") (pinfunction "10_10") (pintype "passive"))
    )
    (net (code "397") (name "P1132") (class "Default")
      (node (ref "IC11") (pin "21") (pinfunction "INT0/AN10/RB0_21") (pintype "bidirectional"))
      (node (ref "SV22") (pin "15") (pinfunction "15_15") (pintype "passive"))
    )
    (net (code "398") (name "P1133") (class "Default")
      (node (ref "IC11") (pin "14") (pinfunction "RC3/SCK/SCL_14") (pintype "bidirectional"))
      (node (ref "SV22") (pin "1") (pinfunction "1_1") (pintype "passive"))
    )
    (net (code "399") (name "P1134") (class "Default")
      (node (ref "IC11") (pin "15") (pinfunction "RC4/SDI/SDA_15") (pintype "bidirectional"))
      (node (ref "SV22") (pin "3") (pinfunction "3_3") (pintype "passive"))
    )
    (net (code "400") (name "P1135") (class "Default")
      (node (ref "IC11") (pin "22") (pinfunction "INT1/AN8/RB1_22") (pintype "bidirectional"))
      (node (ref "SV22") (pin "17") (pinfunction "17_17") (pintype "passive"))
    )
    (net (code "401") (name "PGC") (class "Default")
      (node (ref "IC1") (pin "17") (pinfunction "RB6_17") (pintype "bidirectional"))
      (node (ref "JP4") (pin "5") (pinfunction "5_5") (pintype "passive"))
      (node (ref "SV2") (pin "11") (pinfunction "11_11") (pintype "passive"))
    )
    (net (code "402") (name "PGD") (class "Default")
      (node (ref "IC1") (pin "18") (pinfunction "RB7_18") (pintype "bidirectional"))
      (node (ref "JP4") (pin "4") (pinfunction "4_4") (pintype "passive"))
      (node (ref "SV2") (pin "12") (pinfunction "12_12") (pintype "passive"))
    )
    (net (code "403") (name "VCAP") (class "Default")
      (node (ref "IC1") (pin "56") (pinfunction "VDDCORE_56") (pintype "power_in"))
      (node (ref "JMP1") (pin "2") (pinfunction "2_2") (pintype "passive"))
    )
    (net (code "404") (name "VCC") (class "Default")
      (node (ref "C10") (pin "1") (pinfunction "1_1") (pintype "passive"))
      (node (ref "C11") (pin "1") (pinfunction "1_1") (pintype "passive"))
      (node (ref "C12") (pin "1") (pinfunction "1_1") (pintype "passive"))
      (node (ref "C15") (pin "1") (pinfunction "1_1") (pintype "passive"))
      (node (ref "C19") (pin "1") (pinfunction "1_1") (pintype "passive"))
      (node (ref "C2") (pin "1") (pinfunction "1_1") (pintype "passive"))
      (node (ref "C20") (pin "1") (pinfunction "1_1") (pintype "passive"))
      (node (ref "C21") (pin "1") (pinfunction "1_1") (pintype "passive"))
      (node (ref "C22") (pin "1") (pinfunction "1_1") (pintype "passive"))
      (node (ref "C25") (pin "+") (pinfunction "+_+") (pintype "passive"))
      (node (ref "C27") (pin "1") (pinfunction "1_1") (pintype "passive"))
      (node (ref "C28") (pin "1") (pinfunction "1_1") (pintype "passive"))
      (node (ref "C3") (pin "1") (pinfunction "1_1") (pintype "passive"))
      (node (ref "C32") (pin "1") (pinfunction "1_1") (pintype "passive"))
      (node (ref "C35") (pin "1") (pinfunction "1_1") (pintype "passive"))
      (node (ref "C36") (pin "1") (pinfunction "1_1") (pintype "passive"))
      (node (ref "C37") (pin "1") (pinfunction "1_1") (pintype "passive"))
      (node (ref "C6") (pin "1") (pinfunction "1_1") (pintype "passive"))
      (node (ref "C7") (pin "1") (pinfunction "1_1") (pintype "passive"))
      (node (ref "C8") (pin "1") (pinfunction "1_1") (pintype "passive"))
      (node (ref "IC1") (pin "10") (pinfunction "VDD_10") (pintype "power_in"))
      (node (ref "IC1") (pin "19") (pinfunction "AVDD_19") (pintype "power_in"))
      (node (ref "IC1") (pin "26") (pinfunction "VDD_26") (pintype "power_in"))
      (node (ref "IC1") (pin "38") (pinfunction "VDD_38") (pintype "power_in"))
      (node (ref "IC2") (pin "1") (pinfunction "1_1") (pintype "passive"))
      (node (ref "IC3") (pin "17") (pinfunction "AVDD_17") (pintype "power_in"))
      (node (ref "IC3") (pin "28") (pinfunction "VDD_28") (pintype "power_in"))
      (node (ref "IC3") (pin "40") (pinfunction "VDD_40") (pintype "power_in"))
      (node (ref "IC4") (pin "28") (pinfunction "VDD_28") (pintype "power_in"))
      (node (ref "IC4") (pin "7") (pinfunction "VDD_7") (pintype "power_in"))
      (node (ref "IC5") (pin "1") (pinfunction "1_1") (pintype "passive"))
      (node (ref "IC6") (pin "2") (pinfunction "2_2") (pintype "passive"))
      (node (ref "JMP2") (pin "1") (pinfunction "1_1") (pintype "passive"))
      (node (ref "JP1") (pin "2") (pinfunction "2_2") (pintype "passive"))
      (node (ref "JP2") (pin "2") (pinfunction "2_2") (pintype "passive"))
      (node (ref "JP3") (pin "2") (pinfunction "2_2") (pintype "passive"))
      (node (ref "JP4") (pin "2") (pinfunction "2_2") (pintype "passive"))
      (node (ref "JP5") (pin "2") (pinfunction "2_2") (pintype "passive"))
      (node (ref "JP6") (pin "2") (pinfunction "2_2") (pintype "passive"))
      (node (ref "R1") (pin "2") (pinfunction "2_2") (pintype "passive"))
      (node (ref "R10") (pin "2") (pinfunction "2_2") (pintype "passive"))
      (node (ref "R11") (pin "2") (pinfunction "2_2") (pintype "passive"))
      (node (ref "R12") (pin "2") (pinfunction "2_2") (pintype "passive"))
      (node (ref "R2") (pin "2") (pinfunction "2_2") (pintype "passive"))
      (node (ref "R3") (pin "2") (pinfunction "2_2") (pintype "passive"))
      (node (ref "R4") (pin "2") (pinfunction "2_2") (pintype "passive"))
      (node (ref "R5") (pin "2") (pinfunction "2_2") (pintype "passive"))
      (node (ref "R6") (pin "2") (pinfunction "2_2") (pintype "passive"))
      (node (ref "R7") (pin "2") (pinfunction "2_2") (pintype "passive"))
      (node (ref "R8") (pin "2") (pinfunction "2_2") (pintype "passive"))
      (node (ref "R9") (pin "2") (pinfunction "2_2") (pintype "passive"))
      (node (ref "SJ3") (pin "1") (pinfunction "1_1") (pintype "passive"))
      (node (ref "SJ4") (pin "2") (pinfunction "2_2") (pintype "passive"))
      (node (ref "SV1") (pin "17") (pinfunction "17_17") (pintype "passive"))
      (node (ref "SV1") (pin "18") (pinfunction "18_18") (pintype "passive"))
      (node (ref "SV10") (pin "17") (pinfunction "17_17") (pintype "passive"))
      (node (ref "SV10") (pin "18") (pinfunction "18_18") (pintype "passive"))
      (node (ref "SV11") (pin "10") (pinfunction "10_10") (pintype "passive"))
      (node (ref "SV11") (pin "19") (pinfunction "19_19") (pintype "passive"))
      (node (ref "SV11") (pin "20") (pinfunction "20_20") (pintype "passive"))
      (node (ref "SV11") (pin "9") (pinfunction "9_9") (pintype "passive"))
      (node (ref "SV12") (pin "17") (pinfunction "17_17") (pintype "passive"))
      (node (ref "SV12") (pin "18") (pinfunction "18_18") (pintype "passive"))
      (node (ref "SV13") (pin "17") (pinfunction "17_17") (pintype "passive"))
      (node (ref "SV13") (pin "18") (pinfunction "18_18") (pintype "passive"))
      (node (ref "SV2") (pin "10") (pinfunction "10_10") (pintype "passive"))
      (node (ref "SV2") (pin "9") (pinfunction "9_9") (pintype "passive"))
      (node (ref "SV5") (pin "17") (pinfunction "17_17") (pintype "passive"))
      (node (ref "SV5") (pin "18") (pinfunction "18_18") (pintype "passive"))
      (node (ref "SV7") (pin "10") (pinfunction "10_10") (pintype "passive"))
      (node (ref "SV7") (pin "17") (pinfunction "17_17") (pintype "passive"))
      (node (ref "SV7") (pin "18") (pinfunction "18_18") (pintype "passive"))
      (node (ref "SV7") (pin "9") (pinfunction "9_9") (pintype "passive"))
      (node (ref "U$1") (pin "13") (pinfunction "PIN13_13") (pintype "input"))
      (node (ref "U$1") (pin "28") (pinfunction "PIN28_28") (pintype "input"))
      (node (ref "U$2") (pin "17") (pinfunction "17.AVDD_17") (pintype "bidirectional"))
      (node (ref "U$2") (pin "28") (pinfunction "28.VDD_28") (pintype "bidirectional"))
      (node (ref "U$2") (pin "29") (pinfunction "29.VDD_29") (pintype "bidirectional"))
      (node (ref "U$2") (pin "40") (pinfunction "40.VDD_40") (pintype "bidirectional"))
      (node (ref "U$2") (pin "7") (pinfunction "07.VDD_7") (pintype "bidirectional"))
      (node (ref "U$2") (pin "8") (pinfunction "08.VDD_8") (pintype "bidirectional"))
    )
    (net (code "405") (name "VDD") (class "Default")
      (node (ref "C38") (pin "1") (pinfunction "1_1") (pintype "passive"))
      (node (ref "C41") (pin "1") (pinfunction "1_1") (pintype "passive"))
      (node (ref "C44") (pin "1") (pinfunction "1_1") (pintype "passive"))
      (node (ref "C47") (pin "1") (pinfunction "1_1") (pintype "passive"))
      (node (ref "C48") (pin "1") (pinfunction "1_1") (pintype "passive"))
      (node (ref "C49") (pin "1") (pinfunction "1_1") (pintype "passive"))
      (node (ref "C52") (pin "1") (pinfunction "1_1") (pintype "passive"))
      (node (ref "C55") (pin "1") (pinfunction "1_1") (pintype "passive"))
      (node (ref "IC10") (pin "8") (pinfunction "VCC_8") (pintype "power_in"))
      (node (ref "IC11") (pin "20") (pinfunction "VDD_20") (pintype "power_in"))
      (node (ref "IC7") (pin "40") (pinfunction "VCC_40") (pintype "power_in"))
      (node (ref "IC8") (pin "10") (pinfunction "VCC_10") (pintype "power_in"))
      (node (ref "IC8") (pin "30") (pinfunction "AVCC_30") (pintype "power_in"))
      (node (ref "IC9") (pin "11") (pinfunction "VDD_11") (pintype "power_in"))
      (node (ref "IC9") (pin "32") (pinfunction "VDD_32") (pintype "power_in"))
      (node (ref "JP11") (pin "2") (pinfunction "2_2") (pintype "passive"))
      (node (ref "JP7") (pin "2") (pinfunction "2_2") (pintype "passive"))
      (node (ref "JP8") (pin "2") (pinfunction "2_2") (pintype "passive"))
      (node (ref "JP9") (pin "2") (pinfunction "2_2") (pintype "passive"))
      (node (ref "R13") (pin "2") (pinfunction "2_2") (pintype "passive"))
      (node (ref "R14") (pin "2") (pinfunction "2_2") (pintype "passive"))
      (node (ref "R15") (pin "2") (pinfunction "2_2") (pintype "passive"))
      (node (ref "R16") (pin "1") (pinfunction "1_1") (pintype "passive"))
      (node (ref "R17") (pin "2") (pinfunction "2_2") (pintype "passive"))
      (node (ref "R18") (pin "2") (pinfunction "2_2") (pintype "passive"))
      (node (ref "R19") (pin "1") (pinfunction "1_1") (pintype "passive"))
      (node (ref "SV15") (pin "17") (pinfunction "17_17") (pintype "passive"))
      (node (ref "SV15") (pin "18") (pinfunction "18_18") (pintype "passive"))
      (node (ref "SV16") (pin "17") (pinfunction "17_17") (pintype "passive"))
      (node (ref "SV16") (pin "18") (pinfunction "18_18") (pintype "passive"))
      (node (ref "SV17") (pin "17") (pinfunction "17_17") (pintype "passive"))
      (node (ref "SV17") (pin "18") (pinfunction "18_18") (pintype "passive"))
      (node (ref "SV19") (pin "17") (pinfunction "17_17") (pintype "passive"))
      (node (ref "SV19") (pin "18") (pinfunction "18_18") (pintype "passive"))
      (node (ref "SV20") (pin "19") (pinfunction "19_19") (pintype "passive"))
      (node (ref "SV20") (pin "20") (pinfunction "20_20") (pintype "passive"))
      (node (ref "SV21") (pin "17") (pinfunction "17_17") (pintype "passive"))
      (node (ref "SV21") (pin "18") (pinfunction "18_18") (pintype "passive"))
      (node (ref "SV22") (pin "13") (pinfunction "13_13") (pintype "passive"))
      (node (ref "SV22") (pin "14") (pinfunction "14_14") (pintype "passive"))
      (node (ref "SV23") (pin "17") (pinfunction "17_17") (pintype "passive"))
      (node (ref "SV23") (pin "18") (pinfunction "18_18") (pintype "passive"))
    )
    (net (code "406") (name "VREG") (class "Default")
      (node (ref "IC1") (pin "57") (pinfunction "VREG_57") (pintype "passive"))
      (node (ref "JMP2") (pin "2") (pinfunction "2_2") (pintype "passive"))
    )
    (net (code "407") (name "VSS") (class "Default")
      (node (ref "C1") (pin "-") (pinfunction "-_-") (pintype "passive"))
      (node (ref "C10") (pin "2") (pinfunction "2_2") (pintype "passive"))
      (node (ref "C11") (pin "2") (pinfunction "2_2") (pintype "passive"))
      (node (ref "C12") (pin "2") (pinfunction "2_2") (pintype "passive"))
      (node (ref "C13") (pin "2") (pinfunction "2_2") (pintype "passive"))
      (node (ref "C14") (pin "2") (pinfunction "2_2") (pintype "passive"))
      (node (ref "C15") (pin "2") (pinfunction "2_2") (pintype "passive"))
      (node (ref "C16") (pin "-") (pinfunction "-_-") (pintype "passive"))
      (node (ref "C17") (pin "2") (pinfunction "2_2") (pintype "passive"))
      (node (ref "C18") (pin "2") (pinfunction "2_2") (pintype "passive"))
      (node (ref "C19") (pin "2") (pinfunction "2_2") (pintype "passive"))
      (node (ref "C2") (pin "2") (pinfunction "2_2") (pintype "passive"))
      (node (ref "C20") (pin "2") (pinfunction "2_2") (pintype "passive"))
      (node (ref "C21") (pin "2") (pinfunction "2_2") (pintype "passive"))
      (node (ref "C22") (pin "2") (pinfunction "2_2") (pintype "passive"))
      (node (ref "C23") (pin "2") (pinfunction "2_2") (pintype "passive"))
      (node (ref "C24") (pin "2") (pinfunction "2_2") (pintype "passive"))
      (node (ref "C25") (pin "-") (pinfunction "-_-") (pintype "passive"))
      (node (ref "C26") (pin "2") (pinfunction "2_2") (pintype "passive"))
      (node (ref "C27") (pin "2") (pinfunction "2_2") (pintype "passive"))
      (node (ref "C28") (pin "2") (pinfunction "2_2") (pintype "passive"))
      (node (ref "C29") (pin "2") (pinfunction "2_2") (pintype "passive"))
      (node (ref "C3") (pin "2") (pinfunction "2_2") (pintype "passive"))
      (node (ref "C30") (pin "2") (pinfunction "2_2") (pintype "passive"))
      (node (ref "C31") (pin "2") (pinfunction "2_2") (pintype "passive"))
      (node (ref "C32") (pin "2") (pinfunction "2_2") (pintype "passive"))
      (node (ref "C33") (pin "2") (pinfunction "2_2") (pintype "passive"))
      (node (ref "C34") (pin "2") (pinfunction "2_2") (pintype "passive"))
      (node (ref "C35") (pin "2") (pinfunction "2_2") (pintype "passive"))
      (node (ref "C36") (pin "2") (pinfunction "2_2") (pintype "passive"))
      (node (ref "C37") (pin "2") (pinfunction "2_2") (pintype "passive"))
      (node (ref "C38") (pin "2") (pinfunction "2_2") (pintype "passive"))
      (node (ref "C39") (pin "2") (pinfunction "2_2") (pintype "passive"))
      (node (ref "C4") (pin "2") (pinfunction "2_2") (pintype "passive"))
      (node (ref "C40") (pin "2") (pinfunction "2_2") (pintype "passive"))
      (node (ref "C41") (pin "2") (pinfunction "2_2") (pintype "passive"))
      (node (ref "C42") (pin "2") (pinfunction "2_2") (pintype "passive"))
      (node (ref "C43") (pin "2") (pinfunction "2_2") (pintype "passive"))
      (node (ref "C44") (pin "2") (pinfunction "2_2") (pintype "passive"))
      (node (ref "C45") (pin "2") (pinfunction "2_2") (pintype "passive"))
      (node (ref "C46") (pin "2") (pinfunction "2_2") (pintype "passive"))
      (node (ref "C47") (pin "2") (pinfunction "2_2") (pintype "passive"))
      (node (ref "C48") (pin "2") (pinfunction "2_2") (pintype "passive"))
      (node (ref "C49") (pin "2") (pinfunction "2_2") (pintype "passive"))
      (node (ref "C5") (pin "2") (pinfunction "2_2") (pintype "passive"))
      (node (ref "C50") (pin "2") (pinfunction "2_2") (pintype "passive"))
      (node (ref "C51") (pin "2") (pinfunction "2_2") (pintype "passive"))
      (node (ref "C52") (pin "2") (pinfunction "2_2") (pintype "passive"))
      (node (ref "C53") (pin "2") (pinfunction "2_2") (pintype "passive"))
      (node (ref "C54") (pin "2") (pinfunction "2_2") (pintype "passive"))
      (node (ref "C55") (pin "2") (pinfunction "2_2") (pintype "passive"))
      (node (ref "C6") (pin "2") (pinfunction "2_2") (pintype "passive"))
      (node (ref "C7") (pin "2") (pinfunction "2_2") (pintype "passive"))
      (node (ref "C8") (pin "2") (pinfunction "2_2") (pintype "passive"))
      (node (ref "C9") (pin "-") (pinfunction "-_-") (pintype "passive"))
      (node (ref "C9B") (pin "2") (pinfunction "2_2") (pintype "passive"))
      (node (ref "IC1") (pin "20") (pinfunction "AVSS_20") (pintype "power_in"))
      (node (ref "IC1") (pin "25") (pinfunction "VSS_25") (pintype "power_in"))
      (node (ref "IC1") (pin "41") (pinfunction "VSS_41") (pintype "power_in"))
      (node (ref "IC1") (pin "9") (pinfunction "VSS_9") (pintype "power_in"))
      (node (ref "IC10") (pin "1") (pinfunction "A0_1") (pintype "bidirectional"))
      (node (ref "IC10") (pin "2") (pinfunction "A1_2") (pintype "bidirectional"))
      (node (ref "IC10") (pin "3") (pinfunction "A2_3") (pintype "bidirectional"))
      (node (ref "IC10") (pin "4") (pinfunction "GND_4") (pintype "power_in"))
      (node (ref "IC10") (pin "7") (pinfunction "VCLK_7") (pintype "input"))
      (node (ref "IC11") (pin "19") (pinfunction "VSS_19") (pintype "power_in"))
      (node (ref "IC11") (pin "8") (pinfunction "VSS_8") (pintype "power_in"))
      (node (ref "IC2") (pin "8") (pinfunction "8_8") (pintype "passive"))
      (node (ref "IC3") (pin "16") (pinfunction "AVSS_16") (pintype "power_in"))
      (node (ref "IC3") (pin "29") (pinfunction "VSS_29") (pintype "power_in"))
      (node (ref "IC3") (pin "39") (pinfunction "VSS_39") (pintype "power_in"))
      (node (ref "IC3") (pin "6") (pinfunction "DISVREG_6") (pintype "passive"))
      (node (ref "IC4") (pin "29") (pinfunction "VSS_29") (pintype "power_in"))
      (node (ref "IC4") (pin "6") (pinfunction "VSS_6") (pintype "power_in"))
      (node (ref "IC5") (pin "14") (pinfunction "14_14") (pintype "passive"))
      (node (ref "IC6") (pin "7") (pinfunction "7_7") (pintype "passive"))
      (node (ref "IC7") (pin "20") (pinfunction "GND_20") (pintype "power_in"))
      (node (ref "IC8") (pin "11") (pinfunction "GND_11") (pintype "power_in"))
      (node (ref "IC8") (pin "31") (pinfunction "AGND_31") (pintype "power_in"))
      (node (ref "IC9") (pin "12") (pinfunction "VSS_12") (pintype "power_in"))
      (node (ref "IC9") (pin "31") (pinfunction "VSS_31") (pintype "power_in"))
      (node (ref "JMP1") (pin "3") (pinfunction "3_3") (pintype "passive"))
      (node (ref "JMP2") (pin "3") (pinfunction "3_3") (pintype "passive"))
      (node (ref "JP1") (pin "3") (pinfunction "3_3") (pintype "passive"))
      (node (ref "JP10") (pin "1") (pinfunction "1_1") (pintype "passive"))
      (node (ref "JP11") (pin "3") (pinfunction "3_3") (pintype "passive"))
      (node (ref "JP2") (pin "3") (pinfunction "3_3") (pintype "passive"))
      (node (ref "JP3") (pin "3") (pinfunction "3_3") (pintype "passive"))
      (node (ref "JP4") (pin "3") (pinfunction "3_3") (pintype "passive"))
      (node (ref "JP5") (pin "3") (pinfunction "3_3") (pintype "passive"))
      (node (ref "JP6") (pin "3") (pinfunction "3_3") (pintype "passive"))
      (node (ref "JP7") (pin "6") (pinfunction "6_6") (pintype "passive"))
      (node (ref "JP8") (pin "6") (pinfunction "6_6") (pintype "passive"))
      (node (ref "JP9") (pin "3") (pinfunction "3_3") (pintype "passive"))
      (node (ref "LED1") (pin "C") (pinfunction "C_C") (pintype "passive"))
      (node (ref "LED10") (pin "K") (pinfunction "C_K") (pintype "passive"))
      (node (ref "LED11") (pin "K") (pinfunction "C_K") (pintype "passive"))
      (node (ref "LED2") (pin "C") (pinfunction "C_C") (pintype "passive"))
      (node (ref "LED3") (pin "C") (pinfunction "C_C") (pintype "passive"))
      (node (ref "LED4") (pin "C") (pinfunction "C_C") (pintype "passive"))
      (node (ref "LED5") (pin "C") (pinfunction "C_C") (pintype "passive"))
      (node (ref "LED6") (pin "C") (pinfunction "C_C") (pintype "passive"))
      (node (ref "LED7") (pin "K") (pinfunction "C_K") (pintype "passive"))
      (node (ref "LED8") (pin "K") (pinfunction "C_K") (pintype "passive"))
      (node (ref "LED9") (pin "K") (pinfunction "C_K") (pintype "passive"))
      (node (ref "S1") (pin "3") (pinfunction "P_3") (pintype "passive"))
      (node (ref "S10") (pin "1") (pinfunction "S_1") (pintype "passive"))
      (node (ref "S10") (pin "2") (pinfunction "S1_2") (pintype "passive"))
      (node (ref "S11") (pin "3") (pinfunction "P_3") (pintype "passive"))
      (node (ref "S11") (pin "4") (pinfunction "P1_4") (pintype "passive"))
      (node (ref "S2") (pin "3") (pinfunction "P_3") (pintype "passive"))
      (node (ref "S3") (pin "3") (pinfunction "P_3") (pintype "passive"))
      (node (ref "S4") (pin "3") (pinfunction "P_3") (pintype "passive"))
      (node (ref "S5") (pin "3") (pinfunction "P_3") (pintype "passive"))
      (node (ref "S6") (pin "3") (pinfunction "P_3") (pintype "passive"))
      (node (ref "S7") (pin "3") (pinfunction "P_3") (pintype "passive"))
      (node (ref "S7") (pin "4") (pinfunction "P1_4") (pintype "passive"))
      (node (ref "S8") (pin "3") (pinfunction "P_3") (pintype "passive"))
      (node (ref "S8") (pin "4") (pinfunction "P1_4") (pintype "passive"))
      (node (ref "S9") (pin "3") (pinfunction "P_3") (pintype "passive"))
      (node (ref "S9") (pin "4") (pinfunction "P1_4") (pintype "passive"))
      (node (ref "SV1") (pin "19") (pinfunction "19_19") (pintype "passive"))
      (node (ref "SV1") (pin "20") (pinfunction "20_20") (pintype "passive"))
      (node (ref "SV10") (pin "19") (pinfunction "19_19") (pintype "passive"))
      (node (ref "SV10") (pin "20") (pinfunction "20_20") (pintype "passive"))
      (node (ref "SV12") (pin "19") (pinfunction "19_19") (pintype "passive"))
      (node (ref "SV12") (pin "20") (pinfunction "20_20") (pintype "passive"))
      (node (ref "SV13") (pin "19") (pinfunction "19_19") (pintype "passive"))
      (node (ref "SV13") (pin "20") (pinfunction "20_20") (pintype "passive"))
      (node (ref "SV13") (pin "3") (pinfunction "3_3") (pintype "passive"))
      (node (ref "SV13") (pin "4") (pinfunction "4_4") (pintype "passive"))
      (node (ref "SV15") (pin "19") (pinfunction "19_19") (pintype "passive"))
      (node (ref "SV15") (pin "20") (pinfunction "20_20") (pintype "passive"))
      (node (ref "SV17") (pin "19") (pinfunction "19_19") (pintype "passive"))
      (node (ref "SV17") (pin "20") (pinfunction "20_20") (pintype "passive"))
      (node (ref "SV19") (pin "19") (pinfunction "19_19") (pintype "passive"))
      (node (ref "SV19") (pin "20") (pinfunction "20_20") (pintype "passive"))
      (node (ref "SV20") (pin "17") (pinfunction "17_17") (pintype "passive"))
      (node (ref "SV20") (pin "18") (pinfunction "18_18") (pintype "passive"))
      (node (ref "SV21") (pin "19") (pinfunction "19_19") (pintype "passive"))
      (node (ref "SV21") (pin "20") (pinfunction "20_20") (pintype "passive"))
      (node (ref "SV22") (pin "11") (pinfunction "11_11") (pintype "passive"))
      (node (ref "SV22") (pin "12") (pinfunction "12_12") (pintype "passive"))
      (node (ref "SV23") (pin "19") (pinfunction "19_19") (pintype "passive"))
      (node (ref "SV23") (pin "20") (pinfunction "20_20") (pintype "passive"))
      (node (ref "SV5") (pin "19") (pinfunction "19_19") (pintype "passive"))
      (node (ref "SV5") (pin "20") (pinfunction "20_20") (pintype "passive"))
      (node (ref "SV6") (pin "1") (pinfunction "1_1") (pintype "passive"))
      (node (ref "SV6") (pin "2") (pinfunction "2_2") (pintype "passive"))
      (node (ref "SV6") (pin "3") (pinfunction "3_3") (pintype "passive"))
      (node (ref "SV6") (pin "4") (pinfunction "4_4") (pintype "passive"))
      (node (ref "SV6") (pin "5") (pinfunction "5_5") (pintype "passive"))
      (node (ref "SV6") (pin "6") (pinfunction "6_6") (pintype "passive"))
      (node (ref "SV6") (pin "7") (pinfunction "7_7") (pintype "passive"))
      (node (ref "SV6") (pin "8") (pinfunction "8_8") (pintype "passive"))
      (node (ref "SV7") (pin "19") (pinfunction "19_19") (pintype "passive"))
      (node (ref "SV7") (pin "20") (pinfunction "20_20") (pintype "passive"))
      (node (ref "SV7") (pin "3") (pinfunction "3_3") (pintype "passive"))
      (node (ref "SV7") (pin "4") (pinfunction "4_4") (pintype "passive"))
      (node (ref "SV8") (pin "15") (pinfunction "15_15") (pintype "passive"))
      (node (ref "U$1") (pin "19") (pinfunction "PIN19_19") (pintype "input"))
      (node (ref "U$1") (pin "27") (pinfunction "PIN27_27") (pintype "input"))
      (node (ref "U$1") (pin "8") (pinfunction "PIN8_8") (pintype "input"))
      (node (ref "U$2") (pin "16") (pinfunction "16.AVSS_16") (pintype "bidirectional"))
      (node (ref "U$2") (pin "30") (pinfunction "30.VSS_30") (pintype "bidirectional"))
      (node (ref "U$2") (pin "31") (pinfunction "31.VSS_31") (pintype "bidirectional"))
      (node (ref "U$2") (pin "39") (pinfunction "39.VSS_39") (pintype "bidirectional"))
      (node (ref "U$2") (pin "6") (pinfunction "06.VSS_6") (pintype "bidirectional"))
      (node (ref "U$2") (pin "EXP") (pinfunction "45.MET_EXP") (pintype "bidirectional"))
      (node (ref "U$3") (pin "10") (pinfunction "BOE/_10") (pintype "input"))
    )
    (net (code "408") (name "unconnected-(S1-P1-Pad4)") (class "Default")
      (node (ref "S1") (pin "4") (pinfunction "P1_4") (pintype "passive"))
    )
    (net (code "409") (name "unconnected-(S1-S1-Pad2)") (class "Default")
      (node (ref "S1") (pin "2") (pinfunction "S1_2") (pintype "passive"))
    )
    (net (code "410") (name "unconnected-(S2-P1-Pad4)") (class "Default")
      (node (ref "S2") (pin "4") (pinfunction "P1_4") (pintype "passive"))
    )
    (net (code "411") (name "unconnected-(S2-S1-Pad2)") (class "Default")
      (node (ref "S2") (pin "2") (pinfunction "S1_2") (pintype "passive"))
    )
    (net (code "412") (name "unconnected-(S3-P1-Pad4)") (class "Default")
      (node (ref "S3") (pin "4") (pinfunction "P1_4") (pintype "passive"))
    )
    (net (code "413") (name "unconnected-(S3-S1-Pad2)") (class "Default")
      (node (ref "S3") (pin "2") (pinfunction "S1_2") (pintype "passive"))
    )
    (net (code "414") (name "unconnected-(S4-P1-Pad4)") (class "Default")
      (node (ref "S4") (pin "4") (pinfunction "P1_4") (pintype "passive"))
    )
    (net (code "415") (name "unconnected-(S4-S1-Pad2)") (class "Default")
      (node (ref "S4") (pin "2") (pinfunction "S1_2") (pintype "passive"))
    )
    (net (code "416") (name "unconnected-(S5-P1-Pad4)") (class "Default")
      (node (ref "S5") (pin "4") (pinfunction "P1_4") (pintype "passive"))
    )
    (net (code "417") (name "unconnected-(S5-S1-Pad2)") (class "Default")
      (node (ref "S5") (pin "2") (pinfunction "S1_2") (pintype "passive"))
    )
    (net (code "418") (name "unconnected-(S6-P1-Pad4)") (class "Default")
      (node (ref "S6") (pin "4") (pinfunction "P1_4") (pintype "passive"))
    )
    (net (code "419") (name "unconnected-(S6-S1-Pad2)") (class "Default")
      (node (ref "S6") (pin "2") (pinfunction "S1_2") (pintype "passive"))
    )
  )
)
